# cryotest-kintex7.net
KiCad netlist of a schematic drawn in EAGLE
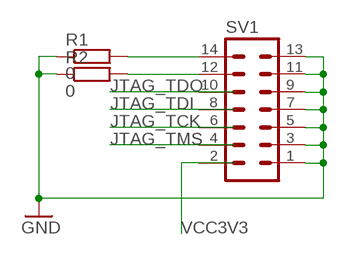
[diagram p0: schematic, sheet 1]
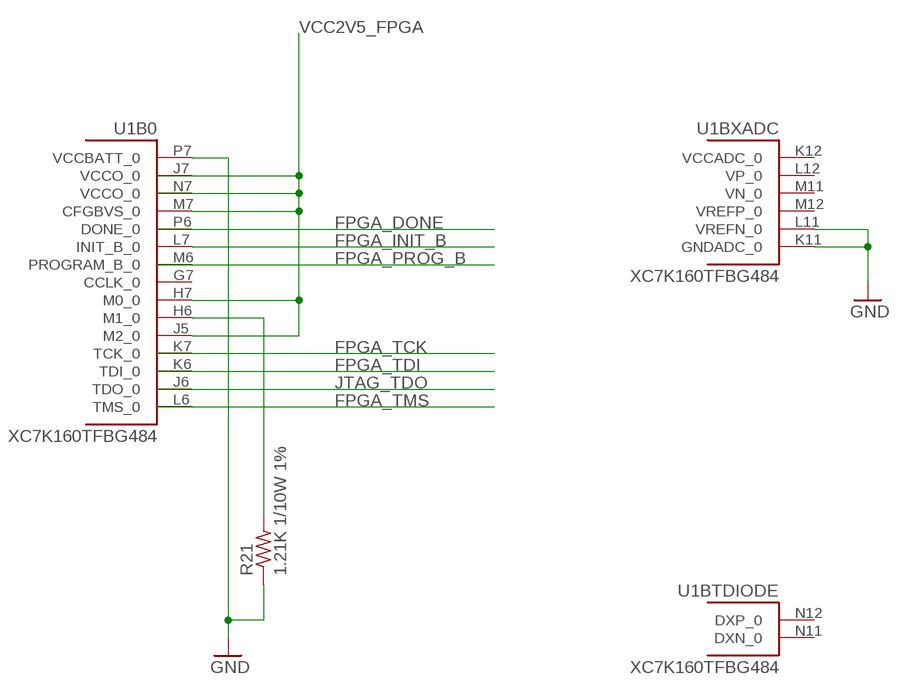
[diagram p1: schematic, sheet 2]
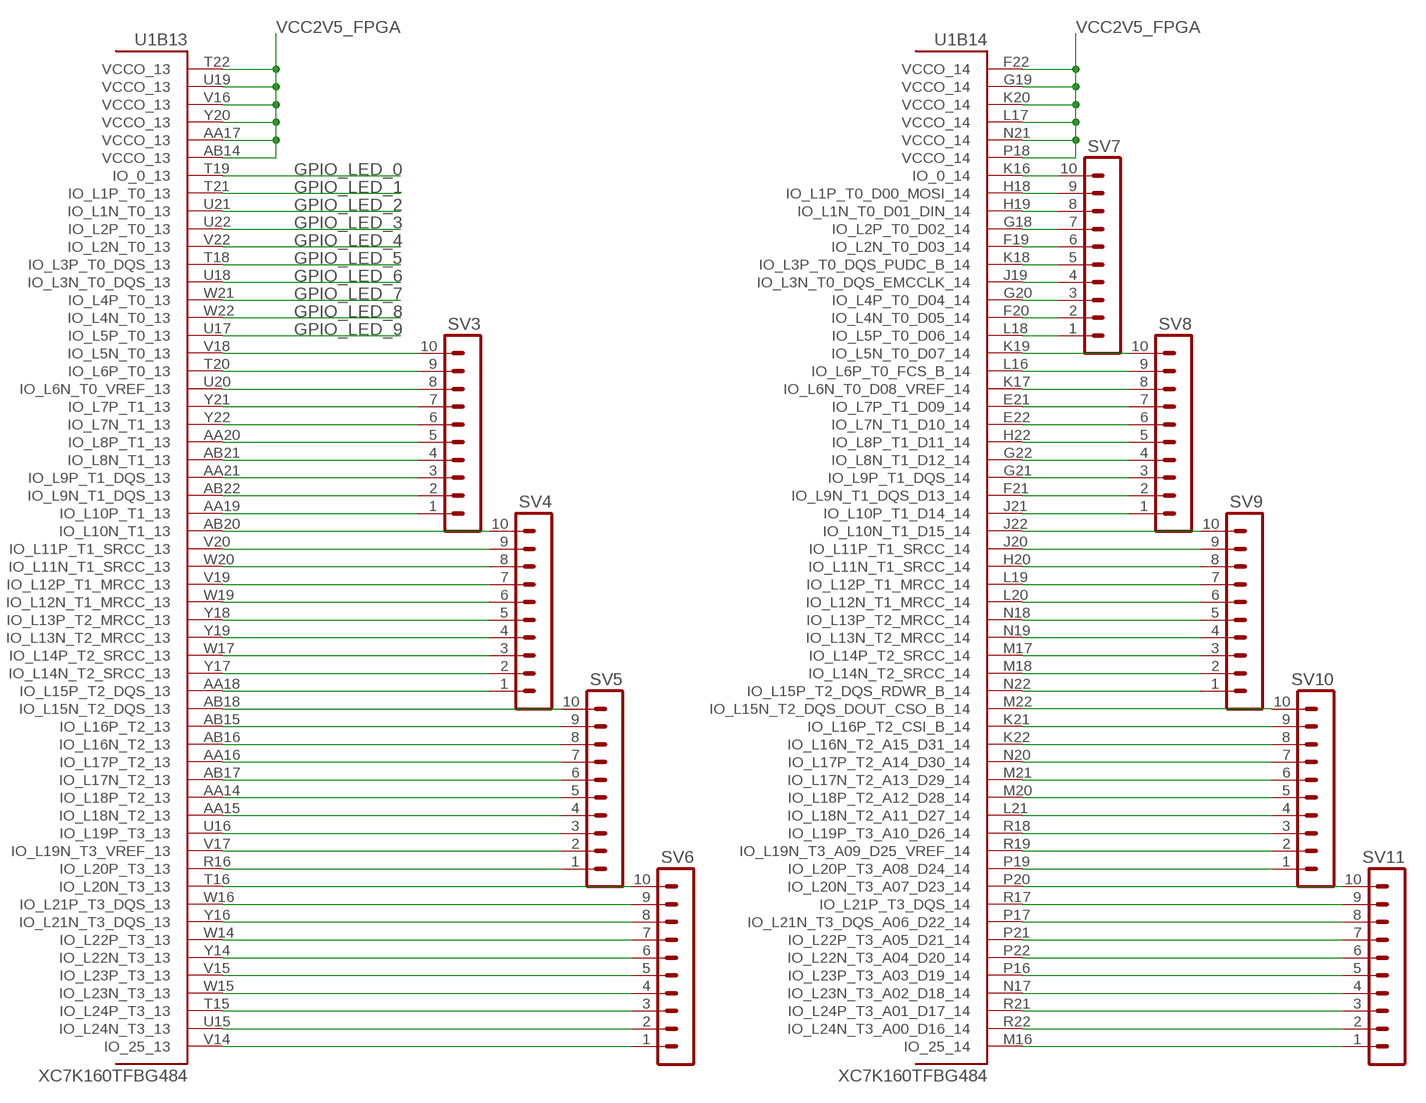
[diagram p2: schematic, sheet 3]
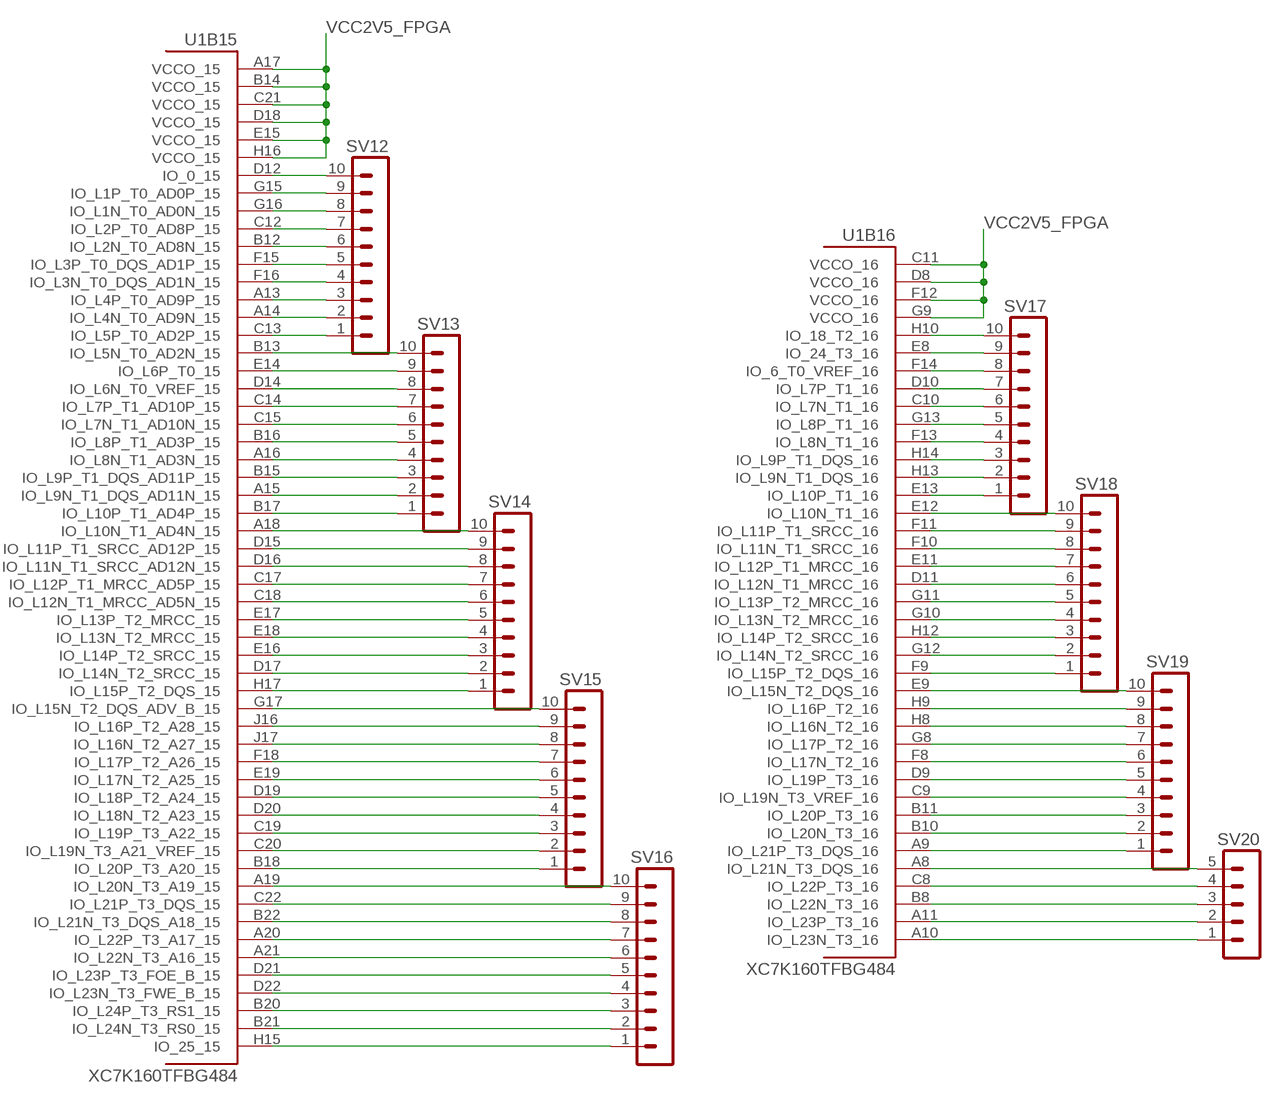
[diagram p3: schematic, sheet 4]
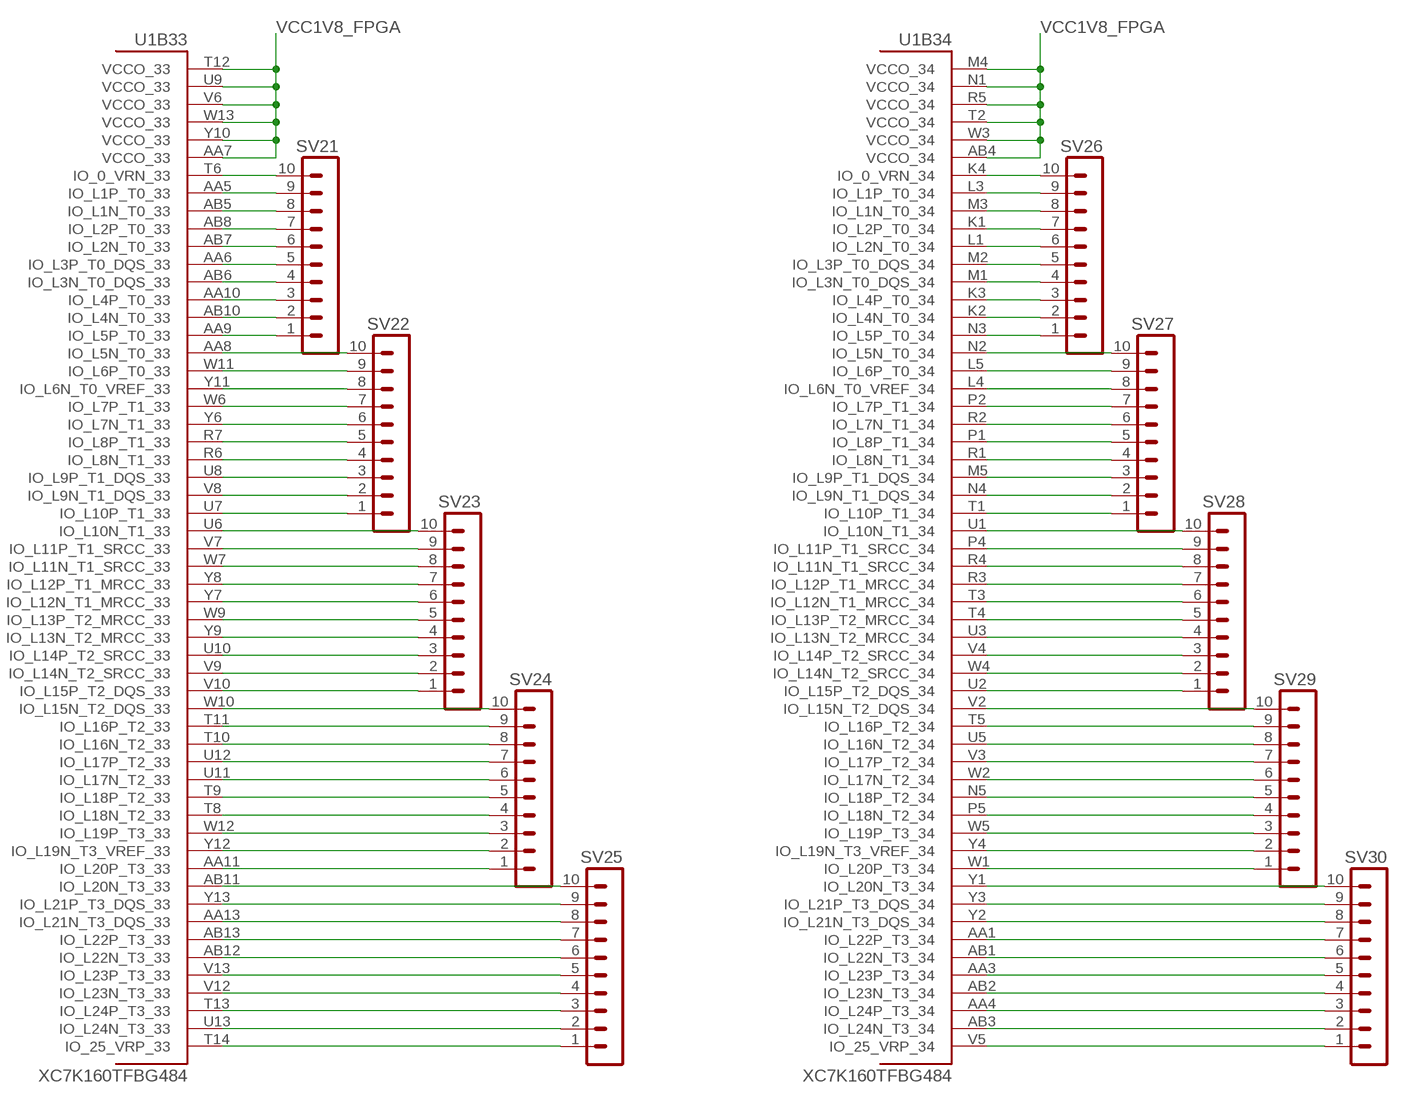
[diagram p4: schematic, sheet 5]
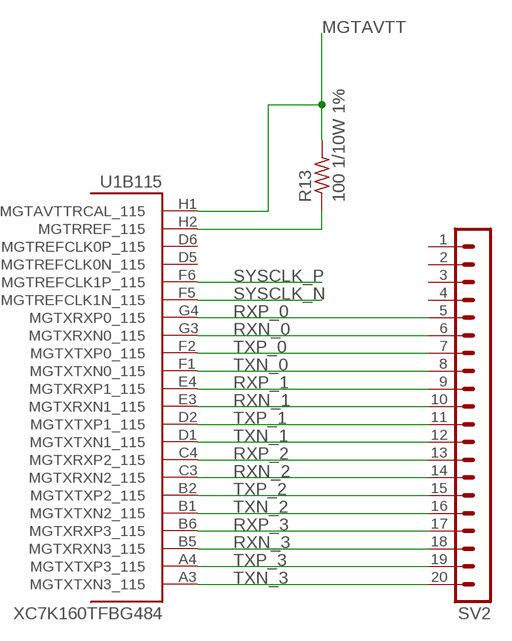
[diagram p5: schematic, sheet 6]
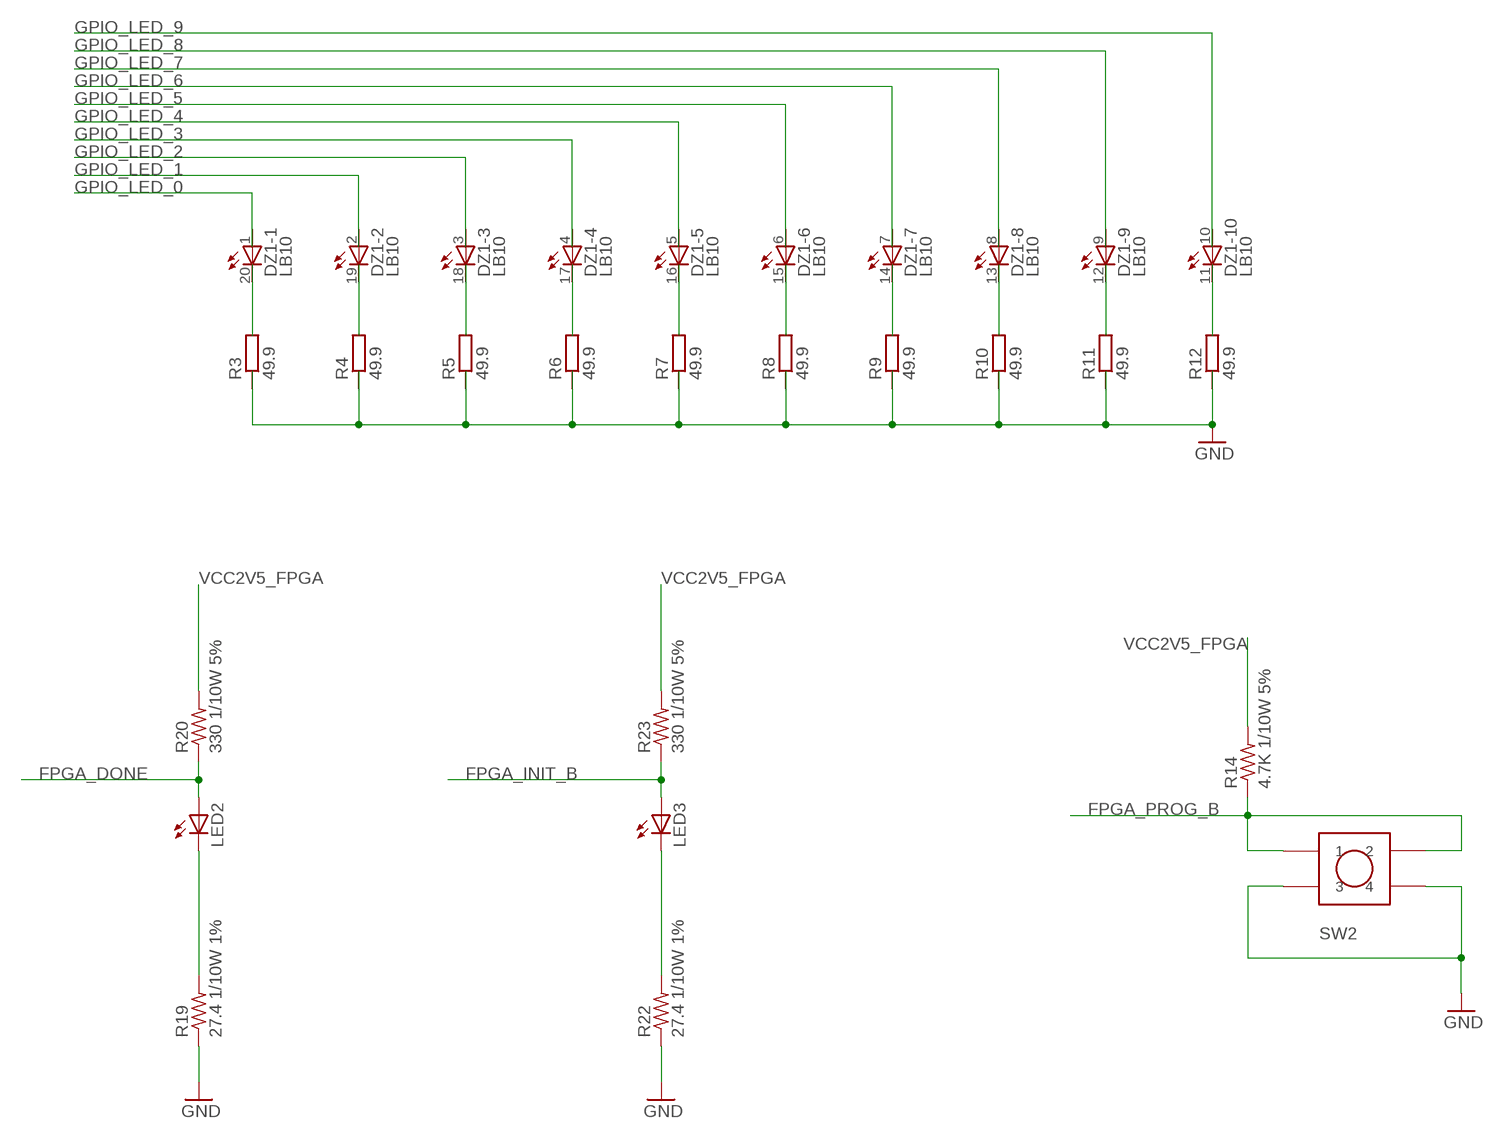
[diagram p6: schematic, sheet 7]
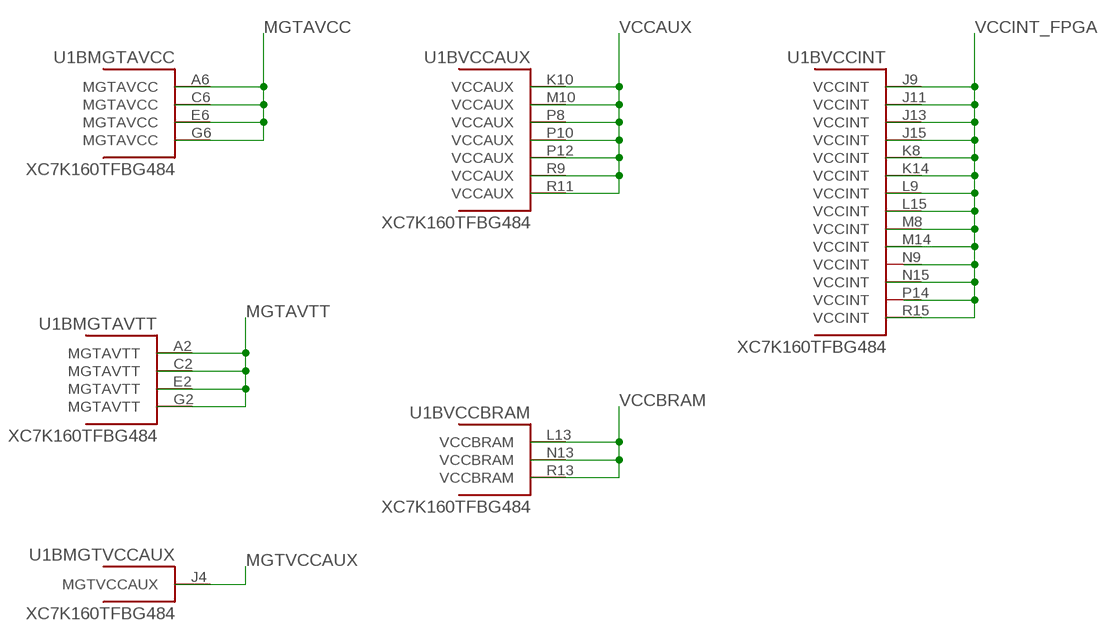
[diagram p7: schematic, sheet 8]
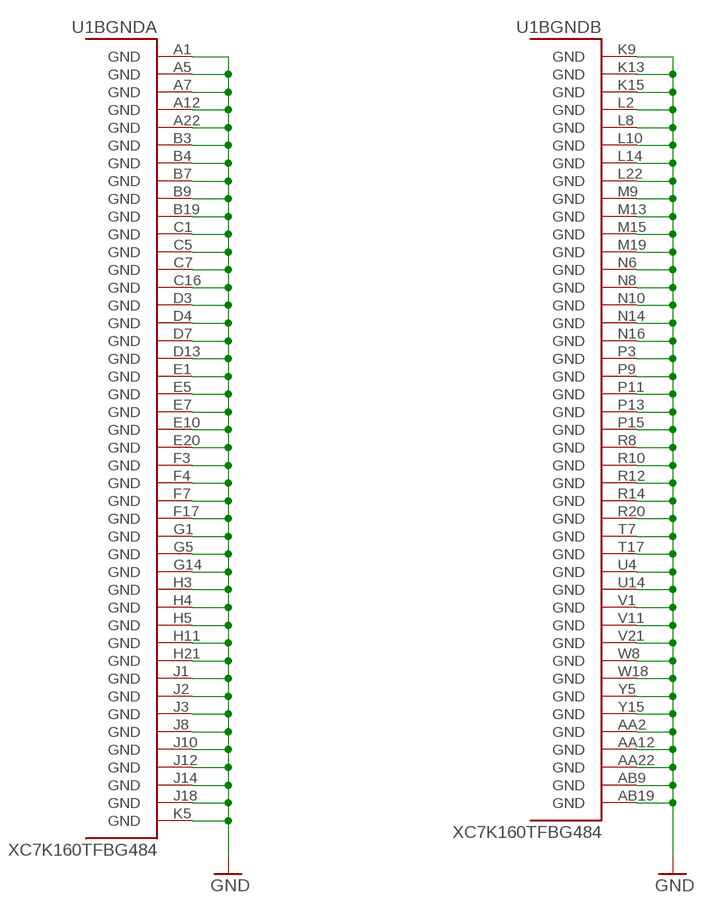
[diagram p8: schematic, sheet 9]
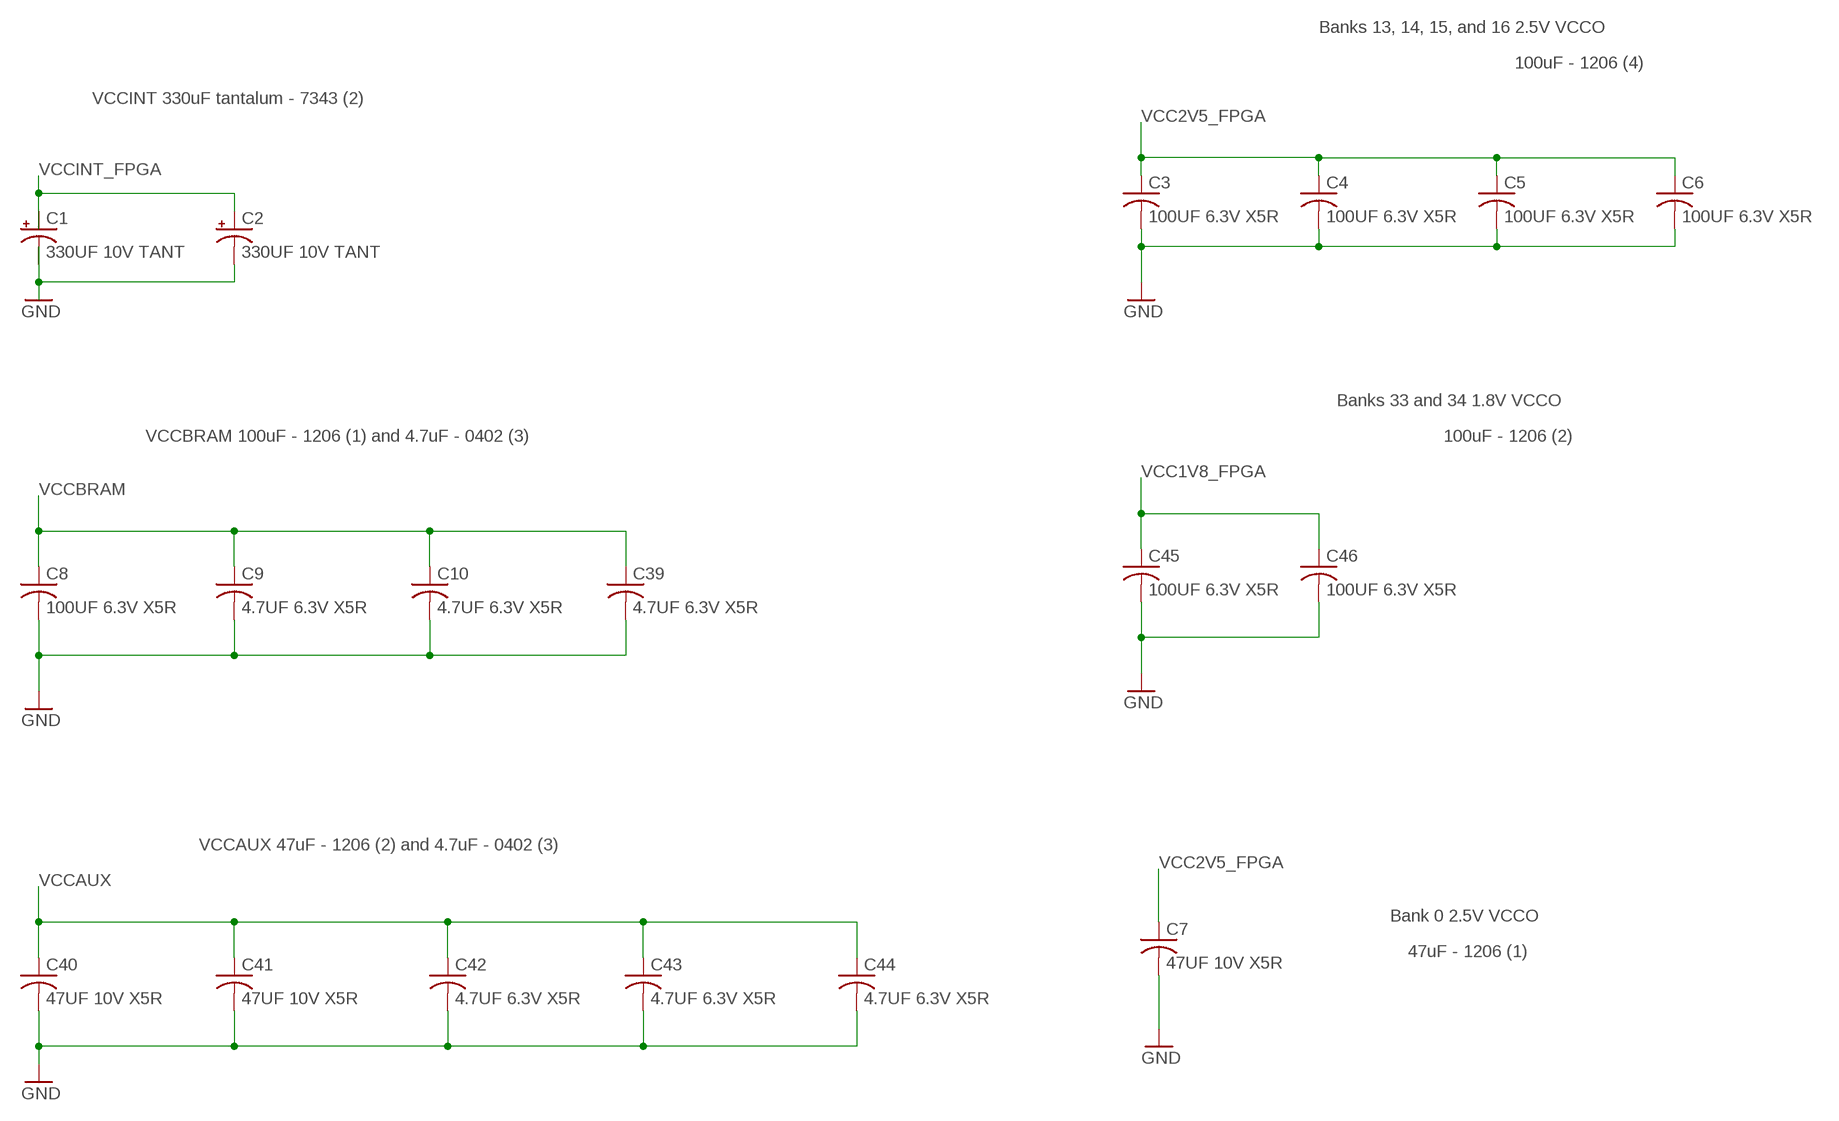
[diagram p9: schematic, sheet 10]
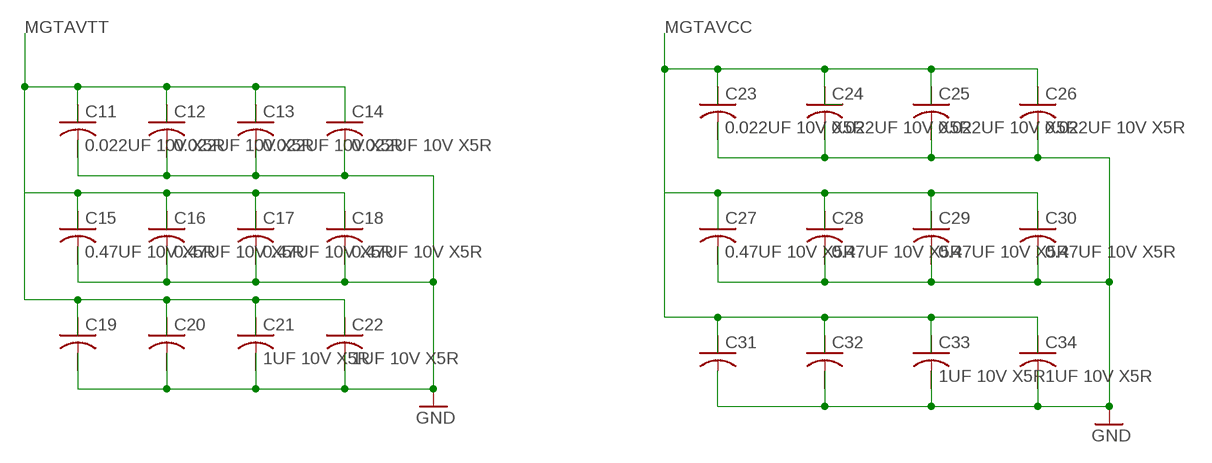
[diagram p10: schematic, sheet 11]
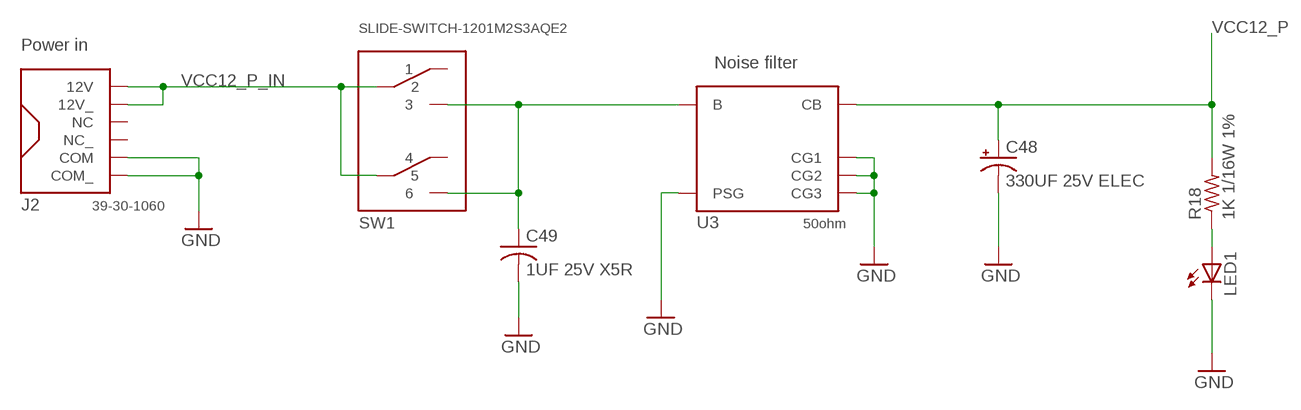
[diagram p11: schematic, sheet 12]
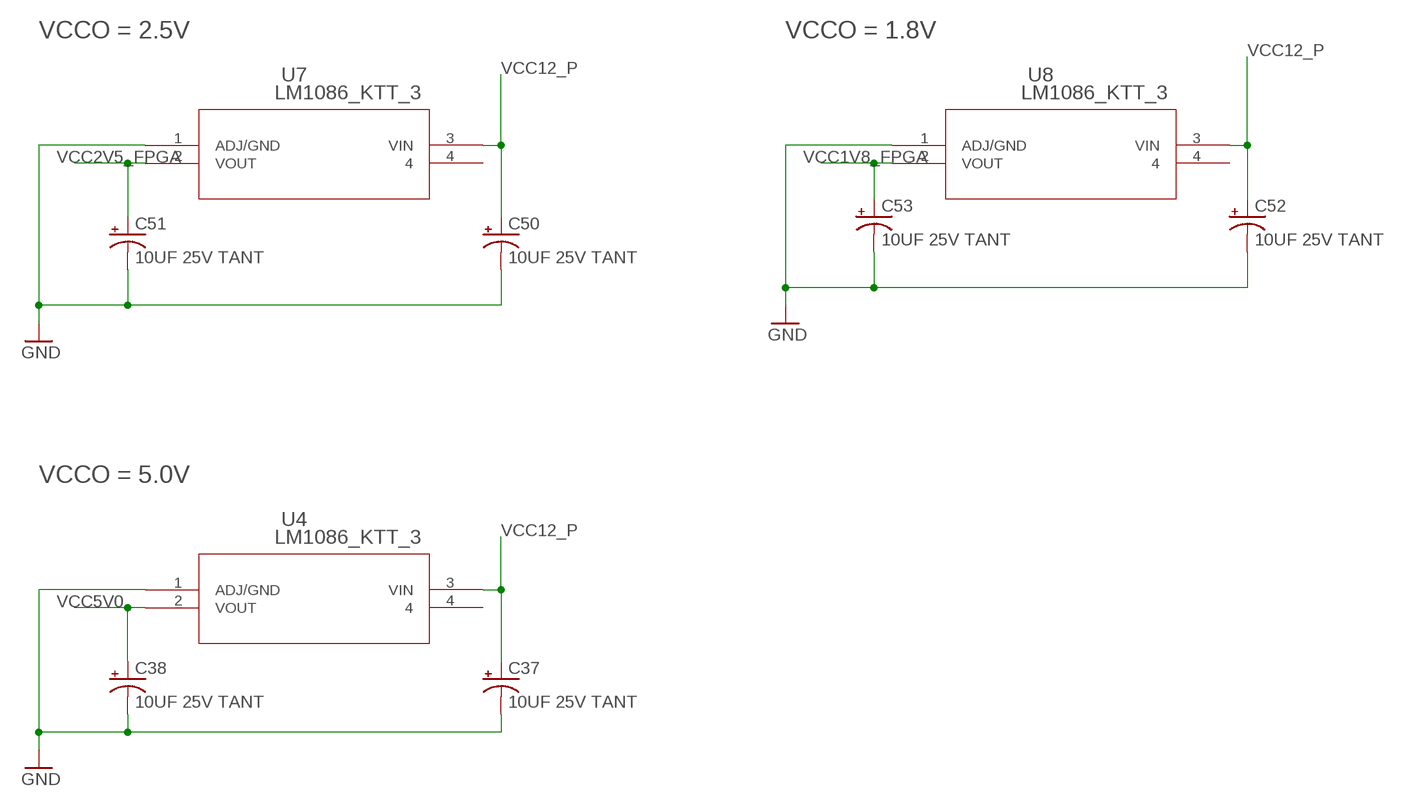
[diagram p12: schematic, sheet 13]
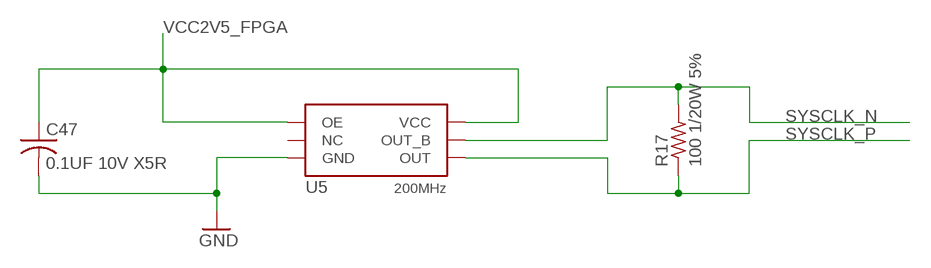
[diagram p13: schematic, sheet 14]
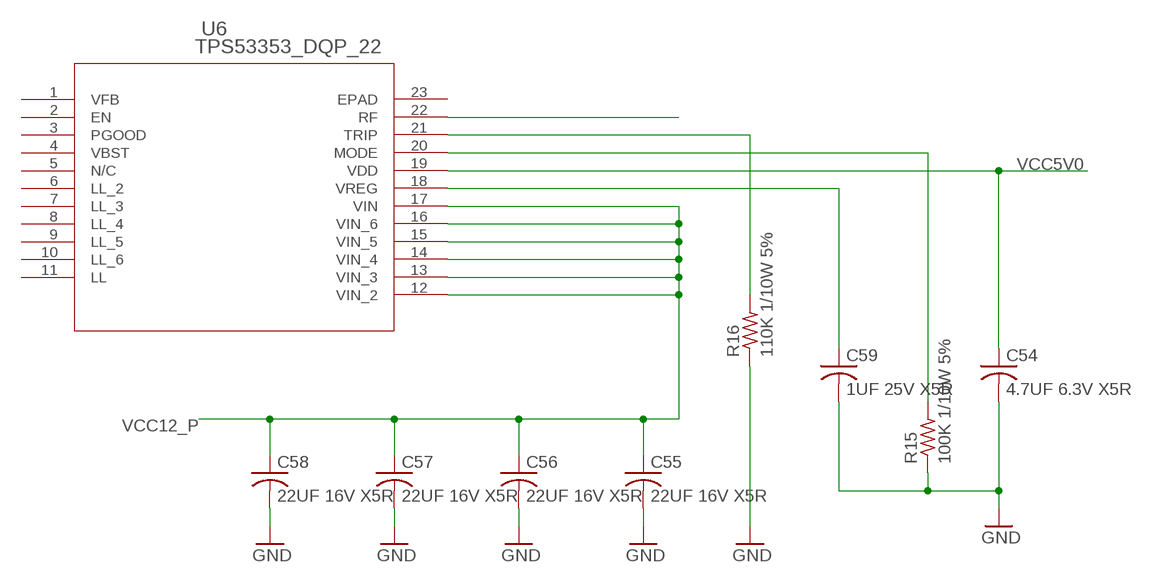
[diagram p14: schematic, sheet 15]

(export (version "E")
  (design (tool "Eeschema 10.0.6"))
  (components
    (comp (ref "R1")
      (value "0")
      (footprint "eagle-import:R0805")
      (libsource (lib "eagle-import") (part "R-EU_R0805"))
    )
    (comp (ref "R2")
      (value "0")
      (footprint "eagle-import:R0805")
      (libsource (lib "eagle-import") (part "R-EU_R0805"))
    )
    (comp (ref "SV1")
      (value "MA07-2")
      (footprint "eagle-import:MA07-2")
      (libsource (lib "eagle-import") (part "MA07-2"))
    )
    (comp (ref "SV12")
      (value "MA10-1")
      (footprint "eagle-import:MA10-1")
      (libsource (lib "eagle-import") (part "MA10-1"))
    )
    (comp (ref "SV13")
      (value "MA10-1")
      (footprint "eagle-import:MA10-1")
      (libsource (lib "eagle-import") (part "MA10-1"))
    )
    (comp (ref "SV14")
      (value "MA10-1")
      (footprint "eagle-import:MA10-1")
      (libsource (lib "eagle-import") (part "MA10-1"))
    )
    (comp (ref "SV15")
      (value "MA10-1")
      (footprint "eagle-import:MA10-1")
      (libsource (lib "eagle-import") (part "MA10-1"))
    )
    (comp (ref "SV16")
      (value "MA10-1")
      (footprint "eagle-import:MA10-1")
      (libsource (lib "eagle-import") (part "MA10-1"))
    )
    (comp (ref "SV17")
      (value "MA10-1")
      (footprint "eagle-import:MA10-1")
      (libsource (lib "eagle-import") (part "MA10-1"))
    )
    (comp (ref "SV18")
      (value "MA10-1")
      (footprint "eagle-import:MA10-1")
      (libsource (lib "eagle-import") (part "MA10-1"))
    )
    (comp (ref "SV19")
      (value "MA10-1")
      (footprint "eagle-import:MA10-1")
      (libsource (lib "eagle-import") (part "MA10-1"))
    )
    (comp (ref "SV20")
      (value "MA05-1")
      (footprint "eagle-import:MA05-1")
      (libsource (lib "eagle-import") (part "MA05-1"))
    )
    (comp (ref "U1")
      (value "XC7K160TFBG484")
      (footprint "eagle-import:FF484")
      (libsource (lib "eagle-import") (part "XC7K160TFBG484"))
    )
    (comp (ref "C1")
      (value "330UF 10V TANT")
      (footprint "eagle-import:CT7343")
      (libsource (lib "eagle-import") (part "CPOL-USCT7343"))
    )
    (comp (ref "C2")
      (value "330UF 10V TANT")
      (footprint "eagle-import:CT7343")
      (libsource (lib "eagle-import") (part "CPOL-USCT7343"))
    )
    (comp (ref "C3")
      (value "100UF 6.3V X5R")
      (footprint "eagle-import:C1206")
      (libsource (lib "eagle-import") (part "C-USC1206"))
    )
    (comp (ref "C4")
      (value "100UF 6.3V X5R")
      (footprint "eagle-import:C1206")
      (libsource (lib "eagle-import") (part "C-USC1206"))
    )
    (comp (ref "C5")
      (value "100UF 6.3V X5R")
      (footprint "eagle-import:C1206")
      (libsource (lib "eagle-import") (part "C-USC1206"))
    )
    (comp (ref "C6")
      (value "100UF 6.3V X5R")
      (footprint "eagle-import:C1206")
      (libsource (lib "eagle-import") (part "C-USC1206"))
    )
    (comp (ref "C7")
      (value "47UF 10V X5R")
      (footprint "eagle-import:C1206")
      (libsource (lib "eagle-import") (part "C-USC1206"))
    )
    (comp (ref "C8")
      (value "100UF 6.3V X5R")
      (footprint "eagle-import:C1206")
      (libsource (lib "eagle-import") (part "C-USC1206"))
    )
    (comp (ref "C9")
      (value "4.7UF 6.3V X5R")
      (footprint "eagle-import:C0402")
      (libsource (lib "eagle-import") (part "C-USC0402"))
    )
    (comp (ref "C10")
      (value "4.7UF 6.3V X5R")
      (footprint "eagle-import:C0402")
      (libsource (lib "eagle-import") (part "C-USC0402"))
    )
    (comp (ref "C39")
      (value "4.7UF 6.3V X5R")
      (footprint "eagle-import:C0402")
      (libsource (lib "eagle-import") (part "C-USC0402"))
    )
    (comp (ref "C40")
      (value "47UF 10V X5R")
      (footprint "eagle-import:C1206")
      (libsource (lib "eagle-import") (part "C-USC1206"))
    )
    (comp (ref "C41")
      (value "47UF 10V X5R")
      (footprint "eagle-import:C1206")
      (libsource (lib "eagle-import") (part "C-USC1206"))
    )
    (comp (ref "C42")
      (value "4.7UF 6.3V X5R")
      (footprint "eagle-import:C1206")
      (libsource (lib "eagle-import") (part "C-USC1206"))
    )
    (comp (ref "C43")
      (value "4.7UF 6.3V X5R")
      (footprint "eagle-import:C1206")
      (libsource (lib "eagle-import") (part "C-USC1206"))
    )
    (comp (ref "C44")
      (value "4.7UF 6.3V X5R")
      (footprint "eagle-import:C1206")
      (libsource (lib "eagle-import") (part "C-USC1206"))
    )
    (comp (ref "C45")
      (value "100UF 6.3V X5R")
      (footprint "eagle-import:C1206")
      (libsource (lib "eagle-import") (part "C-USC1206"))
    )
    (comp (ref "C46")
      (value "100UF 6.3V X5R")
      (footprint "eagle-import:C1206")
      (libsource (lib "eagle-import") (part "C-USC1206"))
    )
    (comp (ref "SV3")
      (value "MA10-1")
      (footprint "eagle-import:MA10-1")
      (libsource (lib "eagle-import") (part "MA10-1"))
    )
    (comp (ref "SV4")
      (value "MA10-1")
      (footprint "eagle-import:MA10-1")
      (libsource (lib "eagle-import") (part "MA10-1"))
    )
    (comp (ref "SV5")
      (value "MA10-1")
      (footprint "eagle-import:MA10-1")
      (libsource (lib "eagle-import") (part "MA10-1"))
    )
    (comp (ref "SV6")
      (value "MA10-1")
      (footprint "eagle-import:MA10-1")
      (libsource (lib "eagle-import") (part "MA10-1"))
    )
    (comp (ref "SV7")
      (value "MA10-1")
      (footprint "eagle-import:MA10-1")
      (libsource (lib "eagle-import") (part "MA10-1"))
    )
    (comp (ref "SV8")
      (value "MA10-1")
      (footprint "eagle-import:MA10-1")
      (libsource (lib "eagle-import") (part "MA10-1"))
    )
    (comp (ref "SV9")
      (value "MA10-1")
      (footprint "eagle-import:MA10-1")
      (libsource (lib "eagle-import") (part "MA10-1"))
    )
    (comp (ref "SV10")
      (value "MA10-1")
      (footprint "eagle-import:MA10-1")
      (libsource (lib "eagle-import") (part "MA10-1"))
    )
    (comp (ref "SV11")
      (value "MA10-1")
      (footprint "eagle-import:MA10-1")
      (libsource (lib "eagle-import") (part "MA10-1"))
    )
    (comp (ref "SV21")
      (value "MA10-1")
      (footprint "eagle-import:MA10-1")
      (libsource (lib "eagle-import") (part "MA10-1"))
    )
    (comp (ref "SV22")
      (value "MA10-1")
      (footprint "eagle-import:MA10-1")
      (libsource (lib "eagle-import") (part "MA10-1"))
    )
    (comp (ref "SV23")
      (value "MA10-1")
      (footprint "eagle-import:MA10-1")
      (libsource (lib "eagle-import") (part "MA10-1"))
    )
    (comp (ref "SV24")
      (value "MA10-1")
      (footprint "eagle-import:MA10-1")
      (libsource (lib "eagle-import") (part "MA10-1"))
    )
    (comp (ref "SV25")
      (value "MA10-1")
      (footprint "eagle-import:MA10-1")
      (libsource (lib "eagle-import") (part "MA10-1"))
    )
    (comp (ref "SV26")
      (value "MA10-1")
      (footprint "eagle-import:MA10-1")
      (libsource (lib "eagle-import") (part "MA10-1"))
    )
    (comp (ref "SV27")
      (value "MA10-1")
      (footprint "eagle-import:MA10-1")
      (libsource (lib "eagle-import") (part "MA10-1"))
    )
    (comp (ref "SV28")
      (value "MA10-1")
      (footprint "eagle-import:MA10-1")
      (libsource (lib "eagle-import") (part "MA10-1"))
    )
    (comp (ref "SV29")
      (value "MA10-1")
      (footprint "eagle-import:MA10-1")
      (libsource (lib "eagle-import") (part "MA10-1"))
    )
    (comp (ref "SV30")
      (value "MA10-1")
      (footprint "eagle-import:MA10-1")
      (libsource (lib "eagle-import") (part "MA10-1"))
    )
    (comp (ref "R21")
      (value "1.21K 1/10W 1%")
      (footprint "eagle-import:R0402")
      (libsource (lib "eagle-import") (part "R-US_R0402"))
    )
    (comp (ref "R13")
      (value "100 1/10W 1%")
      (footprint "eagle-import:R0402")
      (libsource (lib "eagle-import") (part "resistor_R-US_R0402"))
    )
    (comp (ref "SV2")
      (value "MA20-1")
      (footprint "eagle-import:MA20-1")
      (libsource (lib "eagle-import") (part "MA20-1"))
    )
    (comp (ref "C11")
      (value "0.022UF 10V X5R")
      (footprint "eagle-import:C0603")
      (libsource (lib "eagle-import") (part "C-USC0603"))
    )
    (comp (ref "C12")
      (value "0.022UF 10V X5R")
      (footprint "eagle-import:C0603")
      (libsource (lib "eagle-import") (part "C-USC0603"))
    )
    (comp (ref "C13")
      (value "0.022UF 10V X5R")
      (footprint "eagle-import:C0603")
      (libsource (lib "eagle-import") (part "C-USC0603"))
    )
    (comp (ref "C14")
      (value "0.022UF 10V X5R")
      (footprint "eagle-import:C0603")
      (libsource (lib "eagle-import") (part "C-USC0603"))
    )
    (comp (ref "C15")
      (value "0.47UF 10V X5R")
      (footprint "eagle-import:C0603")
      (libsource (lib "eagle-import") (part "C-USC0603"))
    )
    (comp (ref "C16")
      (value "0.47UF 10V X5R")
      (footprint "eagle-import:C0603")
      (libsource (lib "eagle-import") (part "C-USC0603"))
    )
    (comp (ref "C17")
      (value "0.47UF 10V X5R")
      (footprint "eagle-import:C0603")
      (libsource (lib "eagle-import") (part "C-USC0603"))
    )
    (comp (ref "C18")
      (value "0.47UF 10V X5R")
      (footprint "eagle-import:C0603")
      (libsource (lib "eagle-import") (part "C-USC0603"))
    )
    (comp (ref "C19")
      (value "C-US01005")
      (footprint "eagle-import:C01005")
      (libsource (lib "eagle-import") (part "C-US01005"))
    )
    (comp (ref "C20")
      (value "C-US01005")
      (footprint "eagle-import:C01005")
      (libsource (lib "eagle-import") (part "C-US01005"))
    )
    (comp (ref "C21")
      (value "1UF 10V X5R")
      (footprint "eagle-import:C0603")
      (libsource (lib "eagle-import") (part "C-USC0603"))
    )
    (comp (ref "C22")
      (value "1UF 10V X5R")
      (footprint "eagle-import:C0603")
      (libsource (lib "eagle-import") (part "C-USC0603"))
    )
    (comp (ref "C23")
      (value "0.022UF 10V X5R")
      (footprint "eagle-import:C0603")
      (libsource (lib "eagle-import") (part "C-USC0603"))
    )
    (comp (ref "C24")
      (value "0.022UF 10V X5R")
      (footprint "eagle-import:C0603")
      (libsource (lib "eagle-import") (part "C-USC0603"))
    )
    (comp (ref "C25")
      (value "0.022UF 10V X5R")
      (footprint "eagle-import:C0603")
      (libsource (lib "eagle-import") (part "C-USC0603"))
    )
    (comp (ref "C26")
      (value "0.022UF 10V X5R")
      (footprint "eagle-import:C0603")
      (libsource (lib "eagle-import") (part "C-USC0603"))
    )
    (comp (ref "C27")
      (value "0.47UF 10V X5R")
      (footprint "eagle-import:C0603")
      (libsource (lib "eagle-import") (part "C-USC0603"))
    )
    (comp (ref "C28")
      (value "0.47UF 10V X5R")
      (footprint "eagle-import:C0603")
      (libsource (lib "eagle-import") (part "C-USC0603"))
    )
    (comp (ref "C29")
      (value "0.47UF 10V X5R")
      (footprint "eagle-import:C0603")
      (libsource (lib "eagle-import") (part "C-USC0603"))
    )
    (comp (ref "C30")
      (value "0.47UF 10V X5R")
      (footprint "eagle-import:C0603")
      (libsource (lib "eagle-import") (part "C-USC0603"))
    )
    (comp (ref "C31")
      (value "C-US01005")
      (footprint "eagle-import:C01005")
      (libsource (lib "eagle-import") (part "C-US01005"))
    )
    (comp (ref "C32")
      (value "C-US01005")
      (footprint "eagle-import:C01005")
      (libsource (lib "eagle-import") (part "C-US01005"))
    )
    (comp (ref "C33")
      (value "1UF 10V X5R")
      (footprint "eagle-import:C0603")
      (libsource (lib "eagle-import") (part "C-USC0603"))
    )
    (comp (ref "C34")
      (value "1UF 10V X5R")
      (footprint "eagle-import:C0603")
      (libsource (lib "eagle-import") (part "C-USC0603"))
    )
    (comp (ref "C48")
      (value "330UF 25V ELEC")
      (footprint "eagle-import:PANASONIC_F")
      (libsource (lib "eagle-import") (part "CPOL-USF"))
    )
    (comp (ref "C49")
      (value "1UF 25V X5R")
      (footprint "eagle-import:C0603")
      (libsource (lib "eagle-import") (part "C-USC0603"))
    )
    (comp (ref "J2")
      (value "39-30-1060")
      (footprint "eagle-import:5569_6P")
      (libsource (lib "eagle-import") (part "39-30-1060{dblquote}"))
    )
    (comp (ref "LED1")
      (value "LEDSML0603")
      (footprint "eagle-import:SML0603")
      (libsource (lib "eagle-import") (part "LEDSML0603"))
    )
    (comp (ref "R18")
      (value "1K 1/16W 1%")
      (footprint "eagle-import:R0402")
      (libsource (lib "eagle-import") (part "R-US_R0402"))
    )
    (comp (ref "SW1")
      (value "SLIDE-SWITCH-1201M2S3AQE2")
      (footprint "eagle-import:HORIZONTAL-DPDT")
      (libsource (lib "eagle-import") (part "SLIDE-SWITCH-1201M2S3AQE2"))
    )
    (comp (ref "U3")
      (value "50ohm")
      (footprint "eagle-import:BNX016-01")
      (libsource (lib "eagle-import") (part "BNX016-01{dblquote}"))
    )
    (comp (ref "DZ1")
      (value "LB10")
      (footprint "eagle-import:LB10")
      (libsource (lib "eagle-import") (part "LB10"))
    )
    (comp (ref "LED2")
      (value "LEDSML0603")
      (footprint "eagle-import:SML0603")
      (libsource (lib "eagle-import") (part "LEDSML0603"))
    )
    (comp (ref "LED3")
      (value "LEDSML0603")
      (footprint "eagle-import:SML0603")
      (libsource (lib "eagle-import") (part "LEDSML0603"))
    )
    (comp (ref "R3")
      (value "49.9")
      (footprint "eagle-import:R0603")
      (libsource (lib "eagle-import") (part "resistor_R-EU_R0603"))
    )
    (comp (ref "R4")
      (value "49.9")
      (footprint "eagle-import:R0603")
      (libsource (lib "eagle-import") (part "resistor_R-EU_R0603"))
    )
    (comp (ref "R5")
      (value "49.9")
      (footprint "eagle-import:R0603")
      (libsource (lib "eagle-import") (part "resistor_R-EU_R0603"))
    )
    (comp (ref "R6")
      (value "49.9")
      (footprint "eagle-import:R0603")
      (libsource (lib "eagle-import") (part "resistor_R-EU_R0603"))
    )
    (comp (ref "R7")
      (value "49.9")
      (footprint "eagle-import:R0603")
      (libsource (lib "eagle-import") (part "resistor_R-EU_R0603"))
    )
    (comp (ref "R8")
      (value "49.9")
      (footprint "eagle-import:R0603")
      (libsource (lib "eagle-import") (part "resistor_R-EU_R0603"))
    )
    (comp (ref "R9")
      (value "49.9")
      (footprint "eagle-import:R0603")
      (libsource (lib "eagle-import") (part "resistor_R-EU_R0603"))
    )
    (comp (ref "R10")
      (value "49.9")
      (footprint "eagle-import:R0603")
      (libsource (lib "eagle-import") (part "resistor_R-EU_R0603"))
    )
    (comp (ref "R11")
      (value "49.9")
      (footprint "eagle-import:R0603")
      (libsource (lib "eagle-import") (part "resistor_R-EU_R0603"))
    )
    (comp (ref "R12")
      (value "49.9")
      (footprint "eagle-import:R0603")
      (libsource (lib "eagle-import") (part "resistor_R-EU_R0603"))
    )
    (comp (ref "R14")
      (value "4.7K 1/10W 5%")
      (footprint "eagle-import:R0402")
      (libsource (lib "eagle-import") (part "resistor_R-US_R0402"))
    )
    (comp (ref "R19")
      (value "27.4 1/10W 1%")
      (footprint "eagle-import:R0402")
      (libsource (lib "eagle-import") (part "R-US_R0402"))
    )
    (comp (ref "R20")
      (value "330 1/10W 5%")
      (footprint "eagle-import:R0603")
      (libsource (lib "eagle-import") (part "R-US_R0603"))
    )
    (comp (ref "R22")
      (value "27.4 1/10W 1%")
      (footprint "eagle-import:R0402")
      (libsource (lib "eagle-import") (part "R-US_R0402"))
    )
    (comp (ref "R23")
      (value "330 1/10W 5%")
      (footprint "eagle-import:R0603")
      (libsource (lib "eagle-import") (part "R-US_R0603"))
    )
    (comp (ref "SW2")
      (value "TL3301EF100QG\"")
      (footprint "eagle-import:GULL-WING")
      (libsource (lib "eagle-import") (part "TL3301EF100QG{dblquote}"))
    )
    (comp (ref "C54")
      (value "4.7UF 6.3V X5R")
      (footprint "eagle-import:C0402")
      (libsource (lib "eagle-import") (part "C-USC0402"))
    )
    (comp (ref "C55")
      (value "22UF 16V X5R")
      (footprint "eagle-import:C1206")
      (libsource (lib "eagle-import") (part "C-USC1206"))
    )
    (comp (ref "C56")
      (value "22UF 16V X5R")
      (footprint "eagle-import:C1206")
      (libsource (lib "eagle-import") (part "C-USC1206"))
    )
    (comp (ref "C57")
      (value "22UF 16V X5R")
      (footprint "eagle-import:C1206")
      (libsource (lib "eagle-import") (part "C-USC1206"))
    )
    (comp (ref "C58")
      (value "22UF 16V X5R")
      (footprint "eagle-import:C1206")
      (libsource (lib "eagle-import") (part "C-USC1206"))
    )
    (comp (ref "C59")
      (value "1UF 25V X5R")
      (footprint "eagle-import:C0603")
      (libsource (lib "eagle-import") (part "C-USC0603"))
    )
    (comp (ref "R15")
      (value "100K 1/10W 5%")
      (footprint "eagle-import:R0402")
      (libsource (lib "eagle-import") (part "R-US_R0402"))
    )
    (comp (ref "R16")
      (value "110K 1/10W 5%")
      (footprint "eagle-import:R0402")
      (libsource (lib "eagle-import") (part "resistor_R-US_R0402"))
    )
    (comp (ref "U6")
      (value "TPS53353_DQP_22")
      (footprint "eagle-import:DQP22_5P479X3P24")
      (fields
        (field (name "GENERIC_PART_NUMBER") "TPS53353")
        (field (name "MANUFACTURER") "Texas Instruments")
        (field (name "MANUFACTURER_PART_NUMBER") "tps53353_dqp_22")
      )
      (libsource (lib "eagle-import") (part "TPS53353_DQP_22"))
    )
    (comp (ref "C47")
      (value "0.1UF 10V X5R")
      (footprint "eagle-import:C0402")
      (libsource (lib "eagle-import") (part "C-USC0402"))
    )
    (comp (ref "R17")
      (value "100 1/20W 5%")
      (footprint "eagle-import:R0201")
      (libsource (lib "eagle-import") (part "R-US_R0201"))
    )
    (comp (ref "U5")
      (value "200MHz")
      (footprint "eagle-import:7X5")
      (libsource (lib "eagle-import") (part "SIT9102{dblquote}"))
    )
    (comp (ref "C37")
      (value "10UF 25V TANT")
      (footprint "eagle-import:CT7343")
      (libsource (lib "eagle-import") (part "CPOL-USCT7343"))
    )
    (comp (ref "C38")
      (value "10UF 25V TANT")
      (footprint "eagle-import:CT7343")
      (libsource (lib "eagle-import") (part "CPOL-USCT7343"))
    )
    (comp (ref "C50")
      (value "10UF 25V TANT")
      (footprint "eagle-import:CT7343")
      (libsource (lib "eagle-import") (part "CPOL-USCT7343"))
    )
    (comp (ref "C51")
      (value "10UF 25V TANT")
      (footprint "eagle-import:CT7343")
      (libsource (lib "eagle-import") (part "CPOL-USCT7343"))
    )
    (comp (ref "C52")
      (value "10UF 25V TANT")
      (footprint "eagle-import:CT7343")
      (libsource (lib "eagle-import") (part "CPOL-USCT7343"))
    )
    (comp (ref "C53")
      (value "10UF 25V TANT")
      (footprint "eagle-import:CT7343")
      (libsource (lib "eagle-import") (part "CPOL-USCT7343"))
    )
    (comp (ref "U4")
      (value "LM1086_KTT_3")
      (footprint "eagle-import:TS3B")
      (fields (field (name "PARTNUMBER") "LM1086CS-25"))
      (libsource (lib "eagle-import") (part "LM1086_KTT_3"))
    )
    (comp (ref "U7")
      (value "LM1086_KTT_3")
      (footprint "eagle-import:TS3B")
      (fields (field (name "PARTNUMBER") "LM1086CS-25"))
      (libsource (lib "eagle-import") (part "LM1086_KTT_3"))
    )
    (comp (ref "U8")
      (value "LM1086_KTT_3")
      (footprint "eagle-import:TS3B")
      (fields (field (name "PARTNUMBER") "LM1086CS-25"))
      (libsource (lib "eagle-import") (part "LM1086_KTT_3"))
    )
  )
  (nets
    (net (code "1") (name "FPGA_DONE") (class "Default")
      (node (ref "LED2") (pin "A") (pinfunction "A_A") (pintype "passive"))
      (node (ref "R20") (pin "1") (pinfunction "1_1") (pintype "passive"))
    )
    (net (code "2") (name "FPGA_INIT_B") (class "Default")
      (node (ref "LED3") (pin "A") (pinfunction "A_A") (pintype "passive"))
      (node (ref "R23") (pin "1") (pinfunction "1_1") (pintype "passive"))
      (node (ref "U1") (pin "L7") (pinfunction "INIT_B_0_L7") (pintype "open_collector"))
    )
    (net (code "3") (name "FPGA_PROG_B") (class "Default")
      (node (ref "R14") (pin "1") (pinfunction "1_1") (pintype "passive"))
      (node (ref "SW2") (pin "P$1") (pinfunction "1_P$1") (pintype "bidirectional"))
      (node (ref "SW2") (pin "P$2") (pinfunction "2_P$2") (pintype "bidirectional"))
    )
    (net (code "7") (name "GND") (class "Default")
      (node (ref "C10") (pin "2") (pinfunction "2_2") (pintype "passive"))
      (node (ref "C2") (pin "-") (pinfunction "-_-") (pintype "passive"))
      (node (ref "C3") (pin "2") (pinfunction "2_2") (pintype "passive"))
      (node (ref "C37") (pin "-") (pinfunction "-_-") (pintype "passive"))
      (node (ref "C38") (pin "-") (pinfunction "-_-") (pintype "passive"))
      (node (ref "C39") (pin "2") (pinfunction "2_2") (pintype "passive"))
      (node (ref "C4") (pin "2") (pinfunction "2_2") (pintype "passive"))
      (node (ref "C40") (pin "2") (pinfunction "2_2") (pintype "passive"))
      (node (ref "C41") (pin "2") (pinfunction "2_2") (pintype "passive"))
      (node (ref "C42") (pin "2") (pinfunction "2_2") (pintype "passive"))
      (node (ref "C43") (pin "2") (pinfunction "2_2") (pintype "passive"))
      (node (ref "C44") (pin "2") (pinfunction "2_2") (pintype "passive"))
      (node (ref "C45") (pin "2") (pinfunction "2_2") (pintype "passive"))
      (node (ref "C46") (pin "2") (pinfunction "2_2") (pintype "passive"))
      (node (ref "C47") (pin "2") (pinfunction "2_2") (pintype "passive"))
      (node (ref "C48") (pin "-") (pinfunction "-_-") (pintype "passive"))
      (node (ref "C49") (pin "2") (pinfunction "2_2") (pintype "passive"))
      (node (ref "C5") (pin "2") (pinfunction "2_2") (pintype "passive"))
      (node (ref "C50") (pin "-") (pinfunction "-_-") (pintype "passive"))
      (node (ref "C51") (pin "-") (pinfunction "-_-") (pintype "passive"))
      (node (ref "C52") (pin "-") (pinfunction "-_-") (pintype "passive"))
      (node (ref "C53") (pin "-") (pinfunction "-_-") (pintype "passive"))
      (node (ref "C54") (pin "2") (pinfunction "2_2") (pintype "passive"))
      (node (ref "C55") (pin "2") (pinfunction "2_2") (pintype "passive"))
      (node (ref "C56") (pin "2") (pinfunction "2_2") (pintype "passive"))
      (node (ref "C57") (pin "2") (pinfunction "2_2") (pintype "passive"))
      (node (ref "C58") (pin "2") (pinfunction "2_2") (pintype "passive"))
      (node (ref "C59") (pin "2") (pinfunction "2_2") (pintype "passive"))
      (node (ref "C6") (pin "2") (pinfunction "2_2") (pintype "passive"))
      (node (ref "C7") (pin "2") (pinfunction "2_2") (pintype "passive"))
      (node (ref "C8") (pin "2") (pinfunction "2_2") (pintype "passive"))
      (node (ref "C9") (pin "2") (pinfunction "2_2") (pintype "passive"))
      (node (ref "J2") (pin "P$3") (pinfunction "COM_P$3") (pintype "power_in"))
      (node (ref "J2") (pin "P$6") (pinfunction "COM__P$6") (pintype "power_in"))
      (node (ref "LED1") (pin "C") (pinfunction "C_C") (pintype "passive"))
      (node (ref "R1") (pin "1") (pinfunction "1_1") (pintype "passive"))
      (node (ref "R15") (pin "1") (pinfunction "1_1") (pintype "passive"))
      (node (ref "R16") (pin "1") (pinfunction "1_1") (pintype "passive"))
      (node (ref "R19") (pin "1") (pinfunction "1_1") (pintype "passive"))
      (node (ref "R2") (pin "1") (pinfunction "1_1") (pintype "passive"))
      (node (ref "R21") (pin "1") (pinfunction "1_1") (pintype "passive"))
      (node (ref "R22") (pin "1") (pinfunction "1_1") (pintype "passive"))
      (node (ref "SV1") (pin "1") (pinfunction "1_1") (pintype "passive"))
      (node (ref "SV1") (pin "11") (pinfunction "11_11") (pintype "passive"))
      (node (ref "SV1") (pin "13") (pinfunction "13_13") (pintype "passive"))
      (node (ref "SV1") (pin "3") (pinfunction "3_3") (pintype "passive"))
      (node (ref "SV1") (pin "5") (pinfunction "5_5") (pintype "passive"))
      (node (ref "SV1") (pin "7") (pinfunction "7_7") (pintype "passive"))
      (node (ref "SV1") (pin "9") (pinfunction "9_9") (pintype "passive"))
      (node (ref "SW2") (pin "P$3") (pinfunction "3_P$3") (pintype "bidirectional"))
      (node (ref "SW2") (pin "P$4") (pinfunction "4_P$4") (pintype "bidirectional"))
      (node (ref "U1") (pin "A1") (pinfunction "GND_A1") (pintype "power_in"))
      (node (ref "U1") (pin "A12") (pinfunction "GND_A12") (pintype "power_in"))
      (node (ref "U1") (pin "A22") (pinfunction "GND_A22") (pintype "power_in"))
      (node (ref "U1") (pin "A5") (pinfunction "GND_A5") (pintype "power_in"))
      (node (ref "U1") (pin "A7") (pinfunction "GND_A7") (pintype "power_in"))
      (node (ref "U1") (pin "AA12") (pinfunction "GND_AA12") (pintype "power_in"))
      (node (ref "U1") (pin "AA2") (pinfunction "GND_AA2") (pintype "power_in"))
      (node (ref "U1") (pin "AA22") (pinfunction "GND_AA22") (pintype "power_in"))
      (node (ref "U1") (pin "AB19") (pinfunction "GND_AB19") (pintype "power_in"))
      (node (ref "U1") (pin "AB9") (pinfunction "GND_AB9") (pintype "power_in"))
      (node (ref "U1") (pin "B19") (pinfunction "GND_B19") (pintype "power_in"))
      (node (ref "U1") (pin "B3") (pinfunction "GND_B3") (pintype "power_in"))
      (node (ref "U1") (pin "B4") (pinfunction "GND_B4") (pintype "power_in"))
      (node (ref "U1") (pin "B7") (pinfunction "GND_B7") (pintype "power_in"))
      (node (ref "U1") (pin "B9") (pinfunction "GND_B9") (pintype "power_in"))
      (node (ref "U1") (pin "C1") (pinfunction "GND_C1") (pintype "power_in"))
      (node (ref "U1") (pin "C16") (pinfunction "GND_C16") (pintype "power_in"))
      (node (ref "U1") (pin "C5") (pinfunction "GND_C5") (pintype "power_in"))
      (node (ref "U1") (pin "C7") (pinfunction "GND_C7") (pintype "power_in"))
      (node (ref "U1") (pin "D13") (pinfunction "GND_D13") (pintype "power_in"))
      (node (ref "U1") (pin "D3") (pinfunction "GND_D3") (pintype "power_in"))
      (node (ref "U1") (pin "D4") (pinfunction "GND_D4") (pintype "power_in"))
      (node (ref "U1") (pin "D7") (pinfunction "GND_D7") (pintype "power_in"))
      (node (ref "U1") (pin "E1") (pinfunction "GND_E1") (pintype "power_in"))
      (node (ref "U1") (pin "E10") (pinfunction "GND_E10") (pintype "power_in"))
      (node (ref "U1") (pin "E20") (pinfunction "GND_E20") (pintype "power_in"))
      (node (ref "U1") (pin "E5") (pinfunction "GND_E5") (pintype "power_in"))
      (node (ref "U1") (pin "E7") (pinfunction "GND_E7") (pintype "power_in"))
      (node (ref "U1") (pin "F17") (pinfunction "GND_F17") (pintype "power_in"))
      (node (ref "U1") (pin "F3") (pinfunction "GND_F3") (pintype "power_in"))
      (node (ref "U1") (pin "F4") (pinfunction "GND_F4") (pintype "power_in"))
      (node (ref "U1") (pin "F7") (pinfunction "GND_F7") (pintype "power_in"))
      (node (ref "U1") (pin "G1") (pinfunction "GND_G1") (pintype "power_in"))
      (node (ref "U1") (pin "G14") (pinfunction "GND_G14") (pintype "power_in"))
      (node (ref "U1") (pin "G5") (pinfunction "GND_G5") (pintype "power_in"))
      (node (ref "U1") (pin "H11") (pinfunction "GND_H11") (pintype "power_in"))
      (node (ref "U1") (pin "H21") (pinfunction "GND_H21") (pintype "power_in"))
      (node (ref "U1") (pin "H3") (pinfunction "GND_H3") (pintype "power_in"))
      (node (ref "U1") (pin "H4") (pinfunction "GND_H4") (pintype "power_in"))
      (node (ref "U1") (pin "H5") (pinfunction "GND_H5") (pintype "power_in"))
      (node (ref "U1") (pin "J1") (pinfunction "GND_J1") (pintype "power_in"))
      (node (ref "U1") (pin "J10") (pinfunction "GND_J10") (pintype "power_in"))
      (node (ref "U1") (pin "J12") (pinfunction "GND_J12") (pintype "power_in"))
      (node (ref "U1") (pin "J14") (pinfunction "GND_J14") (pintype "power_in"))
      (node (ref "U1") (pin "J18") (pinfunction "GND_J18") (pintype "power_in"))
      (node (ref "U1") (pin "J2") (pinfunction "GND_J2") (pintype "power_in"))
      (node (ref "U1") (pin "J3") (pinfunction "GND_J3") (pintype "power_in"))
      (node (ref "U1") (pin "J8") (pinfunction "GND_J8") (pintype "power_in"))
      (node (ref "U1") (pin "K11") (pinfunction "GNDADC_0_K11") (pintype "bidirectional"))
      (node (ref "U1") (pin "K13") (pinfunction "GND_K13") (pintype "power_in"))
      (node (ref "U1") (pin "K15") (pinfunction "GND_K15") (pintype "power_in"))
      (node (ref "U1") (pin "K5") (pinfunction "GND_K5") (pintype "power_in"))
      (node (ref "U1") (pin "K9") (pinfunction "GND_K9") (pintype "power_in"))
      (node (ref "U1") (pin "L10") (pinfunction "GND_L10") (pintype "power_in"))
      (node (ref "U1") (pin "L11") (pinfunction "VREFN_0_L11") (pintype "bidirectional"))
      (node (ref "U1") (pin "L14") (pinfunction "GND_L14") (pintype "power_in"))
      (node (ref "U1") (pin "L2") (pinfunction "GND_L2") (pintype "power_in"))
      (node (ref "U1") (pin "L22") (pinfunction "GND_L22") (pintype "power_in"))
      (node (ref "U1") (pin "L8") (pinfunction "GND_L8") (pintype "power_in"))
      (node (ref "U1") (pin "M13") (pinfunction "GND_M13") (pintype "power_in"))
      (node (ref "U1") (pin "M15") (pinfunction "GND_M15") (pintype "power_in"))
      (node (ref "U1") (pin "M19") (pinfunction "GND_M19") (pintype "power_in"))
      (node (ref "U1") (pin "M9") (pinfunction "GND_M9") (pintype "power_in"))
      (node (ref "U1") (pin "N10") (pinfunction "GND_N10") (pintype "power_in"))
      (node (ref "U1") (pin "N14") (pinfunction "GND_N14") (pintype "power_in"))
      (node (ref "U1") (pin "N16") (pinfunction "GND_N16") (pintype "power_in"))
      (node (ref "U1") (pin "N6") (pinfunction "GND_N6") (pintype "power_in"))
      (node (ref "U1") (pin "N8") (pinfunction "GND_N8") (pintype "power_in"))
      (node (ref "U1") (pin "P11") (pinfunction "GND_P11") (pintype "power_in"))
      (node (ref "U1") (pin "P13") (pinfunction "GND_P13") (pintype "power_in"))
      (node (ref "U1") (pin "P15") (pinfunction "GND_P15") (pintype "power_in"))
      (node (ref "U1") (pin "P3") (pinfunction "GND_P3") (pintype "power_in"))
      (node (ref "U1") (pin "P7") (pinfunction "VCCBATT_0_P7") (pintype "input"))
      (node (ref "U1") (pin "P9") (pinfunction "GND_P9") (pintype "power_in"))
      (node (ref "U1") (pin "R10") (pinfunction "GND_R10") (pintype "power_in"))
      (node (ref "U1") (pin "R12") (pinfunction "GND_R12") (pintype "power_in"))
      (node (ref "U1") (pin "R14") (pinfunction "GND_R14") (pintype "power_in"))
      (node (ref "U1") (pin "R20") (pinfunction "GND_R20") (pintype "power_in"))
      (node (ref "U1") (pin "R8") (pinfunction "GND_R8") (pintype "power_in"))
      (node (ref "U1") (pin "T17") (pinfunction "GND_T17") (pintype "power_in"))
      (node (ref "U1") (pin "T7") (pinfunction "GND_T7") (pintype "power_in"))
      (node (ref "U1") (pin "U14") (pinfunction "GND_U14") (pintype "power_in"))
      (node (ref "U1") (pin "U4") (pinfunction "GND_U4") (pintype "power_in"))
      (node (ref "U1") (pin "V1") (pinfunction "GND_V1") (pintype "power_in"))
      (node (ref "U1") (pin "V11") (pinfunction "GND_V11") (pintype "power_in"))
      (node (ref "U1") (pin "V21") (pinfunction "GND_V21") (pintype "power_in"))
      (node (ref "U1") (pin "W18") (pinfunction "GND_W18") (pintype "power_in"))
      (node (ref "U1") (pin "W8") (pinfunction "GND_W8") (pintype "power_in"))
      (node (ref "U1") (pin "Y15") (pinfunction "GND_Y15") (pintype "power_in"))
      (node (ref "U1") (pin "Y5") (pinfunction "GND_Y5") (pintype "power_in"))
      (node (ref "U3") (pin "CG$1") (pinfunction "CG3_CG$1") (pintype "bidirectional"))
      (node (ref "U3") (pin "CG$2") (pinfunction "CG2_CG$2") (pintype "bidirectional"))
      (node (ref "U3") (pin "P$3") (pinfunction "PSG_P$3") (pintype "bidirectional"))
      (node (ref "U3") (pin "P$4") (pinfunction "CG1_P$4") (pintype "bidirectional"))
      (node (ref "U4") (pin "1") (pinfunction "ADJ/GND_1") (pintype "passive"))
      (node (ref "U5") (pin "P$3") (pinfunction "GND_P$3") (pintype "power_in"))
      (node (ref "U7") (pin "1") (pinfunction "ADJ/GND_1") (pintype "passive"))
      (node (ref "U8") (pin "1") (pinfunction "ADJ/GND_1") (pintype "passive"))
    )
    (net (code "8") (name "GPIO_LED_0") (class "Default")
      (node (ref "U1") (pin "T19") (pinfunction "IO_0_13_T19") (pintype "bidirectional"))
    )
    (net (code "9") (name "GPIO_LED_1") (class "Default")
      (node (ref "U1") (pin "T21") (pinfunction "IO_L1P_T0_13_T21") (pintype "bidirectional"))
    )
    (net (code "10") (name "GPIO_LED_2") (class "Default")
      (node (ref "U1") (pin "U21") (pinfunction "IO_L1N_T0_13_U21") (pintype "bidirectional"))
    )
    (net (code "11") (name "GPIO_LED_3") (class "Default")
      (node (ref "U1") (pin "U22") (pinfunction "IO_L2P_T0_13_U22") (pintype "bidirectional"))
    )
    (net (code "12") (name "GPIO_LED_4") (class "Default")
      (node (ref "U1") (pin "V22") (pinfunction "IO_L2N_T0_13_V22") (pintype "bidirectional"))
    )
    (net (code "13") (name "GPIO_LED_5") (class "Default")
      (node (ref "U1") (pin "T18") (pinfunction "IO_L3P_T0_DQS_13_T18") (pintype "bidirectional"))
    )
    (net (code "14") (name "GPIO_LED_6") (class "Default")
      (node (ref "U1") (pin "U18") (pinfunction "IO_L3N_T0_DQS_13_U18") (pintype "bidirectional"))
    )
    (net (code "15") (name "GPIO_LED_7") (class "Default")
      (node (ref "U1") (pin "W21") (pinfunction "IO_L4P_T0_13_W21") (pintype "bidirectional"))
    )
    (net (code "16") (name "GPIO_LED_8") (class "Default")
      (node (ref "U1") (pin "W22") (pinfunction "IO_L4N_T0_13_W22") (pintype "bidirectional"))
    )
    (net (code "17") (name "GPIO_LED_9") (class "Default")
      (node (ref "U1") (pin "U17") (pinfunction "IO_L5P_T0_13_U17") (pintype "bidirectional"))
    )
    (net (code "23") (name "MGTAVTT") (class "Default")
      (node (ref "R13") (pin "2") (pinfunction "2_2") (pintype "passive"))
      (node (ref "U1") (pin "H1") (pinfunction "MGTAVTTRCAL_115_H1") (pintype "input"))
    )
    (net (code "25") (name "Net-(LED1-PadA)") (class "Default")
      (node (ref "LED1") (pin "A") (pinfunction "A_A") (pintype "passive"))
      (node (ref "R18") (pin "1") (pinfunction "1_1") (pintype "passive"))
    )
    (net (code "26") (name "Net-(LED2-PadC)") (class "Default")
      (node (ref "LED2") (pin "C") (pinfunction "C_C") (pintype "passive"))
      (node (ref "R19") (pin "2") (pinfunction "2_2") (pintype "passive"))
    )
    (net (code "27") (name "Net-(LED3-PadC)") (class "Default")
      (node (ref "LED3") (pin "C") (pinfunction "C_C") (pintype "passive"))
      (node (ref "R22") (pin "2") (pinfunction "2_2") (pintype "passive"))
    )
    (net (code "28") (name "Net-(R1-Pad2)") (class "Default")
      (node (ref "R1") (pin "2") (pinfunction "2_2") (pintype "passive"))
      (node (ref "SV1") (pin "14") (pinfunction "14_14") (pintype "passive"))
    )
    (net (code "29") (name "Net-(R2-Pad2)") (class "Default")
      (node (ref "R2") (pin "2") (pinfunction "2_2") (pintype "passive"))
      (node (ref "SV1") (pin "12") (pinfunction "12_12") (pintype "passive"))
    )
    (net (code "30") (name "Net-(U1A-M1_0)") (class "Default")
      (node (ref "R21") (pin "2") (pinfunction "2_2") (pintype "passive"))
      (node (ref "U1") (pin "H6") (pinfunction "M1_0_H6") (pintype "input"))
    )
    (net (code "31") (name "Net-(U1B-MGTRREF_115)") (class "Default")
      (node (ref "R13") (pin "1") (pinfunction "1_1") (pintype "passive"))
      (node (ref "U1") (pin "H2") (pinfunction "MGTRREF_115_H2") (pintype "bidirectional"))
    )
    (net (code "32") (name "Net-(U1C-IO_25_13)") (class "Default")
      (node (ref "SV6") (pin "1") (pinfunction "1_1") (pintype "passive"))
      (node (ref "U1") (pin "V14") (pinfunction "IO_25_13_V14") (pintype "bidirectional"))
    )
    (net (code "33") (name "Net-(U1C-IO_L5N_T0_13)") (class "Default")
      (node (ref "SV3") (pin "10") (pinfunction "10_10") (pintype "passive"))
      (node (ref "U1") (pin "V18") (pinfunction "IO_L5N_T0_13_V18") (pintype "bidirectional"))
    )
    (net (code "34") (name "Net-(U1C-IO_L6N_T0_VREF_13)") (class "Default")
      (node (ref "SV3") (pin "8") (pinfunction "8_8") (pintype "passive"))
      (node (ref "U1") (pin "U20") (pinfunction "IO_L6N_T0_VREF_13_U20") (pintype "bidirectional"))
    )
    (net (code "35") (name "Net-(U1C-IO_L6P_T0_13)") (class "Default")
      (node (ref "SV3") (pin "9") (pinfunction "9_9") (pintype "passive"))
      (node (ref "U1") (pin "T20") (pinfunction "IO_L6P_T0_13_T20") (pintype "bidirectional"))
    )
    (net (code "36") (name "Net-(U1C-IO_L7N_T1_13)") (class "Default")
      (node (ref "SV3") (pin "6") (pinfunction "6_6") (pintype "passive"))
      (node (ref "U1") (pin "Y22") (pinfunction "IO_L7N_T1_13_Y22") (pintype "bidirectional"))
    )
    (net (code "37") (name "Net-(U1C-IO_L7P_T1_13)") (class "Default")
      (node (ref "SV3") (pin "7") (pinfunction "7_7") (pintype "passive"))
      (node (ref "U1") (pin "Y21") (pinfunction "IO_L7P_T1_13_Y21") (pintype "bidirectional"))
    )
    (net (code "38") (name "Net-(U1C-IO_L8N_T1_13)") (class "Default")
      (node (ref "SV3") (pin "4") (pinfunction "4_4") (pintype "passive"))
      (node (ref "U1") (pin "AB21") (pinfunction "IO_L8N_T1_13_AB21") (pintype "bidirectional"))
    )
    (net (code "39") (name "Net-(U1C-IO_L8P_T1_13)") (class "Default")
      (node (ref "SV3") (pin "5") (pinfunction "5_5") (pintype "passive"))
      (node (ref "U1") (pin "AA20") (pinfunction "IO_L8P_T1_13_AA20") (pintype "bidirectional"))
    )
    (net (code "40") (name "Net-(U1C-IO_L9N_T1_DQS_13)") (class "Default")
      (node (ref "SV3") (pin "2") (pinfunction "2_2") (pintype "passive"))
      (node (ref "U1") (pin "AB22") (pinfunction "IO_L9N_T1_DQS_13_AB22") (pintype "bidirectional"))
    )
    (net (code "41") (name "Net-(U1C-IO_L9P_T1_DQS_13)") (class "Default")
      (node (ref "SV3") (pin "3") (pinfunction "3_3") (pintype "passive"))
      (node (ref "U1") (pin "AA21") (pinfunction "IO_L9P_T1_DQS_13_AA21") (pintype "bidirectional"))
    )
    (net (code "42") (name "Net-(U1C-IO_L10N_T1_13)") (class "Default")
      (node (ref "SV4") (pin "10") (pinfunction "10_10") (pintype "passive"))
      (node (ref "U1") (pin "AB20") (pinfunction "IO_L10N_T1_13_AB20") (pintype "bidirectional"))
    )
    (net (code "43") (name "Net-(U1C-IO_L10P_T1_13)") (class "Default")
      (node (ref "SV3") (pin "1") (pinfunction "1_1") (pintype "passive"))
      (node (ref "U1") (pin "AA19") (pinfunction "IO_L10P_T1_13_AA19") (pintype "bidirectional"))
    )
    (net (code "44") (name "Net-(U1C-IO_L11N_T1_SRCC_13)") (class "Default")
      (node (ref "SV4") (pin "8") (pinfunction "8_8") (pintype "passive"))
      (node (ref "U1") (pin "W20") (pinfunction "IO_L11N_T1_SRCC_13_W20") (pintype "bidirectional"))
    )
    (net (code "45") (name "Net-(U1C-IO_L11P_T1_SRCC_13)") (class "Default")
      (node (ref "SV4") (pin "9") (pinfunction "9_9") (pintype "passive"))
      (node (ref "U1") (pin "V20") (pinfunction "IO_L11P_T1_SRCC_13_V20") (pintype "bidirectional"))
    )
    (net (code "46") (name "Net-(U1C-IO_L12N_T1_MRCC_13)") (class "Default")
      (node (ref "SV4") (pin "6") (pinfunction "6_6") (pintype "passive"))
      (node (ref "U1") (pin "W19") (pinfunction "IO_L12N_T1_MRCC_13_W19") (pintype "bidirectional"))
    )
    (net (code "47") (name "Net-(U1C-IO_L12P_T1_MRCC_13)") (class "Default")
      (node (ref "SV4") (pin "7") (pinfunction "7_7") (pintype "passive"))
      (node (ref "U1") (pin "V19") (pinfunction "IO_L12P_T1_MRCC_13_V19") (pintype "bidirectional"))
    )
    (net (code "48") (name "Net-(U1C-IO_L13N_T2_MRCC_13)") (class "Default")
      (node (ref "SV4") (pin "4") (pinfunction "4_4") (pintype "passive"))
      (node (ref "U1") (pin "Y19") (pinfunction "IO_L13N_T2_MRCC_13_Y19") (pintype "bidirectional"))
    )
    (net (code "49") (name "Net-(U1C-IO_L13P_T2_MRCC_13)") (class "Default")
      (node (ref "SV4") (pin "5") (pinfunction "5_5") (pintype "passive"))
      (node (ref "U1") (pin "Y18") (pinfunction "IO_L13P_T2_MRCC_13_Y18") (pintype "bidirectional"))
    )
    (net (code "50") (name "Net-(U1C-IO_L14N_T2_SRCC_13)") (class "Default")
      (node (ref "SV4") (pin "2") (pinfunction "2_2") (pintype "passive"))
      (node (ref "U1") (pin "Y17") (pinfunction "IO_L14N_T2_SRCC_13_Y17") (pintype "bidirectional"))
    )
    (net (code "51") (name "Net-(U1C-IO_L14P_T2_SRCC_13)") (class "Default")
      (node (ref "SV4") (pin "3") (pinfunction "3_3") (pintype "passive"))
      (node (ref "U1") (pin "W17") (pinfunction "IO_L14P_T2_SRCC_13_W17") (pintype "bidirectional"))
    )
    (net (code "52") (name "Net-(U1C-IO_L15N_T2_DQS_13)") (class "Default")
      (node (ref "SV5") (pin "10") (pinfunction "10_10") (pintype "passive"))
      (node (ref "U1") (pin "AB18") (pinfunction "IO_L15N_T2_DQS_13_AB18") (pintype "bidirectional"))
    )
    (net (code "53") (name "Net-(U1C-IO_L15P_T2_DQS_13)") (class "Default")
      (node (ref "SV4") (pin "1") (pinfunction "1_1") (pintype "passive"))
      (node (ref "U1") (pin "AA18") (pinfunction "IO_L15P_T2_DQS_13_AA18") (pintype "bidirectional"))
    )
    (net (code "54") (name "Net-(U1C-IO_L16N_T2_13)") (class "Default")
      (node (ref "SV5") (pin "8") (pinfunction "8_8") (pintype "passive"))
      (node (ref "U1") (pin "AB16") (pinfunction "IO_L16N_T2_13_AB16") (pintype "bidirectional"))
    )
    (net (code "55") (name "Net-(U1C-IO_L16P_T2_13)") (class "Default")
      (node (ref "SV5") (pin "9") (pinfunction "9_9") (pintype "passive"))
      (node (ref "U1") (pin "AB15") (pinfunction "IO_L16P_T2_13_AB15") (pintype "bidirectional"))
    )
    (net (code "56") (name "Net-(U1C-IO_L17N_T2_13)") (class "Default")
      (node (ref "SV5") (pin "6") (pinfunction "6_6") (pintype "passive"))
      (node (ref "U1") (pin "AB17") (pinfunction "IO_L17N_T2_13_AB17") (pintype "bidirectional"))
    )
    (net (code "57") (name "Net-(U1C-IO_L17P_T2_13)") (class "Default")
      (node (ref "SV5") (pin "7") (pinfunction "7_7") (pintype "passive"))
      (node (ref "U1") (pin "AA16") (pinfunction "IO_L17P_T2_13_AA16") (pintype "bidirectional"))
    )
    (net (code "58") (name "Net-(U1C-IO_L18N_T2_13)") (class "Default")
      (node (ref "SV5") (pin "4") (pinfunction "4_4") (pintype "passive"))
      (node (ref "U1") (pin "AA15") (pinfunction "IO_L18N_T2_13_AA15") (pintype "bidirectional"))
    )
    (net (code "59") (name "Net-(U1C-IO_L18P_T2_13)") (class "Default")
      (node (ref "SV5") (pin "5") (pinfunction "5_5") (pintype "passive"))
      (node (ref "U1") (pin "AA14") (pinfunction "IO_L18P_T2_13_AA14") (pintype "bidirectional"))
    )
    (net (code "60") (name "Net-(U1C-IO_L19N_T3_VREF_13)") (class "Default")
      (node (ref "SV5") (pin "2") (pinfunction "2_2") (pintype "passive"))
      (node (ref "U1") (pin "V17") (pinfunction "IO_L19N_T3_VREF_13_V17") (pintype "bidirectional"))
    )
    (net (code "61") (name "Net-(U1C-IO_L19P_T3_13)") (class "Default")
      (node (ref "SV5") (pin "3") (pinfunction "3_3") (pintype "passive"))
      (node (ref "U1") (pin "U16") (pinfunction "IO_L19P_T3_13_U16") (pintype "bidirectional"))
    )
    (net (code "62") (name "Net-(U1C-IO_L20N_T3_13)") (class "Default")
      (node (ref "SV6") (pin "10") (pinfunction "10_10") (pintype "passive"))
      (node (ref "U1") (pin "T16") (pinfunction "IO_L20N_T3_13_T16") (pintype "bidirectional"))
    )
    (net (code "63") (name "Net-(U1C-IO_L20P_T3_13)") (class "Default")
      (node (ref "SV5") (pin "1") (pinfunction "1_1") (pintype "passive"))
      (node (ref "U1") (pin "R16") (pinfunction "IO_L20P_T3_13_R16") (pintype "bidirectional"))
    )
    (net (code "64") (name "Net-(U1C-IO_L21N_T3_DQS_13)") (class "Default")
      (node (ref "SV6") (pin "8") (pinfunction "8_8") (pintype "passive"))
      (node (ref "U1") (pin "Y16") (pinfunction "IO_L21N_T3_DQS_13_Y16") (pintype "bidirectional"))
    )
    (net (code "65") (name "Net-(U1C-IO_L21P_T3_DQS_13)") (class "Default")
      (node (ref "SV6") (pin "9") (pinfunction "9_9") (pintype "passive"))
      (node (ref "U1") (pin "W16") (pinfunction "IO_L21P_T3_DQS_13_W16") (pintype "bidirectional"))
    )
    (net (code "66") (name "Net-(U1C-IO_L22N_T3_13)") (class "Default")
      (node (ref "SV6") (pin "6") (pinfunction "6_6") (pintype "passive"))
      (node (ref "U1") (pin "Y14") (pinfunction "IO_L22N_T3_13_Y14") (pintype "bidirectional"))
    )
    (net (code "67") (name "Net-(U1C-IO_L22P_T3_13)") (class "Default")
      (node (ref "SV6") (pin "7") (pinfunction "7_7") (pintype "passive"))
      (node (ref "U1") (pin "W14") (pinfunction "IO_L22P_T3_13_W14") (pintype "bidirectional"))
    )
    (net (code "68") (name "Net-(U1C-IO_L23N_T3_13)") (class "Default")
      (node (ref "SV6") (pin "4") (pinfunction "4_4") (pintype "passive"))
      (node (ref "U1") (pin "W15") (pinfunction "IO_L23N_T3_13_W15") (pintype "bidirectional"))
    )
    (net (code "69") (name "Net-(U1C-IO_L23P_T3_13)") (class "Default")
      (node (ref "SV6") (pin "5") (pinfunction "5_5") (pintype "passive"))
      (node (ref "U1") (pin "V15") (pinfunction "IO_L23P_T3_13_V15") (pintype "bidirectional"))
    )
    (net (code "70") (name "Net-(U1C-IO_L24N_T3_13)") (class "Default")
      (node (ref "SV6") (pin "2") (pinfunction "2_2") (pintype "passive"))
      (node (ref "U1") (pin "U15") (pinfunction "IO_L24N_T3_13_U15") (pintype "bidirectional"))
    )
    (net (code "71") (name "Net-(U1C-IO_L24P_T3_13)") (class "Default")
      (node (ref "SV6") (pin "3") (pinfunction "3_3") (pintype "passive"))
      (node (ref "U1") (pin "T15") (pinfunction "IO_L24P_T3_13_T15") (pintype "bidirectional"))
    )
    (net (code "72") (name "Net-(U1D-IO_0_14)") (class "Default")
      (node (ref "SV7") (pin "10") (pinfunction "10_10") (pintype "passive"))
      (node (ref "U1") (pin "K16") (pinfunction "IO_0_14_K16") (pintype "bidirectional"))
    )
    (net (code "73") (name "Net-(U1D-IO_25_14)") (class "Default")
      (node (ref "SV11") (pin "1") (pinfunction "1_1") (pintype "passive"))
      (node (ref "U1") (pin "M16") (pinfunction "IO_25_14_M16") (pintype "bidirectional"))
    )
    (net (code "74") (name "Net-(U1D-IO_L1N_T0_D01_DIN_14)") (class "Default")
      (node (ref "SV7") (pin "8") (pinfunction "8_8") (pintype "passive"))
      (node (ref "U1") (pin "H19") (pinfunction "IO_L1N_T0_D01_DIN_14_H19") (pintype "bidirectional"))
    )
    (net (code "75") (name "Net-(U1D-IO_L1P_T0_D00_MOSI_14)") (class "Default")
      (node (ref "SV7") (pin "9") (pinfunction "9_9") (pintype "passive"))
      (node (ref "U1") (pin "H18") (pinfunction "IO_L1P_T0_D00_MOSI_14_H18") (pintype "bidirectional"))
    )
    (net (code "76") (name "Net-(U1D-IO_L2N_T0_D03_14)") (class "Default")
      (node (ref "SV7") (pin "6") (pinfunction "6_6") (pintype "passive"))
      (node (ref "U1") (pin "F19") (pinfunction "IO_L2N_T0_D03_14_F19") (pintype "bidirectional"))
    )
    (net (code "77") (name "Net-(U1D-IO_L2P_T0_D02_14)") (class "Default")
      (node (ref "SV7") (pin "7") (pinfunction "7_7") (pintype "passive"))
      (node (ref "U1") (pin "G18") (pinfunction "IO_L2P_T0_D02_14_G18") (pintype "bidirectional"))
    )
    (net (code "78") (name "Net-(U1D-IO_L3N_T0_DQS_EMCCLK_14)") (class "Default")
      (node (ref "SV7") (pin "4") (pinfunction "4_4") (pintype "passive"))
      (node (ref "U1") (pin "J19") (pinfunction "IO_L3N_T0_DQS_EMCCLK_14_J19") (pintype "bidirectional"))
    )
    (net (code "79") (name "Net-(U1D-IO_L3P_T0_DQS_PUDC_B_14)") (class "Default")
      (node (ref "SV7") (pin "5") (pinfunction "5_5") (pintype "passive"))
      (node (ref "U1") (pin "K18") (pinfunction "IO_L3P_T0_DQS_PUDC_B_14_K18") (pintype "bidirectional"))
    )
    (net (code "80") (name "Net-(U1D-IO_L4N_T0_D05_14)") (class "Default")
      (node (ref "SV7") (pin "2") (pinfunction "2_2") (pintype "passive"))
      (node (ref "U1") (pin "F20") (pinfunction "IO_L4N_T0_D05_14_F20") (pintype "bidirectional"))
    )
    (net (code "81") (name "Net-(U1D-IO_L4P_T0_D04_14)") (class "Default")
      (node (ref "SV7") (pin "3") (pinfunction "3_3") (pintype "passive"))
      (node (ref "U1") (pin "G20") (pinfunction "IO_L4P_T0_D04_14_G20") (pintype "bidirectional"))
    )
    (net (code "82") (name "Net-(U1D-IO_L5N_T0_D07_14)") (class "Default")
      (node (ref "SV8") (pin "10") (pinfunction "10_10") (pintype "passive"))
      (node (ref "U1") (pin "K19") (pinfunction "IO_L5N_T0_D07_14_K19") (pintype "bidirectional"))
    )
    (net (code "83") (name "Net-(U1D-IO_L5P_T0_D06_14)") (class "Default")
      (node (ref "SV7") (pin "1") (pinfunction "1_1") (pintype "passive"))
      (node (ref "U1") (pin "L18") (pinfunction "IO_L5P_T0_D06_14_L18") (pintype "bidirectional"))
    )
    (net (code "84") (name "Net-(U1D-IO_L6N_T0_D08_VREF_14)") (class "Default")
      (node (ref "SV8") (pin "8") (pinfunction "8_8") (pintype "passive"))
      (node (ref "U1") (pin "K17") (pinfunction "IO_L6N_T0_D08_VREF_14_K17") (pintype "bidirectional"))
    )
    (net (code "85") (name "Net-(U1D-IO_L6P_T0_FCS_B_14)") (class "Default")
      (node (ref "SV8") (pin "9") (pinfunction "9_9") (pintype "passive"))
      (node (ref "U1") (pin "L16") (pinfunction "IO_L6P_T0_FCS_B_14_L16") (pintype "bidirectional"))
    )
    (net (code "86") (name "Net-(U1D-IO_L7N_T1_D10_14)") (class "Default")
      (node (ref "SV8") (pin "6") (pinfunction "6_6") (pintype "passive"))
      (node (ref "U1") (pin "E22") (pinfunction "IO_L7N_T1_D10_14_E22") (pintype "bidirectional"))
    )
    (net (code "87") (name "Net-(U1D-IO_L7P_T1_D09_14)") (class "Default")
      (node (ref "SV8") (pin "7") (pinfunction "7_7") (pintype "passive"))
      (node (ref "U1") (pin "E21") (pinfunction "IO_L7P_T1_D09_14_E21") (pintype "bidirectional"))
    )
    (net (code "88") (name "Net-(U1D-IO_L8N_T1_D12_14)") (class "Default")
      (node (ref "SV8") (pin "4") (pinfunction "4_4") (pintype "passive"))
      (node (ref "U1") (pin "G22") (pinfunction "IO_L8N_T1_D12_14_G22") (pintype "bidirectional"))
    )
    (net (code "89") (name "Net-(U1D-IO_L8P_T1_D11_14)") (class "Default")
      (node (ref "SV8") (pin "5") (pinfunction "5_5") (pintype "passive"))
      (node (ref "U1") (pin "H22") (pinfunction "IO_L8P_T1_D11_14_H22") (pintype "bidirectional"))
    )
    (net (code "90") (name "Net-(U1D-IO_L9N_T1_DQS_D13_14)") (class "Default")
      (node (ref "SV8") (pin "2") (pinfunction "2_2") (pintype "passive"))
      (node (ref "U1") (pin "F21") (pinfunction "IO_L9N_T1_DQS_D13_14_F21") (pintype "bidirectional"))
    )
    (net (code "91") (name "Net-(U1D-IO_L9P_T1_DQS_14)") (class "Default")
      (node (ref "SV8") (pin "3") (pinfunction "3_3") (pintype "passive"))
      (node (ref "U1") (pin "G21") (pinfunction "IO_L9P_T1_DQS_14_G21") (pintype "bidirectional"))
    )
    (net (code "92") (name "Net-(U1D-IO_L10N_T1_D15_14)") (class "Default")
      (node (ref "SV9") (pin "10") (pinfunction "10_10") (pintype "passive"))
      (node (ref "U1") (pin "J22") (pinfunction "IO_L10N_T1_D15_14_J22") (pintype "bidirectional"))
    )
    (net (code "93") (name "Net-(U1D-IO_L10P_T1_D14_14)") (class "Default")
      (node (ref "SV8") (pin "1") (pinfunction "1_1") (pintype "passive"))
      (node (ref "U1") (pin "J21") (pinfunction "IO_L10P_T1_D14_14_J21") (pintype "bidirectional"))
    )
    (net (code "94") (name "Net-(U1D-IO_L11N_T1_SRCC_14)") (class "Default")
      (node (ref "SV9") (pin "8") (pinfunction "8_8") (pintype "passive"))
      (node (ref "U1") (pin "H20") (pinfunction "IO_L11N_T1_SRCC_14_H20") (pintype "bidirectional"))
    )
    (net (code "95") (name "Net-(U1D-IO_L11P_T1_SRCC_14)") (class "Default")
      (node (ref "SV9") (pin "9") (pinfunction "9_9") (pintype "passive"))
      (node (ref "U1") (pin "J20") (pinfunction "IO_L11P_T1_SRCC_14_J20") (pintype "bidirectional"))
    )
    (net (code "96") (name "Net-(U1D-IO_L12N_T1_MRCC_14)") (class "Default")
      (node (ref "SV9") (pin "6") (pinfunction "6_6") (pintype "passive"))
      (node (ref "U1") (pin "L20") (pinfunction "IO_L12N_T1_MRCC_14_L20") (pintype "bidirectional"))
    )
    (net (code "97") (name "Net-(U1D-IO_L12P_T1_MRCC_14)") (class "Default")
      (node (ref "SV9") (pin "7") (pinfunction "7_7") (pintype "passive"))
      (node (ref "U1") (pin "L19") (pinfunction "IO_L12P_T1_MRCC_14_L19") (pintype "bidirectional"))
    )
    (net (code "98") (name "Net-(U1D-IO_L13N_T2_MRCC_14)") (class "Default")
      (node (ref "SV9") (pin "4") (pinfunction "4_4") (pintype "passive"))
      (node (ref "U1") (pin "N19") (pinfunction "IO_L13N_T2_MRCC_14_N19") (pintype "bidirectional"))
    )
    (net (code "99") (name "Net-(U1D-IO_L13P_T2_MRCC_14)") (class "Default")
      (node (ref "SV9") (pin "5") (pinfunction "5_5") (pintype "passive"))
      (node (ref "U1") (pin "N18") (pinfunction "IO_L13P_T2_MRCC_14_N18") (pintype "bidirectional"))
    )
    (net (code "100") (name "Net-(U1D-IO_L14N_T2_SRCC_14)") (class "Default")
      (node (ref "SV9") (pin "2") (pinfunction "2_2") (pintype "passive"))
      (node (ref "U1") (pin "M18") (pinfunction "IO_L14N_T2_SRCC_14_M18") (pintype "bidirectional"))
    )
    (net (code "101") (name "Net-(U1D-IO_L14P_T2_SRCC_14)") (class "Default")
      (node (ref "SV9") (pin "3") (pinfunction "3_3") (pintype "passive"))
      (node (ref "U1") (pin "M17") (pinfunction "IO_L14P_T2_SRCC_14_M17") (pintype "bidirectional"))
    )
    (net (code "102") (name "Net-(U1D-IO_L15N_T2_DQS_DOUT_CSO_B_14)") (class "Default")
      (node (ref "SV10") (pin "10") (pinfunction "10_10") (pintype "passive"))
      (node (ref "U1") (pin "M22") (pinfunction "IO_L15N_T2_DQS_DOUT_CSO_B_14_M22") (pintype "bidirectional"))
    )
    (net (code "103") (name "Net-(U1D-IO_L15P_T2_DQS_RDWR_B_14)") (class "Default")
      (node (ref "SV9") (pin "1") (pinfunction "1_1") (pintype "passive"))
      (node (ref "U1") (pin "N22") (pinfunction "IO_L15P_T2_DQS_RDWR_B_14_N22") (pintype "bidirectional"))
    )
    (net (code "104") (name "Net-(U1D-IO_L16N_T2_A15_D31_14)") (class "Default")
      (node (ref "SV10") (pin "8") (pinfunction "8_8") (pintype "passive"))
      (node (ref "U1") (pin "K22") (pinfunction "IO_L16N_T2_A15_D31_14_K22") (pintype "bidirectional"))
    )
    (net (code "105") (name "Net-(U1D-IO_L16P_T2_CSI_B_14)") (class "Default")
      (node (ref "SV10") (pin "9") (pinfunction "9_9") (pintype "passive"))
      (node (ref "U1") (pin "K21") (pinfunction "IO_L16P_T2_CSI_B_14_K21") (pintype "bidirectional"))
    )
    (net (code "106") (name "Net-(U1D-IO_L17N_T2_A13_D29_14)") (class "Default")
      (node (ref "SV10") (pin "6") (pinfunction "6_6") (pintype "passive"))
      (node (ref "U1") (pin "M21") (pinfunction "IO_L17N_T2_A13_D29_14_M21") (pintype "bidirectional"))
    )
    (net (code "107") (name "Net-(U1D-IO_L17P_T2_A14_D30_14)") (class "Default")
      (node (ref "SV10") (pin "7") (pinfunction "7_7") (pintype "passive"))
      (node (ref "U1") (pin "N20") (pinfunction "IO_L17P_T2_A14_D30_14_N20") (pintype "bidirectional"))
    )
    (net (code "108") (name "Net-(U1D-IO_L18N_T2_A11_D27_14)") (class "Default")
      (node (ref "SV10") (pin "4") (pinfunction "4_4") (pintype "passive"))
      (node (ref "U1") (pin "L21") (pinfunction "IO_L18N_T2_A11_D27_14_L21") (pintype "bidirectional"))
    )
    (net (code "109") (name "Net-(U1D-IO_L18P_T2_A12_D28_14)") (class "Default")
      (node (ref "SV10") (pin "5") (pinfunction "5_5") (pintype "passive"))
      (node (ref "U1") (pin "M20") (pinfunction "IO_L18P_T2_A12_D28_14_M20") (pintype "bidirectional"))
    )
    (net (code "110") (name "Net-(U1D-IO_L19N_T3_A09_D25_VREF_14)") (class "Default")
      (node (ref "SV10") (pin "2") (pinfunction "2_2") (pintype "passive"))
      (node (ref "U1") (pin "R19") (pinfunction "IO_L19N_T3_A09_D25_VREF_14_R19") (pintype "bidirectional"))
    )
    (net (code "111") (name "Net-(U1D-IO_L19P_T3_A10_D26_14)") (class "Default")
      (node (ref "SV10") (pin "3") (pinfunction "3_3") (pintype "passive"))
      (node (ref "U1") (pin "R18") (pinfunction "IO_L19P_T3_A10_D26_14_R18") (pintype "bidirectional"))
    )
    (net (code "112") (name "Net-(U1D-IO_L20N_T3_A07_D23_14)") (class "Default")
      (node (ref "SV11") (pin "10") (pinfunction "10_10") (pintype "passive"))
      (node (ref "U1") (pin "P20") (pinfunction "IO_L20N_T3_A07_D23_14_P20") (pintype "bidirectional"))
    )
    (net (code "113") (name "Net-(U1D-IO_L20P_T3_A08_D24_14)") (class "Default")
      (node (ref "SV10") (pin "1") (pinfunction "1_1") (pintype "passive"))
      (node (ref "U1") (pin "P19") (pinfunction "IO_L20P_T3_A08_D24_14_P19") (pintype "bidirectional"))
    )
    (net (code "114") (name "Net-(U1D-IO_L21N_T3_DQS_A06_D22_14)") (class "Default")
      (node (ref "SV11") (pin "8") (pinfunction "8_8") (pintype "passive"))
      (node (ref "U1") (pin "P17") (pinfunction "IO_L21N_T3_DQS_A06_D22_14_P17") (pintype "bidirectional"))
    )
    (net (code "115") (name "Net-(U1D-IO_L21P_T3_DQS_14)") (class "Default")
      (node (ref "SV11") (pin "9") (pinfunction "9_9") (pintype "passive"))
      (node (ref "U1") (pin "R17") (pinfunction "IO_L21P_T3_DQS_14_R17") (pintype "bidirectional"))
    )
    (net (code "116") (name "Net-(U1D-IO_L22N_T3_A04_D20_14)") (class "Default")
      (node (ref "SV11") (pin "6") (pinfunction "6_6") (pintype "passive"))
      (node (ref "U1") (pin "P22") (pinfunction "IO_L22N_T3_A04_D20_14_P22") (pintype "bidirectional"))
    )
    (net (code "117") (name "Net-(U1D-IO_L22P_T3_A05_D21_14)") (class "Default")
      (node (ref "SV11") (pin "7") (pinfunction "7_7") (pintype "passive"))
      (node (ref "U1") (pin "P21") (pinfunction "IO_L22P_T3_A05_D21_14_P21") (pintype "bidirectional"))
    )
    (net (code "118") (name "Net-(U1D-IO_L23N_T3_A02_D18_14)") (class "Default")
      (node (ref "SV11") (pin "4") (pinfunction "4_4") (pintype "passive"))
      (node (ref "U1") (pin "N17") (pinfunction "IO_L23N_T3_A02_D18_14_N17") (pintype "bidirectional"))
    )
    (net (code "119") (name "Net-(U1D-IO_L23P_T3_A03_D19_14)") (class "Default")
      (node (ref "SV11") (pin "5") (pinfunction "5_5") (pintype "passive"))
      (node (ref "U1") (pin "P16") (pinfunction "IO_L23P_T3_A03_D19_14_P16") (pintype "bidirectional"))
    )
    (net (code "120") (name "Net-(U1D-IO_L24N_T3_A00_D16_14)") (class "Default")
      (node (ref "SV11") (pin "2") (pinfunction "2_2") (pintype "passive"))
      (node (ref "U1") (pin "R22") (pinfunction "IO_L24N_T3_A00_D16_14_R22") (pintype "bidirectional"))
    )
    (net (code "121") (name "Net-(U1D-IO_L24P_T3_A01_D17_14)") (class "Default")
      (node (ref "SV11") (pin "3") (pinfunction "3_3") (pintype "passive"))
      (node (ref "U1") (pin "R21") (pinfunction "IO_L24P_T3_A01_D17_14_R21") (pintype "bidirectional"))
    )
    (net (code "122") (name "Net-(U1E-IO_0_15)") (class "Default")
      (node (ref "SV12") (pin "10") (pinfunction "10_10") (pintype "passive"))
      (node (ref "U1") (pin "D12") (pinfunction "IO_0_15_D12") (pintype "bidirectional"))
    )
    (net (code "123") (name "Net-(U1E-IO_25_15)") (class "Default")
      (node (ref "SV16") (pin "1") (pinfunction "1_1") (pintype "passive"))
      (node (ref "U1") (pin "H15") (pinfunction "IO_25_15_H15") (pintype "bidirectional"))
    )
    (net (code "124") (name "Net-(U1E-IO_L1N_T0_AD0N_15)") (class "Default")
      (node (ref "SV12") (pin "8") (pinfunction "8_8") (pintype "passive"))
      (node (ref "U1") (pin "G16") (pinfunction "IO_L1N_T0_AD0N_15_G16") (pintype "bidirectional"))
    )
    (net (code "125") (name "Net-(U1E-IO_L1P_T0_AD0P_15)") (class "Default")
      (node (ref "SV12") (pin "9") (pinfunction "9_9") (pintype "passive"))
      (node (ref "U1") (pin "G15") (pinfunction "IO_L1P_T0_AD0P_15_G15") (pintype "bidirectional"))
    )
    (net (code "126") (name "Net-(U1E-IO_L2N_T0_AD8N_15)") (class "Default")
      (node (ref "SV12") (pin "6") (pinfunction "6_6") (pintype "passive"))
      (node (ref "U1") (pin "B12") (pinfunction "IO_L2N_T0_AD8N_15_B12") (pintype "bidirectional"))
    )
    (net (code "127") (name "Net-(U1E-IO_L2P_T0_AD8P_15)") (class "Default")
      (node (ref "SV12") (pin "7") (pinfunction "7_7") (pintype "passive"))
      (node (ref "U1") (pin "C12") (pinfunction "IO_L2P_T0_AD8P_15_C12") (pintype "bidirectional"))
    )
    (net (code "128") (name "Net-(U1E-IO_L3N_T0_DQS_AD1N_15)") (class "Default")
      (node (ref "SV12") (pin "4") (pinfunction "4_4") (pintype "passive"))
      (node (ref "U1") (pin "F16") (pinfunction "IO_L3N_T0_DQS_AD1N_15_F16") (pintype "bidirectional"))
    )
    (net (code "129") (name "Net-(U1E-IO_L3P_T0_DQS_AD1P_15)") (class "Default")
      (node (ref "SV12") (pin "5") (pinfunction "5_5") (pintype "passive"))
      (node (ref "U1") (pin "F15") (pinfunction "IO_L3P_T0_DQS_AD1P_15_F15") (pintype "bidirectional"))
    )
    (net (code "130") (name "Net-(U1E-IO_L4N_T0_AD9N_15)") (class "Default")
      (node (ref "SV12") (pin "2") (pinfunction "2_2") (pintype "passive"))
      (node (ref "U1") (pin "A14") (pinfunction "IO_L4N_T0_AD9N_15_A14") (pintype "bidirectional"))
    )
    (net (code "131") (name "Net-(U1E-IO_L4P_T0_AD9P_15)") (class "Default")
      (node (ref "SV12") (pin "3") (pinfunction "3_3") (pintype "passive"))
      (node (ref "U1") (pin "A13") (pinfunction "IO_L4P_T0_AD9P_15_A13") (pintype "bidirectional"))
    )
    (net (code "132") (name "Net-(U1E-IO_L5N_T0_AD2N_15)") (class "Default")
      (node (ref "SV13") (pin "10") (pinfunction "10_10") (pintype "passive"))
      (node (ref "U1") (pin "B13") (pinfunction "IO_L5N_T0_AD2N_15_B13") (pintype "bidirectional"))
    )
    (net (code "133") (name "Net-(U1E-IO_L5P_T0_AD2P_15)") (class "Default")
      (node (ref "SV12") (pin "1") (pinfunction "1_1") (pintype "passive"))
      (node (ref "U1") (pin "C13") (pinfunction "IO_L5P_T0_AD2P_15_C13") (pintype "bidirectional"))
    )
    (net (code "134") (name "Net-(U1E-IO_L6N_T0_VREF_15)") (class "Default")
      (node (ref "SV13") (pin "8") (pinfunction "8_8") (pintype "passive"))
      (node (ref "U1") (pin "D14") (pinfunction "IO_L6N_T0_VREF_15_D14") (pintype "bidirectional"))
    )
    (net (code "135") (name "Net-(U1E-IO_L6P_T0_15)") (class "Default")
      (node (ref "SV13") (pin "9") (pinfunction "9_9") (pintype "passive"))
      (node (ref "U1") (pin "E14") (pinfunction "IO_L6P_T0_15_E14") (pintype "bidirectional"))
    )
    (net (code "136") (name "Net-(U1E-IO_L7N_T1_AD10N_15)") (class "Default")
      (node (ref "SV13") (pin "6") (pinfunction "6_6") (pintype "passive"))
      (node (ref "U1") (pin "C15") (pinfunction "IO_L7N_T1_AD10N_15_C15") (pintype "bidirectional"))
    )
    (net (code "137") (name "Net-(U1E-IO_L7P_T1_AD10P_15)") (class "Default")
      (node (ref "SV13") (pin "7") (pinfunction "7_7") (pintype "passive"))
      (node (ref "U1") (pin "C14") (pinfunction "IO_L7P_T1_AD10P_15_C14") (pintype "bidirectional"))
    )
    (net (code "138") (name "Net-(U1E-IO_L8N_T1_AD3N_15)") (class "Default")
      (node (ref "SV13") (pin "4") (pinfunction "4_4") (pintype "passive"))
      (node (ref "U1") (pin "A16") (pinfunction "IO_L8N_T1_AD3N_15_A16") (pintype "bidirectional"))
    )
    (net (code "139") (name "Net-(U1E-IO_L8P_T1_AD3P_15)") (class "Default")
      (node (ref "SV13") (pin "5") (pinfunction "5_5") (pintype "passive"))
      (node (ref "U1") (pin "B16") (pinfunction "IO_L8P_T1_AD3P_15_B16") (pintype "bidirectional"))
    )
    (net (code "140") (name "Net-(U1E-IO_L9N_T1_DQS_AD11N_15)") (class "Default")
      (node (ref "SV13") (pin "2") (pinfunction "2_2") (pintype "passive"))
      (node (ref "U1") (pin "A15") (pinfunction "IO_L9N_T1_DQS_AD11N_15_A15") (pintype "bidirectional"))
    )
    (net (code "141") (name "Net-(U1E-IO_L9P_T1_DQS_AD11P_15)") (class "Default")
      (node (ref "SV13") (pin "3") (pinfunction "3_3") (pintype "passive"))
      (node (ref "U1") (pin "B15") (pinfunction "IO_L9P_T1_DQS_AD11P_15_B15") (pintype "bidirectional"))
    )
    (net (code "142") (name "Net-(U1E-IO_L10N_T1_AD4N_15)") (class "Default")
      (node (ref "SV14") (pin "10") (pinfunction "10_10") (pintype "passive"))
      (node (ref "U1") (pin "A18") (pinfunction "IO_L10N_T1_AD4N_15_A18") (pintype "bidirectional"))
    )
    (net (code "143") (name "Net-(U1E-IO_L10P_T1_AD4P_15)") (class "Default")
      (node (ref "SV13") (pin "1") (pinfunction "1_1") (pintype "passive"))
      (node (ref "U1") (pin "B17") (pinfunction "IO_L10P_T1_AD4P_15_B17") (pintype "bidirectional"))
    )
    (net (code "144") (name "Net-(U1E-IO_L11N_T1_SRCC_AD12N_15)") (class "Default")
      (node (ref "SV14") (pin "8") (pinfunction "8_8") (pintype "passive"))
      (node (ref "U1") (pin "D16") (pinfunction "IO_L11N_T1_SRCC_AD12N_15_D16") (pintype "bidirectional"))
    )
    (net (code "145") (name "Net-(U1E-IO_L11P_T1_SRCC_AD12P_15)") (class "Default")
      (node (ref "SV14") (pin "9") (pinfunction "9_9") (pintype "passive"))
      (node (ref "U1") (pin "D15") (pinfunction "IO_L11P_T1_SRCC_AD12P_15_D15") (pintype "bidirectional"))
    )
    (net (code "146") (name "Net-(U1E-IO_L12N_T1_MRCC_AD5N_15)") (class "Default")
      (node (ref "SV14") (pin "6") (pinfunction "6_6") (pintype "passive"))
      (node (ref "U1") (pin "C18") (pinfunction "IO_L12N_T1_MRCC_AD5N_15_C18") (pintype "bidirectional"))
    )
    (net (code "147") (name "Net-(U1E-IO_L12P_T1_MRCC_AD5P_15)") (class "Default")
      (node (ref "SV14") (pin "7") (pinfunction "7_7") (pintype "passive"))
      (node (ref "U1") (pin "C17") (pinfunction "IO_L12P_T1_MRCC_AD5P_15_C17") (pintype "bidirectional"))
    )
    (net (code "148") (name "Net-(U1E-IO_L13N_T2_MRCC_15)") (class "Default")
      (node (ref "SV14") (pin "4") (pinfunction "4_4") (pintype "passive"))
      (node (ref "U1") (pin "E18") (pinfunction "IO_L13N_T2_MRCC_15_E18") (pintype "bidirectional"))
    )
    (net (code "149") (name "Net-(U1E-IO_L13P_T2_MRCC_15)") (class "Default")
      (node (ref "SV14") (pin "5") (pinfunction "5_5") (pintype "passive"))
      (node (ref "U1") (pin "E17") (pinfunction "IO_L13P_T2_MRCC_15_E17") (pintype "bidirectional"))
    )
    (net (code "150") (name "Net-(U1E-IO_L14N_T2_SRCC_15)") (class "Default")
      (node (ref "SV14") (pin "2") (pinfunction "2_2") (pintype "passive"))
      (node (ref "U1") (pin "D17") (pinfunction "IO_L14N_T2_SRCC_15_D17") (pintype "bidirectional"))
    )
    (net (code "151") (name "Net-(U1E-IO_L14P_T2_SRCC_15)") (class "Default")
      (node (ref "SV14") (pin "3") (pinfunction "3_3") (pintype "passive"))
      (node (ref "U1") (pin "E16") (pinfunction "IO_L14P_T2_SRCC_15_E16") (pintype "bidirectional"))
    )
    (net (code "152") (name "Net-(U1E-IO_L15N_T2_DQS_ADV_B_15)") (class "Default")
      (node (ref "SV15") (pin "10") (pinfunction "10_10") (pintype "passive"))
      (node (ref "U1") (pin "G17") (pinfunction "IO_L15N_T2_DQS_ADV_B_15_G17") (pintype "bidirectional"))
    )
    (net (code "153") (name "Net-(U1E-IO_L15P_T2_DQS_15)") (class "Default")
      (node (ref "SV14") (pin "1") (pinfunction "1_1") (pintype "passive"))
      (node (ref "U1") (pin "H17") (pinfunction "IO_L15P_T2_DQS_15_H17") (pintype "bidirectional"))
    )
    (net (code "154") (name "Net-(U1E-IO_L16N_T2_A27_15)") (class "Default")
      (node (ref "SV15") (pin "8") (pinfunction "8_8") (pintype "passive"))
      (node (ref "U1") (pin "J17") (pinfunction "IO_L16N_T2_A27_15_J17") (pintype "bidirectional"))
    )
    (net (code "155") (name "Net-(U1E-IO_L16P_T2_A28_15)") (class "Default")
      (node (ref "SV15") (pin "9") (pinfunction "9_9") (pintype "passive"))
      (node (ref "U1") (pin "J16") (pinfunction "IO_L16P_T2_A28_15_J16") (pintype "bidirectional"))
    )
    (net (code "156") (name "Net-(U1E-IO_L17N_T2_A25_15)") (class "Default")
      (node (ref "SV15") (pin "6") (pinfunction "6_6") (pintype "passive"))
      (node (ref "U1") (pin "E19") (pinfunction "IO_L17N_T2_A25_15_E19") (pintype "bidirectional"))
    )
    (net (code "157") (name "Net-(U1E-IO_L17P_T2_A26_15)") (class "Default")
      (node (ref "SV15") (pin "7") (pinfunction "7_7") (pintype "passive"))
      (node (ref "U1") (pin "F18") (pinfunction "IO_L17P_T2_A26_15_F18") (pintype "bidirectional"))
    )
    (net (code "158") (name "Net-(U1E-IO_L18N_T2_A23_15)") (class "Default")
      (node (ref "SV15") (pin "4") (pinfunction "4_4") (pintype "passive"))
      (node (ref "U1") (pin "D20") (pinfunction "IO_L18N_T2_A23_15_D20") (pintype "bidirectional"))
    )
    (net (code "159") (name "Net-(U1E-IO_L18P_T2_A24_15)") (class "Default")
      (node (ref "SV15") (pin "5") (pinfunction "5_5") (pintype "passive"))
      (node (ref "U1") (pin "D19") (pinfunction "IO_L18P_T2_A24_15_D19") (pintype "bidirectional"))
    )
    (net (code "160") (name "Net-(U1E-IO_L19N_T3_A21_VREF_15)") (class "Default")
      (node (ref "SV15") (pin "2") (pinfunction "2_2") (pintype "passive"))
      (node (ref "U1") (pin "C20") (pinfunction "IO_L19N_T3_A21_VREF_15_C20") (pintype "bidirectional"))
    )
    (net (code "161") (name "Net-(U1E-IO_L19P_T3_A22_15)") (class "Default")
      (node (ref "SV15") (pin "3") (pinfunction "3_3") (pintype "passive"))
      (node (ref "U1") (pin "C19") (pinfunction "IO_L19P_T3_A22_15_C19") (pintype "bidirectional"))
    )
    (net (code "162") (name "Net-(U1E-IO_L20N_T3_A19_15)") (class "Default")
      (node (ref "SV16") (pin "10") (pinfunction "10_10") (pintype "passive"))
      (node (ref "U1") (pin "A19") (pinfunction "IO_L20N_T3_A19_15_A19") (pintype "bidirectional"))
    )
    (net (code "163") (name "Net-(U1E-IO_L20P_T3_A20_15)") (class "Default")
      (node (ref "SV15") (pin "1") (pinfunction "1_1") (pintype "passive"))
      (node (ref "U1") (pin "B18") (pinfunction "IO_L20P_T3_A20_15_B18") (pintype "bidirectional"))
    )
    (net (code "164") (name "Net-(U1E-IO_L21N_T3_DQS_A18_15)") (class "Default")
      (node (ref "SV16") (pin "8") (pinfunction "8_8") (pintype "passive"))
      (node (ref "U1") (pin "B22") (pinfunction "IO_L21N_T3_DQS_A18_15_B22") (pintype "bidirectional"))
    )
    (net (code "165") (name "Net-(U1E-IO_L21P_T3_DQS_15)") (class "Default")
      (node (ref "SV16") (pin "9") (pinfunction "9_9") (pintype "passive"))
      (node (ref "U1") (pin "C22") (pinfunction "IO_L21P_T3_DQS_15_C22") (pintype "bidirectional"))
    )
    (net (code "166") (name "Net-(U1E-IO_L22N_T3_A16_15)") (class "Default")
      (node (ref "SV16") (pin "6") (pinfunction "6_6") (pintype "passive"))
      (node (ref "U1") (pin "A21") (pinfunction "IO_L22N_T3_A16_15_A21") (pintype "bidirectional"))
    )
    (net (code "167") (name "Net-(U1E-IO_L22P_T3_A17_15)") (class "Default")
      (node (ref "SV16") (pin "7") (pinfunction "7_7") (pintype "passive"))
      (node (ref "U1") (pin "A20") (pinfunction "IO_L22P_T3_A17_15_A20") (pintype "bidirectional"))
    )
    (net (code "168") (name "Net-(U1E-IO_L23N_T3_FWE_B_15)") (class "Default")
      (node (ref "SV16") (pin "4") (pinfunction "4_4") (pintype "passive"))
      (node (ref "U1") (pin "D22") (pinfunction "IO_L23N_T3_FWE_B_15_D22") (pintype "bidirectional"))
    )
    (net (code "169") (name "Net-(U1E-IO_L23P_T3_FOE_B_15)") (class "Default")
      (node (ref "SV16") (pin "5") (pinfunction "5_5") (pintype "passive"))
      (node (ref "U1") (pin "D21") (pinfunction "IO_L23P_T3_FOE_B_15_D21") (pintype "bidirectional"))
    )
    (net (code "170") (name "Net-(U1E-IO_L24N_T3_RS0_15)") (class "Default")
      (node (ref "SV16") (pin "2") (pinfunction "2_2") (pintype "passive"))
      (node (ref "U1") (pin "B21") (pinfunction "IO_L24N_T3_RS0_15_B21") (pintype "bidirectional"))
    )
    (net (code "171") (name "Net-(U1E-IO_L24P_T3_RS1_15)") (class "Default")
      (node (ref "SV16") (pin "3") (pinfunction "3_3") (pintype "passive"))
      (node (ref "U1") (pin "B20") (pinfunction "IO_L24P_T3_RS1_15_B20") (pintype "bidirectional"))
    )
    (net (code "172") (name "Net-(U1F-IO_6_T0_VREF_16)") (class "Default")
      (node (ref "SV17") (pin "8") (pinfunction "8_8") (pintype "passive"))
      (node (ref "U1") (pin "F14") (pinfunction "IO_6_T0_VREF_16_F14") (pintype "bidirectional"))
    )
    (net (code "173") (name "Net-(U1F-IO_18_T2_16)") (class "Default")
      (node (ref "SV17") (pin "10") (pinfunction "10_10") (pintype "passive"))
      (node (ref "U1") (pin "H10") (pinfunction "IO_18_T2_16_H10") (pintype "bidirectional"))
    )
    (net (code "174") (name "Net-(U1F-IO_24_T3_16)") (class "Default")
      (node (ref "SV17") (pin "9") (pinfunction "9_9") (pintype "passive"))
      (node (ref "U1") (pin "E8") (pinfunction "IO_24_T3_16_E8") (pintype "bidirectional"))
    )
    (net (code "175") (name "Net-(U1F-IO_L7N_T1_16)") (class "Default")
      (node (ref "SV17") (pin "6") (pinfunction "6_6") (pintype "passive"))
      (node (ref "U1") (pin "C10") (pinfunction "IO_L7N_T1_16_C10") (pintype "bidirectional"))
    )
    (net (code "176") (name "Net-(U1F-IO_L7P_T1_16)") (class "Default")
      (node (ref "SV17") (pin "7") (pinfunction "7_7") (pintype "passive"))
      (node (ref "U1") (pin "D10") (pinfunction "IO_L7P_T1_16_D10") (pintype "bidirectional"))
    )
    (net (code "177") (name "Net-(U1F-IO_L8N_T1_16)") (class "Default")
      (node (ref "SV17") (pin "4") (pinfunction "4_4") (pintype "passive"))
      (node (ref "U1") (pin "F13") (pinfunction "IO_L8N_T1_16_F13") (pintype "bidirectional"))
    )
    (net (code "178") (name "Net-(U1F-IO_L8P_T1_16)") (class "Default")
      (node (ref "SV17") (pin "5") (pinfunction "5_5") (pintype "passive"))
      (node (ref "U1") (pin "G13") (pinfunction "IO_L8P_T1_16_G13") (pintype "bidirectional"))
    )
    (net (code "179") (name "Net-(U1F-IO_L9N_T1_DQS_16)") (class "Default")
      (node (ref "SV17") (pin "2") (pinfunction "2_2") (pintype "passive"))
      (node (ref "U1") (pin "H13") (pinfunction "IO_L9N_T1_DQS_16_H13") (pintype "bidirectional"))
    )
    (net (code "180") (name "Net-(U1F-IO_L9P_T1_DQS_16)") (class "Default")
      (node (ref "SV17") (pin "3") (pinfunction "3_3") (pintype "passive"))
      (node (ref "U1") (pin "H14") (pinfunction "IO_L9P_T1_DQS_16_H14") (pintype "bidirectional"))
    )
    (net (code "181") (name "Net-(U1F-IO_L10N_T1_16)") (class "Default")
      (node (ref "SV18") (pin "10") (pinfunction "10_10") (pintype "passive"))
      (node (ref "U1") (pin "E12") (pinfunction "IO_L10N_T1_16_E12") (pintype "bidirectional"))
    )
    (net (code "182") (name "Net-(U1F-IO_L10P_T1_16)") (class "Default")
      (node (ref "SV17") (pin "1") (pinfunction "1_1") (pintype "passive"))
      (node (ref "U1") (pin "E13") (pinfunction "IO_L10P_T1_16_E13") (pintype "bidirectional"))
    )
    (net (code "183") (name "Net-(U1F-IO_L11N_T1_SRCC_16)") (class "Default")
      (node (ref "SV18") (pin "8") (pinfunction "8_8") (pintype "passive"))
      (node (ref "U1") (pin "F10") (pinfunction "IO_L11N_T1_SRCC_16_F10") (pintype "bidirectional"))
    )
    (net (code "184") (name "Net-(U1F-IO_L11P_T1_SRCC_16)") (class "Default")
      (node (ref "SV18") (pin "9") (pinfunction "9_9") (pintype "passive"))
      (node (ref "U1") (pin "F11") (pinfunction "IO_L11P_T1_SRCC_16_F11") (pintype "bidirectional"))
    )
    (net (code "185") (name "Net-(U1F-IO_L12N_T1_MRCC_16)") (class "Default")
      (node (ref "SV18") (pin "6") (pinfunction "6_6") (pintype "passive"))
      (node (ref "U1") (pin "D11") (pinfunction "IO_L12N_T1_MRCC_16_D11") (pintype "bidirectional"))
    )
    (net (code "186") (name "Net-(U1F-IO_L12P_T1_MRCC_16)") (class "Default")
      (node (ref "SV18") (pin "7") (pinfunction "7_7") (pintype "passive"))
      (node (ref "U1") (pin "E11") (pinfunction "IO_L12P_T1_MRCC_16_E11") (pintype "bidirectional"))
    )
    (net (code "187") (name "Net-(U1F-IO_L13N_T2_MRCC_16)") (class "Default")
      (node (ref "SV18") (pin "4") (pinfunction "4_4") (pintype "passive"))
      (node (ref "U1") (pin "G10") (pinfunction "IO_L13N_T2_MRCC_16_G10") (pintype "bidirectional"))
    )
    (net (code "188") (name "Net-(U1F-IO_L13P_T2_MRCC_16)") (class "Default")
      (node (ref "SV18") (pin "5") (pinfunction "5_5") (pintype "passive"))
      (node (ref "U1") (pin "G11") (pinfunction "IO_L13P_T2_MRCC_16_G11") (pintype "bidirectional"))
    )
    (net (code "189") (name "Net-(U1F-IO_L14N_T2_SRCC_16)") (class "Default")
      (node (ref "SV18") (pin "2") (pinfunction "2_2") (pintype "passive"))
      (node (ref "U1") (pin "G12") (pinfunction "IO_L14N_T2_SRCC_16_G12") (pintype "bidirectional"))
    )
    (net (code "190") (name "Net-(U1F-IO_L14P_T2_SRCC_16)") (class "Default")
      (node (ref "SV18") (pin "3") (pinfunction "3_3") (pintype "passive"))
      (node (ref "U1") (pin "H12") (pinfunction "IO_L14P_T2_SRCC_16_H12") (pintype "bidirectional"))
    )
    (net (code "191") (name "Net-(U1F-IO_L15N_T2_DQS_16)") (class "Default")
      (node (ref "SV19") (pin "10") (pinfunction "10_10") (pintype "passive"))
      (node (ref "U1") (pin "E9") (pinfunction "IO_L15N_T2_DQS_16_E9") (pintype "bidirectional"))
    )
    (net (code "192") (name "Net-(U1F-IO_L15P_T2_DQS_16)") (class "Default")
      (node (ref "SV18") (pin "1") (pinfunction "1_1") (pintype "passive"))
      (node (ref "U1") (pin "F9") (pinfunction "IO_L15P_T2_DQS_16_F9") (pintype "bidirectional"))
    )
    (net (code "193") (name "Net-(U1F-IO_L16N_T2_16)") (class "Default")
      (node (ref "SV19") (pin "8") (pinfunction "8_8") (pintype "passive"))
      (node (ref "U1") (pin "H8") (pinfunction "IO_L16N_T2_16_H8") (pintype "bidirectional"))
    )
    (net (code "194") (name "Net-(U1F-IO_L16P_T2_16)") (class "Default")
      (node (ref "SV19") (pin "9") (pinfunction "9_9") (pintype "passive"))
      (node (ref "U1") (pin "H9") (pinfunction "IO_L16P_T2_16_H9") (pintype "bidirectional"))
    )
    (net (code "195") (name "Net-(U1F-IO_L17N_T2_16)") (class "Default")
      (node (ref "SV19") (pin "6") (pinfunction "6_6") (pintype "passive"))
      (node (ref "U1") (pin "F8") (pinfunction "IO_L17N_T2_16_F8") (pintype "bidirectional"))
    )
    (net (code "196") (name "Net-(U1F-IO_L17P_T2_16)") (class "Default")
      (node (ref "SV19") (pin "7") (pinfunction "7_7") (pintype "passive"))
      (node (ref "U1") (pin "G8") (pinfunction "IO_L17P_T2_16_G8") (pintype "bidirectional"))
    )
    (net (code "197") (name "Net-(U1F-IO_L19N_T3_VREF_16)") (class "Default")
      (node (ref "SV19") (pin "4") (pinfunction "4_4") (pintype "passive"))
      (node (ref "U1") (pin "C9") (pinfunction "IO_L19N_T3_VREF_16_C9") (pintype "bidirectional"))
    )
    (net (code "198") (name "Net-(U1F-IO_L19P_T3_16)") (class "Default")
      (node (ref "SV19") (pin "5") (pinfunction "5_5") (pintype "passive"))
      (node (ref "U1") (pin "D9") (pinfunction "IO_L19P_T3_16_D9") (pintype "bidirectional"))
    )
    (net (code "199") (name "Net-(U1F-IO_L20N_T3_16)") (class "Default")
      (node (ref "SV19") (pin "2") (pinfunction "2_2") (pintype "passive"))
      (node (ref "U1") (pin "B10") (pinfunction "IO_L20N_T3_16_B10") (pintype "bidirectional"))
    )
    (net (code "200") (name "Net-(U1F-IO_L20P_T3_16)") (class "Default")
      (node (ref "SV19") (pin "3") (pinfunction "3_3") (pintype "passive"))
      (node (ref "U1") (pin "B11") (pinfunction "IO_L20P_T3_16_B11") (pintype "bidirectional"))
    )
    (net (code "201") (name "Net-(U1F-IO_L21N_T3_DQS_16)") (class "Default")
      (node (ref "SV20") (pin "5") (pinfunction "5_5") (pintype "passive"))
      (node (ref "U1") (pin "A8") (pinfunction "IO_L21N_T3_DQS_16_A8") (pintype "bidirectional"))
    )
    (net (code "202") (name "Net-(U1F-IO_L21P_T3_DQS_16)") (class "Default")
      (node (ref "SV19") (pin "1") (pinfunction "1_1") (pintype "passive"))
      (node (ref "U1") (pin "A9") (pinfunction "IO_L21P_T3_DQS_16_A9") (pintype "bidirectional"))
    )
    (net (code "203") (name "Net-(U1F-IO_L22N_T3_16)") (class "Default")
      (node (ref "SV20") (pin "3") (pinfunction "3_3") (pintype "passive"))
      (node (ref "U1") (pin "B8") (pinfunction "IO_L22N_T3_16_B8") (pintype "bidirectional"))
    )
    (net (code "204") (name "Net-(U1F-IO_L22P_T3_16)") (class "Default")
      (node (ref "SV20") (pin "4") (pinfunction "4_4") (pintype "passive"))
      (node (ref "U1") (pin "C8") (pinfunction "IO_L22P_T3_16_C8") (pintype "bidirectional"))
    )
    (net (code "205") (name "Net-(U1F-IO_L23N_T3_16)") (class "Default")
      (node (ref "SV20") (pin "1") (pinfunction "1_1") (pintype "passive"))
      (node (ref "U1") (pin "A10") (pinfunction "IO_L23N_T3_16_A10") (pintype "bidirectional"))
    )
    (net (code "206") (name "Net-(U1F-IO_L23P_T3_16)") (class "Default")
      (node (ref "SV20") (pin "2") (pinfunction "2_2") (pintype "passive"))
      (node (ref "U1") (pin "A11") (pinfunction "IO_L23P_T3_16_A11") (pintype "bidirectional"))
    )
    (net (code "207") (name "Net-(U1G-IO_0_VRN_33)") (class "Default")
      (node (ref "SV21") (pin "10") (pinfunction "10_10") (pintype "passive"))
      (node (ref "U1") (pin "T6") (pinfunction "IO_0_VRN_33_T6") (pintype "bidirectional"))
    )
    (net (code "208") (name "Net-(U1G-IO_25_VRP_33)") (class "Default")
      (node (ref "SV25") (pin "1") (pinfunction "1_1") (pintype "passive"))
      (node (ref "U1") (pin "T14") (pinfunction "IO_25_VRP_33_T14") (pintype "bidirectional"))
    )
    (net (code "209") (name "Net-(U1G-IO_L1N_T0_33)") (class "Default")
      (node (ref "SV21") (pin "8") (pinfunction "8_8") (pintype "passive"))
      (node (ref "U1") (pin "AB5") (pinfunction "IO_L1N_T0_33_AB5") (pintype "bidirectional"))
    )
    (net (code "210") (name "Net-(U1G-IO_L1P_T0_33)") (class "Default")
      (node (ref "SV21") (pin "9") (pinfunction "9_9") (pintype "passive"))
      (node (ref "U1") (pin "AA5") (pinfunction "IO_L1P_T0_33_AA5") (pintype "bidirectional"))
    )
    (net (code "211") (name "Net-(U1G-IO_L2N_T0_33)") (class "Default")
      (node (ref "SV21") (pin "6") (pinfunction "6_6") (pintype "passive"))
      (node (ref "U1") (pin "AB7") (pinfunction "IO_L2N_T0_33_AB7") (pintype "bidirectional"))
    )
    (net (code "212") (name "Net-(U1G-IO_L2P_T0_33)") (class "Default")
      (node (ref "SV21") (pin "7") (pinfunction "7_7") (pintype "passive"))
      (node (ref "U1") (pin "AB8") (pinfunction "IO_L2P_T0_33_AB8") (pintype "bidirectional"))
    )
    (net (code "213") (name "Net-(U1G-IO_L3N_T0_DQS_33)") (class "Default")
      (node (ref "SV21") (pin "4") (pinfunction "4_4") (pintype "passive"))
      (node (ref "U1") (pin "AB6") (pinfunction "IO_L3N_T0_DQS_33_AB6") (pintype "bidirectional"))
    )
    (net (code "214") (name "Net-(U1G-IO_L3P_T0_DQS_33)") (class "Default")
      (node (ref "SV21") (pin "5") (pinfunction "5_5") (pintype "passive"))
      (node (ref "U1") (pin "AA6") (pinfunction "IO_L3P_T0_DQS_33_AA6") (pintype "bidirectional"))
    )
    (net (code "215") (name "Net-(U1G-IO_L4N_T0_33)") (class "Default")
      (node (ref "SV21") (pin "2") (pinfunction "2_2") (pintype "passive"))
      (node (ref "U1") (pin "AB10") (pinfunction "IO_L4N_T0_33_AB10") (pintype "bidirectional"))
    )
    (net (code "216") (name "Net-(U1G-IO_L4P_T0_33)") (class "Default")
      (node (ref "SV21") (pin "3") (pinfunction "3_3") (pintype "passive"))
      (node (ref "U1") (pin "AA10") (pinfunction "IO_L4P_T0_33_AA10") (pintype "bidirectional"))
    )
    (net (code "217") (name "Net-(U1G-IO_L5N_T0_33)") (class "Default")
      (node (ref "SV22") (pin "10") (pinfunction "10_10") (pintype "passive"))
      (node (ref "U1") (pin "AA8") (pinfunction "IO_L5N_T0_33_AA8") (pintype "bidirectional"))
    )
    (net (code "218") (name "Net-(U1G-IO_L5P_T0_33)") (class "Default")
      (node (ref "SV21") (pin "1") (pinfunction "1_1") (pintype "passive"))
      (node (ref "U1") (pin "AA9") (pinfunction "IO_L5P_T0_33_AA9") (pintype "bidirectional"))
    )
    (net (code "219") (name "Net-(U1G-IO_L6N_T0_VREF_33)") (class "Default")
      (node (ref "SV22") (pin "8") (pinfunction "8_8") (pintype "passive"))
      (node (ref "U1") (pin "Y11") (pinfunction "IO_L6N_T0_VREF_33_Y11") (pintype "bidirectional"))
    )
    (net (code "220") (name "Net-(U1G-IO_L6P_T0_33)") (class "Default")
      (node (ref "SV22") (pin "9") (pinfunction "9_9") (pintype "passive"))
      (node (ref "U1") (pin "W11") (pinfunction "IO_L6P_T0_33_W11") (pintype "bidirectional"))
    )
    (net (code "221") (name "Net-(U1G-IO_L7N_T1_33)") (class "Default")
      (node (ref "SV22") (pin "6") (pinfunction "6_6") (pintype "passive"))
      (node (ref "U1") (pin "Y6") (pinfunction "IO_L7N_T1_33_Y6") (pintype "bidirectional"))
    )
    (net (code "222") (name "Net-(U1G-IO_L7P_T1_33)") (class "Default")
      (node (ref "SV22") (pin "7") (pinfunction "7_7") (pintype "passive"))
      (node (ref "U1") (pin "W6") (pinfunction "IO_L7P_T1_33_W6") (pintype "bidirectional"))
    )
    (net (code "223") (name "Net-(U1G-IO_L8N_T1_33)") (class "Default")
      (node (ref "SV22") (pin "4") (pinfunction "4_4") (pintype "passive"))
      (node (ref "U1") (pin "R6") (pinfunction "IO_L8N_T1_33_R6") (pintype "bidirectional"))
    )
    (net (code "224") (name "Net-(U1G-IO_L8P_T1_33)") (class "Default")
      (node (ref "SV22") (pin "5") (pinfunction "5_5") (pintype "passive"))
      (node (ref "U1") (pin "R7") (pinfunction "IO_L8P_T1_33_R7") (pintype "bidirectional"))
    )
    (net (code "225") (name "Net-(U1G-IO_L9N_T1_DQS_33)") (class "Default")
      (node (ref "SV22") (pin "2") (pinfunction "2_2") (pintype "passive"))
      (node (ref "U1") (pin "V8") (pinfunction "IO_L9N_T1_DQS_33_V8") (pintype "bidirectional"))
    )
    (net (code "226") (name "Net-(U1G-IO_L9P_T1_DQS_33)") (class "Default")
      (node (ref "SV22") (pin "3") (pinfunction "3_3") (pintype "passive"))
      (node (ref "U1") (pin "U8") (pinfunction "IO_L9P_T1_DQS_33_U8") (pintype "bidirectional"))
    )
    (net (code "227") (name "Net-(U1G-IO_L10N_T1_33)") (class "Default")
      (node (ref "SV23") (pin "10") (pinfunction "10_10") (pintype "passive"))
      (node (ref "U1") (pin "U6") (pinfunction "IO_L10N_T1_33_U6") (pintype "bidirectional"))
    )
    (net (code "228") (name "Net-(U1G-IO_L10P_T1_33)") (class "Default")
      (node (ref "SV22") (pin "1") (pinfunction "1_1") (pintype "passive"))
      (node (ref "U1") (pin "U7") (pinfunction "IO_L10P_T1_33_U7") (pintype "bidirectional"))
    )
    (net (code "229") (name "Net-(U1G-IO_L11N_T1_SRCC_33)") (class "Default")
      (node (ref "SV23") (pin "8") (pinfunction "8_8") (pintype "passive"))
      (node (ref "U1") (pin "W7") (pinfunction "IO_L11N_T1_SRCC_33_W7") (pintype "bidirectional"))
    )
    (net (code "230") (name "Net-(U1G-IO_L11P_T1_SRCC_33)") (class "Default")
      (node (ref "SV23") (pin "9") (pinfunction "9_9") (pintype "passive"))
      (node (ref "U1") (pin "V7") (pinfunction "IO_L11P_T1_SRCC_33_V7") (pintype "bidirectional"))
    )
    (net (code "231") (name "Net-(U1G-IO_L12N_T1_MRCC_33)") (class "Default")
      (node (ref "SV23") (pin "6") (pinfunction "6_6") (pintype "passive"))
      (node (ref "U1") (pin "Y7") (pinfunction "IO_L12N_T1_MRCC_33_Y7") (pintype "bidirectional"))
    )
    (net (code "232") (name "Net-(U1G-IO_L12P_T1_MRCC_33)") (class "Default")
      (node (ref "SV23") (pin "7") (pinfunction "7_7") (pintype "passive"))
      (node (ref "U1") (pin "Y8") (pinfunction "IO_L12P_T1_MRCC_33_Y8") (pintype "bidirectional"))
    )
    (net (code "233") (name "Net-(U1G-IO_L13N_T2_MRCC_33)") (class "Default")
      (node (ref "SV23") (pin "4") (pinfunction "4_4") (pintype "passive"))
      (node (ref "U1") (pin "Y9") (pinfunction "IO_L13N_T2_MRCC_33_Y9") (pintype "bidirectional"))
    )
    (net (code "234") (name "Net-(U1G-IO_L13P_T2_MRCC_33)") (class "Default")
      (node (ref "SV23") (pin "5") (pinfunction "5_5") (pintype "passive"))
      (node (ref "U1") (pin "W9") (pinfunction "IO_L13P_T2_MRCC_33_W9") (pintype "bidirectional"))
    )
    (net (code "235") (name "Net-(U1G-IO_L14N_T2_SRCC_33)") (class "Default")
      (node (ref "SV23") (pin "2") (pinfunction "2_2") (pintype "passive"))
      (node (ref "U1") (pin "V9") (pinfunction "IO_L14N_T2_SRCC_33_V9") (pintype "bidirectional"))
    )
    (net (code "236") (name "Net-(U1G-IO_L14P_T2_SRCC_33)") (class "Default")
      (node (ref "SV23") (pin "3") (pinfunction "3_3") (pintype "passive"))
      (node (ref "U1") (pin "U10") (pinfunction "IO_L14P_T2_SRCC_33_U10") (pintype "bidirectional"))
    )
    (net (code "237") (name "Net-(U1G-IO_L15N_T2_DQS_33)") (class "Default")
      (node (ref "SV24") (pin "10") (pinfunction "10_10") (pintype "passive"))
      (node (ref "U1") (pin "W10") (pinfunction "IO_L15N_T2_DQS_33_W10") (pintype "bidirectional"))
    )
    (net (code "238") (name "Net-(U1G-IO_L15P_T2_DQS_33)") (class "Default")
      (node (ref "SV23") (pin "1") (pinfunction "1_1") (pintype "passive"))
      (node (ref "U1") (pin "V10") (pinfunction "IO_L15P_T2_DQS_33_V10") (pintype "bidirectional"))
    )
    (net (code "239") (name "Net-(U1G-IO_L16N_T2_33)") (class "Default")
      (node (ref "SV24") (pin "8") (pinfunction "8_8") (pintype "passive"))
      (node (ref "U1") (pin "T10") (pinfunction "IO_L16N_T2_33_T10") (pintype "bidirectional"))
    )
    (net (code "240") (name "Net-(U1G-IO_L16P_T2_33)") (class "Default")
      (node (ref "SV24") (pin "9") (pinfunction "9_9") (pintype "passive"))
      (node (ref "U1") (pin "T11") (pinfunction "IO_L16P_T2_33_T11") (pintype "bidirectional"))
    )
    (net (code "241") (name "Net-(U1G-IO_L17N_T2_33)") (class "Default")
      (node (ref "SV24") (pin "6") (pinfunction "6_6") (pintype "passive"))
      (node (ref "U1") (pin "U11") (pinfunction "IO_L17N_T2_33_U11") (pintype "bidirectional"))
    )
    (net (code "242") (name "Net-(U1G-IO_L17P_T2_33)") (class "Default")
      (node (ref "SV24") (pin "7") (pinfunction "7_7") (pintype "passive"))
      (node (ref "U1") (pin "U12") (pinfunction "IO_L17P_T2_33_U12") (pintype "bidirectional"))
    )
    (net (code "243") (name "Net-(U1G-IO_L18N_T2_33)") (class "Default")
      (node (ref "SV24") (pin "4") (pinfunction "4_4") (pintype "passive"))
      (node (ref "U1") (pin "T8") (pinfunction "IO_L18N_T2_33_T8") (pintype "bidirectional"))
    )
    (net (code "244") (name "Net-(U1G-IO_L18P_T2_33)") (class "Default")
      (node (ref "SV24") (pin "5") (pinfunction "5_5") (pintype "passive"))
      (node (ref "U1") (pin "T9") (pinfunction "IO_L18P_T2_33_T9") (pintype "bidirectional"))
    )
    (net (code "245") (name "Net-(U1G-IO_L19N_T3_VREF_33)") (class "Default")
      (node (ref "SV24") (pin "2") (pinfunction "2_2") (pintype "passive"))
      (node (ref "U1") (pin "Y12") (pinfunction "IO_L19N_T3_VREF_33_Y12") (pintype "bidirectional"))
    )
    (net (code "246") (name "Net-(U1G-IO_L19P_T3_33)") (class "Default")
      (node (ref "SV24") (pin "3") (pinfunction "3_3") (pintype "passive"))
      (node (ref "U1") (pin "W12") (pinfunction "IO_L19P_T3_33_W12") (pintype "bidirectional"))
    )
    (net (code "247") (name "Net-(U1G-IO_L20N_T3_33)") (class "Default")
      (node (ref "SV25") (pin "10") (pinfunction "10_10") (pintype "passive"))
      (node (ref "U1") (pin "AB11") (pinfunction "IO_L20N_T3_33_AB11") (pintype "bidirectional"))
    )
    (net (code "248") (name "Net-(U1G-IO_L20P_T3_33)") (class "Default")
      (node (ref "SV24") (pin "1") (pinfunction "1_1") (pintype "passive"))
      (node (ref "U1") (pin "AA11") (pinfunction "IO_L20P_T3_33_AA11") (pintype "bidirectional"))
    )
    (net (code "249") (name "Net-(U1G-IO_L21N_T3_DQS_33)") (class "Default")
      (node (ref "SV25") (pin "8") (pinfunction "8_8") (pintype "passive"))
      (node (ref "U1") (pin "AA13") (pinfunction "IO_L21N_T3_DQS_33_AA13") (pintype "bidirectional"))
    )
    (net (code "250") (name "Net-(U1G-IO_L21P_T3_DQS_33)") (class "Default")
      (node (ref "SV25") (pin "9") (pinfunction "9_9") (pintype "passive"))
      (node (ref "U1") (pin "Y13") (pinfunction "IO_L21P_T3_DQS_33_Y13") (pintype "bidirectional"))
    )
    (net (code "251") (name "Net-(U1G-IO_L22N_T3_33)") (class "Default")
      (node (ref "SV25") (pin "6") (pinfunction "6_6") (pintype "passive"))
      (node (ref "U1") (pin "AB12") (pinfunction "IO_L22N_T3_33_AB12") (pintype "bidirectional"))
    )
    (net (code "252") (name "Net-(U1G-IO_L22P_T3_33)") (class "Default")
      (node (ref "SV25") (pin "7") (pinfunction "7_7") (pintype "passive"))
      (node (ref "U1") (pin "AB13") (pinfunction "IO_L22P_T3_33_AB13") (pintype "bidirectional"))
    )
    (net (code "253") (name "Net-(U1G-IO_L23N_T3_33)") (class "Default")
      (node (ref "SV25") (pin "4") (pinfunction "4_4") (pintype "passive"))
      (node (ref "U1") (pin "V12") (pinfunction "IO_L23N_T3_33_V12") (pintype "bidirectional"))
    )
    (net (code "254") (name "Net-(U1G-IO_L23P_T3_33)") (class "Default")
      (node (ref "SV25") (pin "5") (pinfunction "5_5") (pintype "passive"))
      (node (ref "U1") (pin "V13") (pinfunction "IO_L23P_T3_33_V13") (pintype "bidirectional"))
    )
    (net (code "255") (name "Net-(U1G-IO_L24N_T3_33)") (class "Default")
      (node (ref "SV25") (pin "2") (pinfunction "2_2") (pintype "passive"))
      (node (ref "U1") (pin "U13") (pinfunction "IO_L24N_T3_33_U13") (pintype "bidirectional"))
    )
    (net (code "256") (name "Net-(U1G-IO_L24P_T3_33)") (class "Default")
      (node (ref "SV25") (pin "3") (pinfunction "3_3") (pintype "passive"))
      (node (ref "U1") (pin "T13") (pinfunction "IO_L24P_T3_33_T13") (pintype "bidirectional"))
    )
    (net (code "257") (name "Net-(U1H-IO_0_VRN_34)") (class "Default")
      (node (ref "SV26") (pin "10") (pinfunction "10_10") (pintype "passive"))
      (node (ref "U1") (pin "K4") (pinfunction "IO_0_VRN_34_K4") (pintype "bidirectional"))
    )
    (net (code "258") (name "Net-(U1H-IO_25_VRP_34)") (class "Default")
      (node (ref "SV30") (pin "1") (pinfunction "1_1") (pintype "passive"))
      (node (ref "U1") (pin "V5") (pinfunction "IO_25_VRP_34_V5") (pintype "bidirectional"))
    )
    (net (code "259") (name "Net-(U1H-IO_L1N_T0_34)") (class "Default")
      (node (ref "SV26") (pin "8") (pinfunction "8_8") (pintype "passive"))
      (node (ref "U1") (pin "M3") (pinfunction "IO_L1N_T0_34_M3") (pintype "bidirectional"))
    )
    (net (code "260") (name "Net-(U1H-IO_L1P_T0_34)") (class "Default")
      (node (ref "SV26") (pin "9") (pinfunction "9_9") (pintype "passive"))
      (node (ref "U1") (pin "L3") (pinfunction "IO_L1P_T0_34_L3") (pintype "bidirectional"))
    )
    (net (code "261") (name "Net-(U1H-IO_L2N_T0_34)") (class "Default")
      (node (ref "SV26") (pin "6") (pinfunction "6_6") (pintype "passive"))
      (node (ref "U1") (pin "L1") (pinfunction "IO_L2N_T0_34_L1") (pintype "bidirectional"))
    )
    (net (code "262") (name "Net-(U1H-IO_L2P_T0_34)") (class "Default")
      (node (ref "SV26") (pin "7") (pinfunction "7_7") (pintype "passive"))
      (node (ref "U1") (pin "K1") (pinfunction "IO_L2P_T0_34_K1") (pintype "bidirectional"))
    )
    (net (code "263") (name "Net-(U1H-IO_L3N_T0_DQS_34)") (class "Default")
      (node (ref "SV26") (pin "4") (pinfunction "4_4") (pintype "passive"))
      (node (ref "U1") (pin "M1") (pinfunction "IO_L3N_T0_DQS_34_M1") (pintype "bidirectional"))
    )
    (net (code "264") (name "Net-(U1H-IO_L3P_T0_DQS_34)") (class "Default")
      (node (ref "SV26") (pin "5") (pinfunction "5_5") (pintype "passive"))
      (node (ref "U1") (pin "M2") (pinfunction "IO_L3P_T0_DQS_34_M2") (pintype "bidirectional"))
    )
    (net (code "265") (name "Net-(U1H-IO_L4N_T0_34)") (class "Default")
      (node (ref "SV26") (pin "2") (pinfunction "2_2") (pintype "passive"))
      (node (ref "U1") (pin "K2") (pinfunction "IO_L4N_T0_34_K2") (pintype "bidirectional"))
    )
    (net (code "266") (name "Net-(U1H-IO_L4P_T0_34)") (class "Default")
      (node (ref "SV26") (pin "3") (pinfunction "3_3") (pintype "passive"))
      (node (ref "U1") (pin "K3") (pinfunction "IO_L4P_T0_34_K3") (pintype "bidirectional"))
    )
    (net (code "267") (name "Net-(U1H-IO_L5N_T0_34)") (class "Default")
      (node (ref "SV27") (pin "10") (pinfunction "10_10") (pintype "passive"))
      (node (ref "U1") (pin "N2") (pinfunction "IO_L5N_T0_34_N2") (pintype "bidirectional"))
    )
    (net (code "268") (name "Net-(U1H-IO_L5P_T0_34)") (class "Default")
      (node (ref "SV26") (pin "1") (pinfunction "1_1") (pintype "passive"))
      (node (ref "U1") (pin "N3") (pinfunction "IO_L5P_T0_34_N3") (pintype "bidirectional"))
    )
    (net (code "269") (name "Net-(U1H-IO_L6N_T0_VREF_34)") (class "Default")
      (node (ref "SV27") (pin "8") (pinfunction "8_8") (pintype "passive"))
      (node (ref "U1") (pin "L4") (pinfunction "IO_L6N_T0_VREF_34_L4") (pintype "bidirectional"))
    )
    (net (code "270") (name "Net-(U1H-IO_L6P_T0_34)") (class "Default")
      (node (ref "SV27") (pin "9") (pinfunction "9_9") (pintype "passive"))
      (node (ref "U1") (pin "L5") (pinfunction "IO_L6P_T0_34_L5") (pintype "bidirectional"))
    )
    (net (code "271") (name "Net-(U1H-IO_L7N_T1_34)") (class "Default")
      (node (ref "SV27") (pin "6") (pinfunction "6_6") (pintype "passive"))
      (node (ref "U1") (pin "R2") (pinfunction "IO_L7N_T1_34_R2") (pintype "bidirectional"))
    )
    (net (code "272") (name "Net-(U1H-IO_L7P_T1_34)") (class "Default")
      (node (ref "SV27") (pin "7") (pinfunction "7_7") (pintype "passive"))
      (node (ref "U1") (pin "P2") (pinfunction "IO_L7P_T1_34_P2") (pintype "bidirectional"))
    )
    (net (code "273") (name "Net-(U1H-IO_L8N_T1_34)") (class "Default")
      (node (ref "SV27") (pin "4") (pinfunction "4_4") (pintype "passive"))
      (node (ref "U1") (pin "R1") (pinfunction "IO_L8N_T1_34_R1") (pintype "bidirectional"))
    )
    (net (code "274") (name "Net-(U1H-IO_L8P_T1_34)") (class "Default")
      (node (ref "SV27") (pin "5") (pinfunction "5_5") (pintype "passive"))
      (node (ref "U1") (pin "P1") (pinfunction "IO_L8P_T1_34_P1") (pintype "bidirectional"))
    )
    (net (code "275") (name "Net-(U1H-IO_L9N_T1_DQS_34)") (class "Default")
      (node (ref "SV27") (pin "2") (pinfunction "2_2") (pintype "passive"))
      (node (ref "U1") (pin "N4") (pinfunction "IO_L9N_T1_DQS_34_N4") (pintype "bidirectional"))
    )
    (net (code "276") (name "Net-(U1H-IO_L9P_T1_DQS_34)") (class "Default")
      (node (ref "SV27") (pin "3") (pinfunction "3_3") (pintype "passive"))
      (node (ref "U1") (pin "M5") (pinfunction "IO_L9P_T1_DQS_34_M5") (pintype "bidirectional"))
    )
    (net (code "277") (name "Net-(U1H-IO_L10N_T1_34)") (class "Default")
      (node (ref "SV28") (pin "10") (pinfunction "10_10") (pintype "passive"))
      (node (ref "U1") (pin "U1") (pinfunction "IO_L10N_T1_34_U1") (pintype "bidirectional"))
    )
    (net (code "278") (name "Net-(U1H-IO_L10P_T1_34)") (class "Default")
      (node (ref "SV27") (pin "1") (pinfunction "1_1") (pintype "passive"))
      (node (ref "U1") (pin "T1") (pinfunction "IO_L10P_T1_34_T1") (pintype "bidirectional"))
    )
    (net (code "279") (name "Net-(U1H-IO_L11N_T1_SRCC_34)") (class "Default")
      (node (ref "SV28") (pin "8") (pinfunction "8_8") (pintype "passive"))
      (node (ref "U1") (pin "R4") (pinfunction "IO_L11N_T1_SRCC_34_R4") (pintype "bidirectional"))
    )
    (net (code "280") (name "Net-(U1H-IO_L11P_T1_SRCC_34)") (class "Default")
      (node (ref "SV28") (pin "9") (pinfunction "9_9") (pintype "passive"))
      (node (ref "U1") (pin "P4") (pinfunction "IO_L11P_T1_SRCC_34_P4") (pintype "bidirectional"))
    )
    (net (code "281") (name "Net-(U1H-IO_L12N_T1_MRCC_34)") (class "Default")
      (node (ref "SV28") (pin "6") (pinfunction "6_6") (pintype "passive"))
      (node (ref "U1") (pin "T3") (pinfunction "IO_L12N_T1_MRCC_34_T3") (pintype "bidirectional"))
    )
    (net (code "282") (name "Net-(U1H-IO_L12P_T1_MRCC_34)") (class "Default")
      (node (ref "SV28") (pin "7") (pinfunction "7_7") (pintype "passive"))
      (node (ref "U1") (pin "R3") (pinfunction "IO_L12P_T1_MRCC_34_R3") (pintype "bidirectional"))
    )
    (net (code "283") (name "Net-(U1H-IO_L13N_T2_MRCC_34)") (class "Default")
      (node (ref "SV28") (pin "4") (pinfunction "4_4") (pintype "passive"))
      (node (ref "U1") (pin "U3") (pinfunction "IO_L13N_T2_MRCC_34_U3") (pintype "bidirectional"))
    )
    (net (code "284") (name "Net-(U1H-IO_L13P_T2_MRCC_34)") (class "Default")
      (node (ref "SV28") (pin "5") (pinfunction "5_5") (pintype "passive"))
      (node (ref "U1") (pin "T4") (pinfunction "IO_L13P_T2_MRCC_34_T4") (pintype "bidirectional"))
    )
    (net (code "285") (name "Net-(U1H-IO_L14N_T2_SRCC_34)") (class "Default")
      (node (ref "SV28") (pin "2") (pinfunction "2_2") (pintype "passive"))
      (node (ref "U1") (pin "W4") (pinfunction "IO_L14N_T2_SRCC_34_W4") (pintype "bidirectional"))
    )
    (net (code "286") (name "Net-(U1H-IO_L14P_T2_SRCC_34)") (class "Default")
      (node (ref "SV28") (pin "3") (pinfunction "3_3") (pintype "passive"))
      (node (ref "U1") (pin "V4") (pinfunction "IO_L14P_T2_SRCC_34_V4") (pintype "bidirectional"))
    )
    (net (code "287") (name "Net-(U1H-IO_L15N_T2_DQS_34)") (class "Default")
      (node (ref "SV29") (pin "10") (pinfunction "10_10") (pintype "passive"))
      (node (ref "U1") (pin "V2") (pinfunction "IO_L15N_T2_DQS_34_V2") (pintype "bidirectional"))
    )
    (net (code "288") (name "Net-(U1H-IO_L15P_T2_DQS_34)") (class "Default")
      (node (ref "SV28") (pin "1") (pinfunction "1_1") (pintype "passive"))
      (node (ref "U1") (pin "U2") (pinfunction "IO_L15P_T2_DQS_34_U2") (pintype "bidirectional"))
    )
    (net (code "289") (name "Net-(U1H-IO_L16N_T2_34)") (class "Default")
      (node (ref "SV29") (pin "8") (pinfunction "8_8") (pintype "passive"))
      (node (ref "U1") (pin "U5") (pinfunction "IO_L16N_T2_34_U5") (pintype "bidirectional"))
    )
    (net (code "290") (name "Net-(U1H-IO_L16P_T2_34)") (class "Default")
      (node (ref "SV29") (pin "9") (pinfunction "9_9") (pintype "passive"))
      (node (ref "U1") (pin "T5") (pinfunction "IO_L16P_T2_34_T5") (pintype "bidirectional"))
    )
    (net (code "291") (name "Net-(U1H-IO_L17N_T2_34)") (class "Default")
      (node (ref "SV29") (pin "6") (pinfunction "6_6") (pintype "passive"))
      (node (ref "U1") (pin "W2") (pinfunction "IO_L17N_T2_34_W2") (pintype "bidirectional"))
    )
    (net (code "292") (name "Net-(U1H-IO_L17P_T2_34)") (class "Default")
      (node (ref "SV29") (pin "7") (pinfunction "7_7") (pintype "passive"))
      (node (ref "U1") (pin "V3") (pinfunction "IO_L17P_T2_34_V3") (pintype "bidirectional"))
    )
    (net (code "293") (name "Net-(U1H-IO_L18N_T2_34)") (class "Default")
      (node (ref "SV29") (pin "4") (pinfunction "4_4") (pintype "passive"))
      (node (ref "U1") (pin "P5") (pinfunction "IO_L18N_T2_34_P5") (pintype "bidirectional"))
    )
    (net (code "294") (name "Net-(U1H-IO_L18P_T2_34)") (class "Default")
      (node (ref "SV29") (pin "5") (pinfunction "5_5") (pintype "passive"))
      (node (ref "U1") (pin "N5") (pinfunction "IO_L18P_T2_34_N5") (pintype "bidirectional"))
    )
    (net (code "295") (name "Net-(U1H-IO_L19N_T3_VREF_34)") (class "Default")
      (node (ref "SV29") (pin "2") (pinfunction "2_2") (pintype "passive"))
      (node (ref "U1") (pin "Y4") (pinfunction "IO_L19N_T3_VREF_34_Y4") (pintype "bidirectional"))
    )
    (net (code "296") (name "Net-(U1H-IO_L19P_T3_34)") (class "Default")
      (node (ref "SV29") (pin "3") (pinfunction "3_3") (pintype "passive"))
      (node (ref "U1") (pin "W5") (pinfunction "IO_L19P_T3_34_W5") (pintype "bidirectional"))
    )
    (net (code "297") (name "Net-(U1H-IO_L20N_T3_34)") (class "Default")
      (node (ref "SV30") (pin "10") (pinfunction "10_10") (pintype "passive"))
      (node (ref "U1") (pin "Y1") (pinfunction "IO_L20N_T3_34_Y1") (pintype "bidirectional"))
    )
    (net (code "298") (name "Net-(U1H-IO_L20P_T3_34)") (class "Default")
      (node (ref "SV29") (pin "1") (pinfunction "1_1") (pintype "passive"))
      (node (ref "U1") (pin "W1") (pinfunction "IO_L20P_T3_34_W1") (pintype "bidirectional"))
    )
    (net (code "299") (name "Net-(U1H-IO_L21N_T3_DQS_34)") (class "Default")
      (node (ref "SV30") (pin "8") (pinfunction "8_8") (pintype "passive"))
      (node (ref "U1") (pin "Y2") (pinfunction "IO_L21N_T3_DQS_34_Y2") (pintype "bidirectional"))
    )
    (net (code "300") (name "Net-(U1H-IO_L21P_T3_DQS_34)") (class "Default")
      (node (ref "SV30") (pin "9") (pinfunction "9_9") (pintype "passive"))
      (node (ref "U1") (pin "Y3") (pinfunction "IO_L21P_T3_DQS_34_Y3") (pintype "bidirectional"))
    )
    (net (code "301") (name "Net-(U1H-IO_L22N_T3_34)") (class "Default")
      (node (ref "SV30") (pin "6") (pinfunction "6_6") (pintype "passive"))
      (node (ref "U1") (pin "AB1") (pinfunction "IO_L22N_T3_34_AB1") (pintype "bidirectional"))
    )
    (net (code "302") (name "Net-(U1H-IO_L22P_T3_34)") (class "Default")
      (node (ref "SV30") (pin "7") (pinfunction "7_7") (pintype "passive"))
      (node (ref "U1") (pin "AA1") (pinfunction "IO_L22P_T3_34_AA1") (pintype "bidirectional"))
    )
    (net (code "303") (name "Net-(U1H-IO_L23N_T3_34)") (class "Default")
      (node (ref "SV30") (pin "4") (pinfunction "4_4") (pintype "passive"))
      (node (ref "U1") (pin "AB2") (pinfunction "IO_L23N_T3_34_AB2") (pintype "bidirectional"))
    )
    (net (code "304") (name "Net-(U1H-IO_L23P_T3_34)") (class "Default")
      (node (ref "SV30") (pin "5") (pinfunction "5_5") (pintype "passive"))
      (node (ref "U1") (pin "AA3") (pinfunction "IO_L23P_T3_34_AA3") (pintype "bidirectional"))
    )
    (net (code "305") (name "Net-(U1H-IO_L24N_T3_34)") (class "Default")
      (node (ref "SV30") (pin "2") (pinfunction "2_2") (pintype "passive"))
      (node (ref "U1") (pin "AB3") (pinfunction "IO_L24N_T3_34_AB3") (pintype "bidirectional"))
    )
    (net (code "306") (name "Net-(U1H-IO_L24P_T3_34)") (class "Default")
      (node (ref "SV30") (pin "3") (pinfunction "3_3") (pintype "passive"))
      (node (ref "U1") (pin "AA4") (pinfunction "IO_L24P_T3_34_AA4") (pintype "bidirectional"))
    )
    (net (code "307") (name "Net-(U3-B)") (class "Default")
      (node (ref "C49") (pin "1") (pinfunction "1_1") (pintype "passive"))
      (node (ref "SW1") (pin "3") (pinfunction "3_3") (pintype "output"))
      (node (ref "SW1") (pin "6") (pinfunction "6_6") (pintype "output"))
      (node (ref "U3") (pin "P$1") (pinfunction "B_P$1") (pintype "bidirectional"))
    )
    (net (code "308") (name "Net-(U6-MODE)") (class "Default")
      (node (ref "R15") (pin "2") (pinfunction "2_2") (pintype "passive"))
      (node (ref "U6") (pin "20") (pinfunction "MODE_20") (pintype "input"))
    )
    (net (code "309") (name "Net-(U6-TRIP)") (class "Default")
      (node (ref "R16") (pin "2") (pinfunction "2_2") (pintype "passive"))
      (node (ref "U6") (pin "21") (pinfunction "TRIP_21") (pintype "input"))
    )
    (net (code "310") (name "Net-(U6-VREG)") (class "Default")
      (node (ref "C59") (pin "1") (pinfunction "1_1") (pintype "passive"))
      (node (ref "U6") (pin "18") (pinfunction "VREG_18") (pintype "power_in"))
    )
    (net (code "311") (name "RXN_0") (class "Default")
      (node (ref "SV2") (pin "6") (pinfunction "6_6") (pintype "passive"))
      (node (ref "U1") (pin "G3") (pinfunction "MGTXRXN0_115_G3") (pintype "input"))
    )
    (net (code "312") (name "RXN_1") (class "Default")
      (node (ref "SV2") (pin "10") (pinfunction "10_10") (pintype "passive"))
      (node (ref "U1") (pin "E3") (pinfunction "MGTXRXN1_115_E3") (pintype "input"))
    )
    (net (code "313") (name "RXN_2") (class "Default")
      (node (ref "SV2") (pin "14") (pinfunction "14_14") (pintype "passive"))
      (node (ref "U1") (pin "C3") (pinfunction "MGTXRXN2_115_C3") (pintype "input"))
    )
    (net (code "314") (name "RXN_3") (class "Default")
      (node (ref "SV2") (pin "18") (pinfunction "18_18") (pintype "passive"))
      (node (ref "U1") (pin "B5") (pinfunction "MGTXRXN3_115_B5") (pintype "input"))
    )
    (net (code "315") (name "RXP_0") (class "Default")
      (node (ref "SV2") (pin "5") (pinfunction "5_5") (pintype "passive"))
      (node (ref "U1") (pin "G4") (pinfunction "MGTXRXP0_115_G4") (pintype "input"))
    )
    (net (code "316") (name "RXP_1") (class "Default")
      (node (ref "SV2") (pin "9") (pinfunction "9_9") (pintype "passive"))
      (node (ref "U1") (pin "E4") (pinfunction "MGTXRXP1_115_E4") (pintype "input"))
    )
    (net (code "317") (name "RXP_2") (class "Default")
      (node (ref "SV2") (pin "13") (pinfunction "13_13") (pintype "passive"))
      (node (ref "U1") (pin "C4") (pinfunction "MGTXRXP2_115_C4") (pintype "input"))
    )
    (net (code "318") (name "RXP_3") (class "Default")
      (node (ref "SV2") (pin "17") (pinfunction "17_17") (pintype "passive"))
      (node (ref "U1") (pin "B6") (pinfunction "MGTXRXP3_115_B6") (pintype "input"))
    )
    (net (code "319") (name "SYSCLK_N") (class "Default")
      (node (ref "R17") (pin "2") (pinfunction "2_2") (pintype "passive"))
      (node (ref "U1") (pin "F5") (pinfunction "MGTREFCLK1N_115_F5") (pintype "input"))
      (node (ref "U5") (pin "P$5") (pinfunction "OUT_B_P$5") (pintype "output"))
    )
    (net (code "320") (name "SYSCLK_P") (class "Default")
      (node (ref "R17") (pin "1") (pinfunction "1_1") (pintype "passive"))
      (node (ref "U1") (pin "F6") (pinfunction "MGTREFCLK1P_115_F6") (pintype "input"))
      (node (ref "U5") (pin "P$4") (pinfunction "OUT_P$4") (pintype "output"))
    )
    (net (code "321") (name "TXN_0") (class "Default")
      (node (ref "SV2") (pin "8") (pinfunction "8_8") (pintype "passive"))
      (node (ref "U1") (pin "F1") (pinfunction "MGTXTXN0_115_F1") (pintype "output"))
    )
    (net (code "322") (name "TXN_1") (class "Default")
      (node (ref "SV2") (pin "12") (pinfunction "12_12") (pintype "passive"))
      (node (ref "U1") (pin "D1") (pinfunction "MGTXTXN1_115_D1") (pintype "output"))
    )
    (net (code "323") (name "TXN_2") (class "Default")
      (node (ref "SV2") (pin "16") (pinfunction "16_16") (pintype "passive"))
      (node (ref "U1") (pin "B1") (pinfunction "MGTXTXN2_115_B1") (pintype "output"))
    )
    (net (code "324") (name "TXN_3") (class "Default")
      (node (ref "SV2") (pin "20") (pinfunction "20_20") (pintype "passive"))
      (node (ref "U1") (pin "A3") (pinfunction "MGTXTXN3_115_A3") (pintype "output"))
    )
    (net (code "325") (name "TXP_0") (class "Default")
      (node (ref "SV2") (pin "7") (pinfunction "7_7") (pintype "passive"))
      (node (ref "U1") (pin "F2") (pinfunction "MGTXTXP0_115_F2") (pintype "output"))
    )
    (net (code "326") (name "TXP_1") (class "Default")
      (node (ref "SV2") (pin "11") (pinfunction "11_11") (pintype "passive"))
      (node (ref "U1") (pin "D2") (pinfunction "MGTXTXP1_115_D2") (pintype "output"))
    )
    (net (code "327") (name "TXP_2") (class "Default")
      (node (ref "SV2") (pin "15") (pinfunction "15_15") (pintype "passive"))
      (node (ref "U1") (pin "B2") (pinfunction "MGTXTXP2_115_B2") (pintype "output"))
    )
    (net (code "328") (name "TXP_3") (class "Default")
      (node (ref "SV2") (pin "19") (pinfunction "19_19") (pintype "passive"))
      (node (ref "U1") (pin "A4") (pinfunction "MGTXTXP3_115_A4") (pintype "output"))
    )
    (net (code "329") (name "VCC1V8_FPGA") (class "Default")
      (node (ref "C45") (pin "1") (pinfunction "1_1") (pintype "passive"))
      (node (ref "C46") (pin "1") (pinfunction "1_1") (pintype "passive"))
      (node (ref "C53") (pin "+") (pinfunction "+_+") (pintype "passive"))
      (node (ref "U1") (pin "AA7") (pinfunction "VCCO_33_AA7") (pintype "input"))
      (node (ref "U1") (pin "AB4") (pinfunction "VCCO_34_AB4") (pintype "input"))
      (node (ref "U1") (pin "M4") (pinfunction "VCCO_34_M4") (pintype "input"))
      (node (ref "U1") (pin "N1") (pinfunction "VCCO_34_N1") (pintype "input"))
      (node (ref "U1") (pin "R5") (pinfunction "VCCO_34_R5") (pintype "input"))
      (node (ref "U1") (pin "T12") (pinfunction "VCCO_33_T12") (pintype "input"))
      (node (ref "U1") (pin "T2") (pinfunction "VCCO_34_T2") (pintype "input"))
      (node (ref "U1") (pin "U9") (pinfunction "VCCO_33_U9") (pintype "input"))
      (node (ref "U1") (pin "V6") (pinfunction "VCCO_33_V6") (pintype "input"))
      (node (ref "U1") (pin "W13") (pinfunction "VCCO_33_W13") (pintype "input"))
      (node (ref "U1") (pin "W3") (pinfunction "VCCO_34_W3") (pintype "input"))
      (node (ref "U1") (pin "Y10") (pinfunction "VCCO_33_Y10") (pintype "input"))
      (node (ref "U8") (pin "2") (pinfunction "VOUT_2") (pintype "output"))
    )
    (net (code "330") (name "VCC2V5_FPGA") (class "Default")
      (node (ref "C3") (pin "1") (pinfunction "1_1") (pintype "passive"))
      (node (ref "C4") (pin "1") (pinfunction "1_1") (pintype "passive"))
      (node (ref "C47") (pin "1") (pinfunction "1_1") (pintype "passive"))
      (node (ref "C5") (pin "1") (pinfunction "1_1") (pintype "passive"))
      (node (ref "C51") (pin "+") (pinfunction "+_+") (pintype "passive"))
      (node (ref "C6") (pin "1") (pinfunction "1_1") (pintype "passive"))
      (node (ref "C7") (pin "1") (pinfunction "1_1") (pintype "passive"))
      (node (ref "R14") (pin "2") (pinfunction "2_2") (pintype "passive"))
      (node (ref "R20") (pin "2") (pinfunction "2_2") (pintype "passive"))
      (node (ref "R23") (pin "2") (pinfunction "2_2") (pintype "passive"))
      (node (ref "U1") (pin "A17") (pinfunction "VCCO_15_A17") (pintype "input"))
      (node (ref "U1") (pin "AA17") (pinfunction "VCCO_13_AA17") (pintype "input"))
      (node (ref "U1") (pin "AB14") (pinfunction "VCCO_13_AB14") (pintype "input"))
      (node (ref "U1") (pin "B14") (pinfunction "VCCO_15_B14") (pintype "input"))
      (node (ref "U1") (pin "C11") (pinfunction "VCCO_16_C11") (pintype "input"))
      (node (ref "U1") (pin "C21") (pinfunction "VCCO_15_C21") (pintype "input"))
      (node (ref "U1") (pin "D18") (pinfunction "VCCO_15_D18") (pintype "input"))
      (node (ref "U1") (pin "D8") (pinfunction "VCCO_16_D8") (pintype "input"))
      (node (ref "U1") (pin "E15") (pinfunction "VCCO_15_E15") (pintype "input"))
      (node (ref "U1") (pin "F12") (pinfunction "VCCO_16_F12") (pintype "input"))
      (node (ref "U1") (pin "F22") (pinfunction "VCCO_14_F22") (pintype "input"))
      (node (ref "U1") (pin "G19") (pinfunction "VCCO_14_G19") (pintype "input"))
      (node (ref "U1") (pin "G9") (pinfunction "VCCO_16_G9") (pintype "input"))
      (node (ref "U1") (pin "H16") (pinfunction "VCCO_15_H16") (pintype "input"))
      (node (ref "U1") (pin "H7") (pinfunction "M0_0_H7") (pintype "input"))
      (node (ref "U1") (pin "J5") (pinfunction "M2_0_J5") (pintype "input"))
      (node (ref "U1") (pin "K20") (pinfunction "VCCO_14_K20") (pintype "input"))
      (node (ref "U1") (pin "L17") (pinfunction "VCCO_14_L17") (pintype "input"))
      (node (ref "U1") (pin "M7") (pinfunction "CFGBVS_0_M7") (pintype "input"))
      (node (ref "U1") (pin "N21") (pinfunction "VCCO_14_N21") (pintype "input"))
      (node (ref "U1") (pin "P18") (pinfunction "VCCO_14_P18") (pintype "input"))
      (node (ref "U1") (pin "T22") (pinfunction "VCCO_13_T22") (pintype "input"))
      (node (ref "U1") (pin "U19") (pinfunction "VCCO_13_U19") (pintype "input"))
      (node (ref "U1") (pin "V16") (pinfunction "VCCO_13_V16") (pintype "input"))
      (node (ref "U1") (pin "Y20") (pinfunction "VCCO_13_Y20") (pintype "input"))
      (node (ref "U5") (pin "P$1") (pinfunction "OE_P$1") (pintype "input"))
      (node (ref "U5") (pin "P$6") (pinfunction "VCC_P$6") (pintype "power_in"))
      (node (ref "U7") (pin "2") (pinfunction "VOUT_2") (pintype "output"))
    )
    (net (code "332") (name "VCC5V0") (class "Default")
      (node (ref "C38") (pin "+") (pinfunction "+_+") (pintype "passive"))
      (node (ref "C54") (pin "1") (pinfunction "1_1") (pintype "passive"))
      (node (ref "U4") (pin "2") (pinfunction "VOUT_2") (pintype "output"))
      (node (ref "U6") (pin "19") (pinfunction "VDD_19") (pintype "power_in"))
    )
    (net (code "333") (name "VCC12_P") (class "Default")
      (node (ref "C37") (pin "+") (pinfunction "+_+") (pintype "passive"))
      (node (ref "C48") (pin "+") (pinfunction "+_+") (pintype "passive"))
      (node (ref "C50") (pin "+") (pinfunction "+_+") (pintype "passive"))
      (node (ref "C52") (pin "+") (pinfunction "+_+") (pintype "passive"))
      (node (ref "C55") (pin "1") (pinfunction "1_1") (pintype "passive"))
      (node (ref "C56") (pin "1") (pinfunction "1_1") (pintype "passive"))
      (node (ref "C57") (pin "1") (pinfunction "1_1") (pintype "passive"))
      (node (ref "C58") (pin "1") (pinfunction "1_1") (pintype "passive"))
      (node (ref "R18") (pin "2") (pinfunction "2_2") (pintype "passive"))
      (node (ref "U3") (pin "P$2") (pinfunction "CB_P$2") (pintype "bidirectional"))
      (node (ref "U4") (pin "3") (pinfunction "VIN_3") (pintype "input"))
      (node (ref "U6") (pin "12") (pinfunction "VIN_2_12") (pintype "input"))
      (node (ref "U6") (pin "13") (pinfunction "VIN_3_13") (pintype "input"))
      (node (ref "U6") (pin "14") (pinfunction "VIN_4_14") (pintype "input"))
      (node (ref "U6") (pin "15") (pinfunction "VIN_5_15") (pintype "input"))
      (node (ref "U6") (pin "16") (pinfunction "VIN_6_16") (pintype "input"))
      (node (ref "U6") (pin "17") (pinfunction "VIN_17") (pintype "input"))
      (node (ref "U7") (pin "3") (pinfunction "VIN_3") (pintype "input"))
      (node (ref "U8") (pin "3") (pinfunction "VIN_3") (pintype "input"))
    )
    (net (code "334") (name "VCC12_P_IN") (class "Default")
      (node (ref "J2") (pin "P$1") (pinfunction "12V_P$1") (pintype "power_in"))
      (node (ref "J2") (pin "P$4") (pinfunction "12V__P$4") (pintype "power_in"))
      (node (ref "SW1") (pin "2") (pinfunction "2_2") (pintype "input"))
      (node (ref "SW1") (pin "5") (pinfunction "5_5") (pintype "input"))
    )
    (net (code "335") (name "VCCAUX") (class "Default")
      (node (ref "C40") (pin "1") (pinfunction "1_1") (pintype "passive"))
      (node (ref "C41") (pin "1") (pinfunction "1_1") (pintype "passive"))
      (node (ref "C42") (pin "1") (pinfunction "1_1") (pintype "passive"))
      (node (ref "C43") (pin "1") (pinfunction "1_1") (pintype "passive"))
      (node (ref "C44") (pin "1") (pinfunction "1_1") (pintype "passive"))
    )
    (net (code "336") (name "VCCBRAM") (class "Default")
      (node (ref "C10") (pin "1") (pinfunction "1_1") (pintype "passive"))
      (node (ref "C39") (pin "1") (pinfunction "1_1") (pintype "passive"))
      (node (ref "C8") (pin "1") (pinfunction "1_1") (pintype "passive"))
      (node (ref "C9") (pin "1") (pinfunction "1_1") (pintype "passive"))
    )
    (net (code "337") (name "VCCINT_FPGA") (class "Default")
      (node (ref "C2") (pin "+") (pinfunction "+_+") (pintype "passive"))
    )
    (net (code "338") (name "unconnected-(C1-Pad+)") (class "Default")
      (node (ref "C1") (pin "+") (pinfunction "+_+") (pintype "passive"))
    )
    (net (code "339") (name "unconnected-(C1-Pad-)") (class "Default")
      (node (ref "C1") (pin "-") (pinfunction "-_-") (pintype "passive"))
    )
    (net (code "340") (name "unconnected-(C11-Pad1)") (class "Default")
      (node (ref "C11") (pin "1") (pinfunction "1_1") (pintype "passive"))
    )
    (net (code "341") (name "unconnected-(C11-Pad2)") (class "Default")
      (node (ref "C11") (pin "2") (pinfunction "2_2") (pintype "passive"))
    )
    (net (code "342") (name "unconnected-(C12-Pad1)") (class "Default")
      (node (ref "C12") (pin "1") (pinfunction "1_1") (pintype "passive"))
    )
    (net (code "343") (name "unconnected-(C12-Pad2)") (class "Default")
      (node (ref "C12") (pin "2") (pinfunction "2_2") (pintype "passive"))
    )
    (net (code "344") (name "unconnected-(C13-Pad1)") (class "Default")
      (node (ref "C13") (pin "1") (pinfunction "1_1") (pintype "passive"))
    )
    (net (code "345") (name "unconnected-(C13-Pad2)") (class "Default")
      (node (ref "C13") (pin "2") (pinfunction "2_2") (pintype "passive"))
    )
    (net (code "346") (name "unconnected-(C14-Pad1)") (class "Default")
      (node (ref "C14") (pin "1") (pinfunction "1_1") (pintype "passive"))
    )
    (net (code "347") (name "unconnected-(C14-Pad2)") (class "Default")
      (node (ref "C14") (pin "2") (pinfunction "2_2") (pintype "passive"))
    )
    (net (code "348") (name "unconnected-(C15-Pad1)") (class "Default")
      (node (ref "C15") (pin "1") (pinfunction "1_1") (pintype "passive"))
    )
    (net (code "349") (name "unconnected-(C15-Pad2)") (class "Default")
      (node (ref "C15") (pin "2") (pinfunction "2_2") (pintype "passive"))
    )
    (net (code "350") (name "unconnected-(C16-Pad1)") (class "Default")
      (node (ref "C16") (pin "1") (pinfunction "1_1") (pintype "passive"))
    )
    (net (code "351") (name "unconnected-(C16-Pad2)") (class "Default")
      (node (ref "C16") (pin "2") (pinfunction "2_2") (pintype "passive"))
    )
    (net (code "352") (name "unconnected-(C17-Pad1)") (class "Default")
      (node (ref "C17") (pin "1") (pinfunction "1_1") (pintype "passive"))
    )
    (net (code "353") (name "unconnected-(C17-Pad2)") (class "Default")
      (node (ref "C17") (pin "2") (pinfunction "2_2") (pintype "passive"))
    )
    (net (code "354") (name "unconnected-(C18-Pad1)") (class "Default")
      (node (ref "C18") (pin "1") (pinfunction "1_1") (pintype "passive"))
    )
    (net (code "355") (name "unconnected-(C18-Pad2)") (class "Default")
      (node (ref "C18") (pin "2") (pinfunction "2_2") (pintype "passive"))
    )
    (net (code "356") (name "unconnected-(C19-Pad1)") (class "Default")
      (node (ref "C19") (pin "1") (pinfunction "1_1") (pintype "passive"))
    )
    (net (code "357") (name "unconnected-(C19-Pad2)") (class "Default")
      (node (ref "C19") (pin "2") (pinfunction "2_2") (pintype "passive"))
    )
    (net (code "358") (name "unconnected-(C20-Pad1)") (class "Default")
      (node (ref "C20") (pin "1") (pinfunction "1_1") (pintype "passive"))
    )
    (net (code "359") (name "unconnected-(C20-Pad2)") (class "Default")
      (node (ref "C20") (pin "2") (pinfunction "2_2") (pintype "passive"))
    )
    (net (code "360") (name "unconnected-(C21-Pad1)") (class "Default")
      (node (ref "C21") (pin "1") (pinfunction "1_1") (pintype "passive"))
    )
    (net (code "361") (name "unconnected-(C21-Pad2)") (class "Default")
      (node (ref "C21") (pin "2") (pinfunction "2_2") (pintype "passive"))
    )
    (net (code "362") (name "unconnected-(C22-Pad1)") (class "Default")
      (node (ref "C22") (pin "1") (pinfunction "1_1") (pintype "passive"))
    )
    (net (code "363") (name "unconnected-(C22-Pad2)") (class "Default")
      (node (ref "C22") (pin "2") (pinfunction "2_2") (pintype "passive"))
    )
    (net (code "364") (name "unconnected-(C23-Pad1)") (class "Default")
      (node (ref "C23") (pin "1") (pinfunction "1_1") (pintype "passive"))
    )
    (net (code "365") (name "unconnected-(C23-Pad2)") (class "Default")
      (node (ref "C23") (pin "2") (pinfunction "2_2") (pintype "passive"))
    )
    (net (code "366") (name "unconnected-(C24-Pad1)") (class "Default")
      (node (ref "C24") (pin "1") (pinfunction "1_1") (pintype "passive"))
    )
    (net (code "367") (name "unconnected-(C24-Pad2)") (class "Default")
      (node (ref "C24") (pin "2") (pinfunction "2_2") (pintype "passive"))
    )
    (net (code "368") (name "unconnected-(C25-Pad1)") (class "Default")
      (node (ref "C25") (pin "1") (pinfunction "1_1") (pintype "passive"))
    )
    (net (code "369") (name "unconnected-(C25-Pad2)") (class "Default")
      (node (ref "C25") (pin "2") (pinfunction "2_2") (pintype "passive"))
    )
    (net (code "370") (name "unconnected-(C26-Pad1)") (class "Default")
      (node (ref "C26") (pin "1") (pinfunction "1_1") (pintype "passive"))
    )
    (net (code "371") (name "unconnected-(C26-Pad2)") (class "Default")
      (node (ref "C26") (pin "2") (pinfunction "2_2") (pintype "passive"))
    )
    (net (code "372") (name "unconnected-(C27-Pad1)") (class "Default")
      (node (ref "C27") (pin "1") (pinfunction "1_1") (pintype "passive"))
    )
    (net (code "373") (name "unconnected-(C27-Pad2)") (class "Default")
      (node (ref "C27") (pin "2") (pinfunction "2_2") (pintype "passive"))
    )
    (net (code "374") (name "unconnected-(C28-Pad1)") (class "Default")
      (node (ref "C28") (pin "1") (pinfunction "1_1") (pintype "passive"))
    )
    (net (code "375") (name "unconnected-(C28-Pad2)") (class "Default")
      (node (ref "C28") (pin "2") (pinfunction "2_2") (pintype "passive"))
    )
    (net (code "376") (name "unconnected-(C29-Pad1)") (class "Default")
      (node (ref "C29") (pin "1") (pinfunction "1_1") (pintype "passive"))
    )
    (net (code "377") (name "unconnected-(C29-Pad2)") (class "Default")
      (node (ref "C29") (pin "2") (pinfunction "2_2") (pintype "passive"))
    )
    (net (code "378") (name "unconnected-(C30-Pad1)") (class "Default")
      (node (ref "C30") (pin "1") (pinfunction "1_1") (pintype "passive"))
    )
    (net (code "379") (name "unconnected-(C30-Pad2)") (class "Default")
      (node (ref "C30") (pin "2") (pinfunction "2_2") (pintype "passive"))
    )
    (net (code "380") (name "unconnected-(C31-Pad1)") (class "Default")
      (node (ref "C31") (pin "1") (pinfunction "1_1") (pintype "passive"))
    )
    (net (code "381") (name "unconnected-(C31-Pad2)") (class "Default")
      (node (ref "C31") (pin "2") (pinfunction "2_2") (pintype "passive"))
    )
    (net (code "382") (name "unconnected-(C32-Pad1)") (class "Default")
      (node (ref "C32") (pin "1") (pinfunction "1_1") (pintype "passive"))
    )
    (net (code "383") (name "unconnected-(C32-Pad2)") (class "Default")
      (node (ref "C32") (pin "2") (pinfunction "2_2") (pintype "passive"))
    )
    (net (code "384") (name "unconnected-(C33-Pad1)") (class "Default")
      (node (ref "C33") (pin "1") (pinfunction "1_1") (pintype "passive"))
    )
    (net (code "385") (name "unconnected-(C33-Pad2)") (class "Default")
      (node (ref "C33") (pin "2") (pinfunction "2_2") (pintype "passive"))
    )
    (net (code "386") (name "unconnected-(C34-Pad1)") (class "Default")
      (node (ref "C34") (pin "1") (pinfunction "1_1") (pintype "passive"))
    )
    (net (code "387") (name "unconnected-(C34-Pad2)") (class "Default")
      (node (ref "C34") (pin "2") (pinfunction "2_2") (pintype "passive"))
    )
    (net (code "388") (name "unconnected-(DZ1A-A-Pad1)") (class "Default")
      (node (ref "DZ1") (pin "1") (pinfunction "A_1") (pintype "passive"))
    )
    (net (code "389") (name "unconnected-(DZ1A-C-Pad20)") (class "Default")
      (node (ref "DZ1") (pin "20") (pinfunction "C_20") (pintype "passive"))
    )
    (net (code "390") (name "unconnected-(DZ1B-A-Pad10)") (class "Default")
      (node (ref "DZ1") (pin "10") (pinfunction "A_10") (pintype "passive"))
    )
    (net (code "391") (name "unconnected-(DZ1B-C-Pad11)") (class "Default")
      (node (ref "DZ1") (pin "11") (pinfunction "C_11") (pintype "passive"))
    )
    (net (code "392") (name "unconnected-(DZ1C-A-Pad2)") (class "Default")
      (node (ref "DZ1") (pin "2") (pinfunction "A_2") (pintype "passive"))
    )
    (net (code "393") (name "unconnected-(DZ1C-C-Pad19)") (class "Default")
      (node (ref "DZ1") (pin "19") (pinfunction "C_19") (pintype "passive"))
    )
    (net (code "394") (name "unconnected-(DZ1D-A-Pad3)") (class "Default")
      (node (ref "DZ1") (pin "3") (pinfunction "A_3") (pintype "passive"))
    )
    (net (code "395") (name "unconnected-(DZ1D-C-Pad18)") (class "Default")
      (node (ref "DZ1") (pin "18") (pinfunction "C_18") (pintype "passive"))
    )
    (net (code "396") (name "unconnected-(DZ1E-A-Pad4)") (class "Default")
      (node (ref "DZ1") (pin "4") (pinfunction "A_4") (pintype "passive"))
    )
    (net (code "397") (name "unconnected-(DZ1E-C-Pad17)") (class "Default")
      (node (ref "DZ1") (pin "17") (pinfunction "C_17") (pintype "passive"))
    )
    (net (code "398") (name "unconnected-(DZ1F-A-Pad5)") (class "Default")
      (node (ref "DZ1") (pin "5") (pinfunction "A_5") (pintype "passive"))
    )
    (net (code "399") (name "unconnected-(DZ1F-C-Pad16)") (class "Default")
      (node (ref "DZ1") (pin "16") (pinfunction "C_16") (pintype "passive"))
    )
    (net (code "400") (name "unconnected-(DZ1G-A-Pad6)") (class "Default")
      (node (ref "DZ1") (pin "6") (pinfunction "A_6") (pintype "passive"))
    )
    (net (code "401") (name "unconnected-(DZ1G-C-Pad15)") (class "Default")
      (node (ref "DZ1") (pin "15") (pinfunction "C_15") (pintype "passive"))
    )
    (net (code "402") (name "unconnected-(DZ1H-A-Pad7)") (class "Default")
      (node (ref "DZ1") (pin "7") (pinfunction "A_7") (pintype "passive"))
    )
    (net (code "403") (name "unconnected-(DZ1H-C-Pad14)") (class "Default")
      (node (ref "DZ1") (pin "14") (pinfunction "C_14") (pintype "passive"))
    )
    (net (code "404") (name "unconnected-(DZ1I-A-Pad8)") (class "Default")
      (node (ref "DZ1") (pin "8") (pinfunction "A_8") (pintype "passive"))
    )
    (net (code "405") (name "unconnected-(DZ1I-C-Pad13)") (class "Default")
      (node (ref "DZ1") (pin "13") (pinfunction "C_13") (pintype "passive"))
    )
    (net (code "406") (name "unconnected-(DZ1J-A-Pad9)") (class "Default")
      (node (ref "DZ1") (pin "9") (pinfunction "A_9") (pintype "passive"))
    )
    (net (code "407") (name "unconnected-(DZ1J-C-Pad12)") (class "Default")
      (node (ref "DZ1") (pin "12") (pinfunction "C_12") (pintype "passive"))
    )
    (net (code "408") (name "unconnected-(J2-NC-PadP$2)") (class "Default")
      (node (ref "J2") (pin "P$2") (pinfunction "NC_P$2") (pintype "no_connect"))
    )
    (net (code "409") (name "unconnected-(J2-NC_-PadP$5)") (class "Default")
      (node (ref "J2") (pin "P$5") (pinfunction "NC__P$5") (pintype "no_connect"))
    )
    (net (code "410") (name "unconnected-(R3-Pad1)") (class "Default")
      (node (ref "R3") (pin "1") (pinfunction "1_1") (pintype "passive"))
    )
    (net (code "411") (name "unconnected-(R3-Pad2)") (class "Default")
      (node (ref "R3") (pin "2") (pinfunction "2_2") (pintype "passive"))
    )
    (net (code "412") (name "unconnected-(R4-Pad1)") (class "Default")
      (node (ref "R4") (pin "1") (pinfunction "1_1") (pintype "passive"))
    )
    (net (code "413") (name "unconnected-(R4-Pad2)") (class "Default")
      (node (ref "R4") (pin "2") (pinfunction "2_2") (pintype "passive"))
    )
    (net (code "414") (name "unconnected-(R5-Pad1)") (class "Default")
      (node (ref "R5") (pin "1") (pinfunction "1_1") (pintype "passive"))
    )
    (net (code "415") (name "unconnected-(R5-Pad2)") (class "Default")
      (node (ref "R5") (pin "2") (pinfunction "2_2") (pintype "passive"))
    )
    (net (code "416") (name "unconnected-(R6-Pad1)") (class "Default")
      (node (ref "R6") (pin "1") (pinfunction "1_1") (pintype "passive"))
    )
    (net (code "417") (name "unconnected-(R6-Pad2)") (class "Default")
      (node (ref "R6") (pin "2") (pinfunction "2_2") (pintype "passive"))
    )
    (net (code "418") (name "unconnected-(R7-Pad1)") (class "Default")
      (node (ref "R7") (pin "1") (pinfunction "1_1") (pintype "passive"))
    )
    (net (code "419") (name "unconnected-(R7-Pad2)") (class "Default")
      (node (ref "R7") (pin "2") (pinfunction "2_2") (pintype "passive"))
    )
    (net (code "420") (name "unconnected-(R8-Pad1)") (class "Default")
      (node (ref "R8") (pin "1") (pinfunction "1_1") (pintype "passive"))
    )
    (net (code "421") (name "unconnected-(R8-Pad2)") (class "Default")
      (node (ref "R8") (pin "2") (pinfunction "2_2") (pintype "passive"))
    )
    (net (code "422") (name "unconnected-(R9-Pad1)") (class "Default")
      (node (ref "R9") (pin "1") (pinfunction "1_1") (pintype "passive"))
    )
    (net (code "423") (name "unconnected-(R9-Pad2)") (class "Default")
      (node (ref "R9") (pin "2") (pinfunction "2_2") (pintype "passive"))
    )
    (net (code "424") (name "unconnected-(R10-Pad1)") (class "Default")
      (node (ref "R10") (pin "1") (pinfunction "1_1") (pintype "passive"))
    )
    (net (code "425") (name "unconnected-(R10-Pad2)") (class "Default")
      (node (ref "R10") (pin "2") (pinfunction "2_2") (pintype "passive"))
    )
    (net (code "426") (name "unconnected-(R11-Pad1)") (class "Default")
      (node (ref "R11") (pin "1") (pinfunction "1_1") (pintype "passive"))
    )
    (net (code "427") (name "unconnected-(R11-Pad2)") (class "Default")
      (node (ref "R11") (pin "2") (pinfunction "2_2") (pintype "passive"))
    )
    (net (code "428") (name "unconnected-(R12-Pad1)") (class "Default")
      (node (ref "R12") (pin "1") (pinfunction "1_1") (pintype "passive"))
    )
    (net (code "429") (name "unconnected-(R12-Pad2)") (class "Default")
      (node (ref "R12") (pin "2") (pinfunction "2_2") (pintype "passive"))
    )
    (net (code "430") (name "unconnected-(SV1-Pad2)") (class "Default")
      (node (ref "SV1") (pin "2") (pinfunction "2_2") (pintype "passive"))
    )
    (net (code "431") (name "unconnected-(SV1-Pad4)") (class "Default")
      (node (ref "SV1") (pin "4") (pinfunction "4_4") (pintype "passive"))
    )
    (net (code "432") (name "unconnected-(SV1-Pad6)") (class "Default")
      (node (ref "SV1") (pin "6") (pinfunction "6_6") (pintype "passive"))
    )
    (net (code "433") (name "unconnected-(SV1-Pad8)") (class "Default")
      (node (ref "SV1") (pin "8") (pinfunction "8_8") (pintype "passive"))
    )
    (net (code "434") (name "unconnected-(SV1-Pad10)") (class "Default")
      (node (ref "SV1") (pin "10") (pinfunction "10_10") (pintype "passive"))
    )
    (net (code "435") (name "unconnected-(SV2-Pad1)") (class "Default")
      (node (ref "SV2") (pin "1") (pinfunction "1_1") (pintype "passive"))
    )
    (net (code "436") (name "unconnected-(SV2-Pad2)") (class "Default")
      (node (ref "SV2") (pin "2") (pinfunction "2_2") (pintype "passive"))
    )
    (net (code "437") (name "unconnected-(SV2-Pad3)") (class "Default")
      (node (ref "SV2") (pin "3") (pinfunction "3_3") (pintype "passive"))
    )
    (net (code "438") (name "unconnected-(SV2-Pad4)") (class "Default")
      (node (ref "SV2") (pin "4") (pinfunction "4_4") (pintype "passive"))
    )
    (net (code "439") (name "unconnected-(SW1-Pad1)") (class "Default")
      (node (ref "SW1") (pin "1") (pinfunction "1_1") (pintype "no_connect"))
    )
    (net (code "440") (name "unconnected-(SW1-Pad4)") (class "Default")
      (node (ref "SW1") (pin "4") (pinfunction "4_4") (pintype "no_connect"))
    )
    (net (code "441") (name "unconnected-(U1A-CCLK_0-PadG7)") (class "Default")
      (node (ref "U1") (pin "G7") (pinfunction "CCLK_0_G7") (pintype "bidirectional"))
    )
    (net (code "442") (name "unconnected-(U1A-DONE_0-PadP6)") (class "Default")
      (node (ref "U1") (pin "P6") (pinfunction "DONE_0_P6") (pintype "bidirectional"))
    )
    (net (code "443") (name "unconnected-(U1A-PROGRAM_B_0-PadM6)") (class "Default")
      (node (ref "U1") (pin "M6") (pinfunction "PROGRAM_B_0_M6") (pintype "input"))
    )
    (net (code "444") (name "unconnected-(U1A-TCK_0-PadK7)") (class "Default")
      (node (ref "U1") (pin "K7") (pinfunction "TCK_0_K7") (pintype "input"))
    )
    (net (code "445") (name "unconnected-(U1A-TDI_0-PadK6)") (class "Default")
      (node (ref "U1") (pin "K6") (pinfunction "TDI_0_K6") (pintype "input"))
    )
    (net (code "446") (name "unconnected-(U1A-TDO_0-PadJ6)") (class "Default")
      (node (ref "U1") (pin "J6") (pinfunction "TDO_0_J6") (pintype "output"))
    )
    (net (code "447") (name "unconnected-(U1A-TMS_0-PadL6)") (class "Default")
      (node (ref "U1") (pin "L6") (pinfunction "TMS_0_L6") (pintype "input"))
    )
    (net (code "448") (name "unconnected-(U1A-VCCO_0-PadJ7)") (class "Default")
      (node (ref "U1") (pin "J7") (pinfunction "VCCO_0_J7") (pintype "input"))
    )
    (net (code "449") (name "unconnected-(U1A-VCCO_0-PadN7)") (class "Default")
      (node (ref "U1") (pin "N7") (pinfunction "VCCO_0_N7") (pintype "input"))
    )
    (net (code "450") (name "unconnected-(U1B-MGTREFCLK0N_115-PadD5)") (class "Default")
      (node (ref "U1") (pin "D5") (pinfunction "MGTREFCLK0N_115_D5") (pintype "input"))
    )
    (net (code "451") (name "unconnected-(U1B-MGTREFCLK0P_115-PadD6)") (class "Default")
      (node (ref "U1") (pin "D6") (pinfunction "MGTREFCLK0P_115_D6") (pintype "input"))
    )
    (net (code "452") (name "unconnected-(U1K-MGTAVCC-PadA6)") (class "Default")
      (node (ref "U1") (pin "A6") (pinfunction "MGTAVCC_A6") (pintype "input"))
    )
    (net (code "453") (name "unconnected-(U1K-MGTAVCC-PadC6)") (class "Default")
      (node (ref "U1") (pin "C6") (pinfunction "MGTAVCC_C6") (pintype "input"))
    )
    (net (code "454") (name "unconnected-(U1K-MGTAVCC-PadE6)") (class "Default")
      (node (ref "U1") (pin "E6") (pinfunction "MGTAVCC_E6") (pintype "input"))
    )
    (net (code "455") (name "unconnected-(U1K-MGTAVCC-PadG6)") (class "Default")
      (node (ref "U1") (pin "G6") (pinfunction "MGTAVCC_G6") (pintype "input"))
    )
    (net (code "456") (name "unconnected-(U1L-MGTAVTT-PadA2)") (class "Default")
      (node (ref "U1") (pin "A2") (pinfunction "MGTAVTT_A2") (pintype "input"))
    )
    (net (code "457") (name "unconnected-(U1L-MGTAVTT-PadC2)") (class "Default")
      (node (ref "U1") (pin "C2") (pinfunction "MGTAVTT_C2") (pintype "input"))
    )
    (net (code "458") (name "unconnected-(U1L-MGTAVTT-PadE2)") (class "Default")
      (node (ref "U1") (pin "E2") (pinfunction "MGTAVTT_E2") (pintype "input"))
    )
    (net (code "459") (name "unconnected-(U1L-MGTAVTT-PadG2)") (class "Default")
      (node (ref "U1") (pin "G2") (pinfunction "MGTAVTT_G2") (pintype "input"))
    )
    (net (code "460") (name "unconnected-(U1M-MGTVCCAUX-PadJ4)") (class "Default")
      (node (ref "U1") (pin "J4") (pinfunction "MGTVCCAUX_J4") (pintype "input"))
    )
    (net (code "461") (name "unconnected-(U1N-DXN_0-PadN11)") (class "Default")
      (node (ref "U1") (pin "N11") (pinfunction "DXN_0_N11") (pintype "bidirectional"))
    )
    (net (code "462") (name "unconnected-(U1N-DXP_0-PadN12)") (class "Default")
      (node (ref "U1") (pin "N12") (pinfunction "DXP_0_N12") (pintype "bidirectional"))
    )
    (net (code "463") (name "unconnected-(U1O-VCCAUX-PadK10)") (class "Default")
      (node (ref "U1") (pin "K10") (pinfunction "VCCAUX_K10") (pintype "input"))
    )
    (net (code "464") (name "unconnected-(U1O-VCCAUX-PadM10)") (class "Default")
      (node (ref "U1") (pin "M10") (pinfunction "VCCAUX_M10") (pintype "input"))
    )
    (net (code "465") (name "unconnected-(U1O-VCCAUX-PadP8)") (class "Default")
      (node (ref "U1") (pin "P8") (pinfunction "VCCAUX_P8") (pintype "input"))
    )
    (net (code "466") (name "unconnected-(U1O-VCCAUX-PadP10)") (class "Default")
      (node (ref "U1") (pin "P10") (pinfunction "VCCAUX_P10") (pintype "input"))
    )
    (net (code "467") (name "unconnected-(U1O-VCCAUX-PadP12)") (class "Default")
      (node (ref "U1") (pin "P12") (pinfunction "VCCAUX_P12") (pintype "input"))
    )
    (net (code "468") (name "unconnected-(U1O-VCCAUX-PadR9)") (class "Default")
      (node (ref "U1") (pin "R9") (pinfunction "VCCAUX_R9") (pintype "input"))
    )
    (net (code "469") (name "unconnected-(U1O-VCCAUX-PadR11)") (class "Default")
      (node (ref "U1") (pin "R11") (pinfunction "VCCAUX_R11") (pintype "input"))
    )
    (net (code "470") (name "unconnected-(U1P-VCCBRAM-PadL13)") (class "Default")
      (node (ref "U1") (pin "L13") (pinfunction "VCCBRAM_L13") (pintype "input"))
    )
    (net (code "471") (name "unconnected-(U1P-VCCBRAM-PadN13)") (class "Default")
      (node (ref "U1") (pin "N13") (pinfunction "VCCBRAM_N13") (pintype "input"))
    )
    (net (code "472") (name "unconnected-(U1P-VCCBRAM-PadR13)") (class "Default")
      (node (ref "U1") (pin "R13") (pinfunction "VCCBRAM_R13") (pintype "input"))
    )
    (net (code "473") (name "unconnected-(U1Q-VCCINT-PadJ9)") (class "Default")
      (node (ref "U1") (pin "J9") (pinfunction "VCCINT_J9") (pintype "input"))
    )
    (net (code "474") (name "unconnected-(U1Q-VCCINT-PadJ11)") (class "Default")
      (node (ref "U1") (pin "J11") (pinfunction "VCCINT_J11") (pintype "input"))
    )
    (net (code "475") (name "unconnected-(U1Q-VCCINT-PadJ13)") (class "Default")
      (node (ref "U1") (pin "J13") (pinfunction "VCCINT_J13") (pintype "input"))
    )
    (net (code "476") (name "unconnected-(U1Q-VCCINT-PadJ15)") (class "Default")
      (node (ref "U1") (pin "J15") (pinfunction "VCCINT_J15") (pintype "input"))
    )
    (net (code "477") (name "unconnected-(U1Q-VCCINT-PadK8)") (class "Default")
      (node (ref "U1") (pin "K8") (pinfunction "VCCINT_K8") (pintype "input"))
    )
    (net (code "478") (name "unconnected-(U1Q-VCCINT-PadK14)") (class "Default")
      (node (ref "U1") (pin "K14") (pinfunction "VCCINT_K14") (pintype "input"))
    )
    (net (code "479") (name "unconnected-(U1Q-VCCINT-PadL9)") (class "Default")
      (node (ref "U1") (pin "L9") (pinfunction "VCCINT_L9") (pintype "input"))
    )
    (net (code "480") (name "unconnected-(U1Q-VCCINT-PadL15)") (class "Default")
      (node (ref "U1") (pin "L15") (pinfunction "VCCINT_L15") (pintype "input"))
    )
    (net (code "481") (name "unconnected-(U1Q-VCCINT-PadM8)") (class "Default")
      (node (ref "U1") (pin "M8") (pinfunction "VCCINT_M8") (pintype "input"))
    )
    (net (code "482") (name "unconnected-(U1Q-VCCINT-PadM14)") (class "Default")
      (node (ref "U1") (pin "M14") (pinfunction "VCCINT_M14") (pintype "input"))
    )
    (net (code "483") (name "unconnected-(U1Q-VCCINT-PadN9)") (class "Default")
      (node (ref "U1") (pin "N9") (pinfunction "VCCINT_N9") (pintype "input"))
    )
    (net (code "484") (name "unconnected-(U1Q-VCCINT-PadN15)") (class "Default")
      (node (ref "U1") (pin "N15") (pinfunction "VCCINT_N15") (pintype "input"))
    )
    (net (code "485") (name "unconnected-(U1Q-VCCINT-PadP14)") (class "Default")
      (node (ref "U1") (pin "P14") (pinfunction "VCCINT_P14") (pintype "input"))
    )
    (net (code "486") (name "unconnected-(U1Q-VCCINT-PadR15)") (class "Default")
      (node (ref "U1") (pin "R15") (pinfunction "VCCINT_R15") (pintype "input"))
    )
    (net (code "487") (name "unconnected-(U1R-VCCADC_0-PadK12)") (class "Default")
      (node (ref "U1") (pin "K12") (pinfunction "VCCADC_0_K12") (pintype "input"))
    )
    (net (code "488") (name "unconnected-(U1R-VN_0-PadM11)") (class "Default")
      (node (ref "U1") (pin "M11") (pinfunction "VN_0_M11") (pintype "bidirectional"))
    )
    (net (code "489") (name "unconnected-(U1R-VP_0-PadL12)") (class "Default")
      (node (ref "U1") (pin "L12") (pinfunction "VP_0_L12") (pintype "bidirectional"))
    )
    (net (code "490") (name "unconnected-(U1R-VREFP_0-PadM12)") (class "Default")
      (node (ref "U1") (pin "M12") (pinfunction "VREFP_0_M12") (pintype "bidirectional"))
    )
    (net (code "491") (name "unconnected-(U4-Pad4)") (class "Default")
      (node (ref "U4") (pin "4") (pinfunction "4_4") (pintype "passive"))
    )
    (net (code "492") (name "unconnected-(U5-NC-PadP$2)") (class "Default")
      (node (ref "U5") (pin "P$2") (pinfunction "NC_P$2") (pintype "no_connect"))
    )
    (net (code "493") (name "unconnected-(U6-EN-Pad2)") (class "Default")
      (node (ref "U6") (pin "2") (pinfunction "EN_2") (pintype "input"))
    )
    (net (code "494") (name "unconnected-(U6-EPAD-Pad23)") (class "Default")
      (node (ref "U6") (pin "23") (pinfunction "EPAD_23") (pintype "passive"))
    )
    (net (code "495") (name "unconnected-(U6-LL-Pad11)") (class "Default")
      (node (ref "U6") (pin "11") (pinfunction "LL_11") (pintype "output"))
    )
    (net (code "496") (name "unconnected-(U6-LL_2-Pad6)") (class "Default")
      (node (ref "U6") (pin "6") (pinfunction "LL_2_6") (pintype "output"))
    )
    (net (code "497") (name "unconnected-(U6-LL_3-Pad7)") (class "Default")
      (node (ref "U6") (pin "7") (pinfunction "LL_3_7") (pintype "output"))
    )
    (net (code "498") (name "unconnected-(U6-LL_4-Pad8)") (class "Default")
      (node (ref "U6") (pin "8") (pinfunction "LL_4_8") (pintype "output"))
    )
    (net (code "499") (name "unconnected-(U6-LL_5-Pad9)") (class "Default")
      (node (ref "U6") (pin "9") (pinfunction "LL_5_9") (pintype "output"))
    )
    (net (code "500") (name "unconnected-(U6-LL_6-Pad10)") (class "Default")
      (node (ref "U6") (pin "10") (pinfunction "LL_6_10") (pintype "output"))
    )
    (net (code "501") (name "unconnected-(U6-N{slash}C-Pad5)") (class "Default")
      (node (ref "U6") (pin "5") (pinfunction "N/C_5") (pintype "passive"))
    )
    (net (code "502") (name "unconnected-(U6-PGOOD-Pad3)") (class "Default")
      (node (ref "U6") (pin "3") (pinfunction "PGOOD_3") (pintype "output"))
    )
    (net (code "503") (name "unconnected-(U6-RF-Pad22)") (class "Default")
      (node (ref "U6") (pin "22") (pinfunction "RF_22") (pintype "input"))
    )
    (net (code "504") (name "unconnected-(U6-VBST-Pad4)") (class "Default")
      (node (ref "U6") (pin "4") (pinfunction "VBST_4") (pintype "input"))
    )
    (net (code "505") (name "unconnected-(U6-VFB-Pad1)") (class "Default")
      (node (ref "U6") (pin "1") (pinfunction "VFB_1") (pintype "output"))
    )
    (net (code "506") (name "unconnected-(U7-Pad4)") (class "Default")
      (node (ref "U7") (pin "4") (pinfunction "4_4") (pintype "passive"))
    )
    (net (code "507") (name "unconnected-(U8-Pad4)") (class "Default")
      (node (ref "U8") (pin "4") (pinfunction "4_4") (pintype "passive"))
    )
  )
)
